# hi_hardware.net
KiCad netlist of a schematic drawn in EAGLE
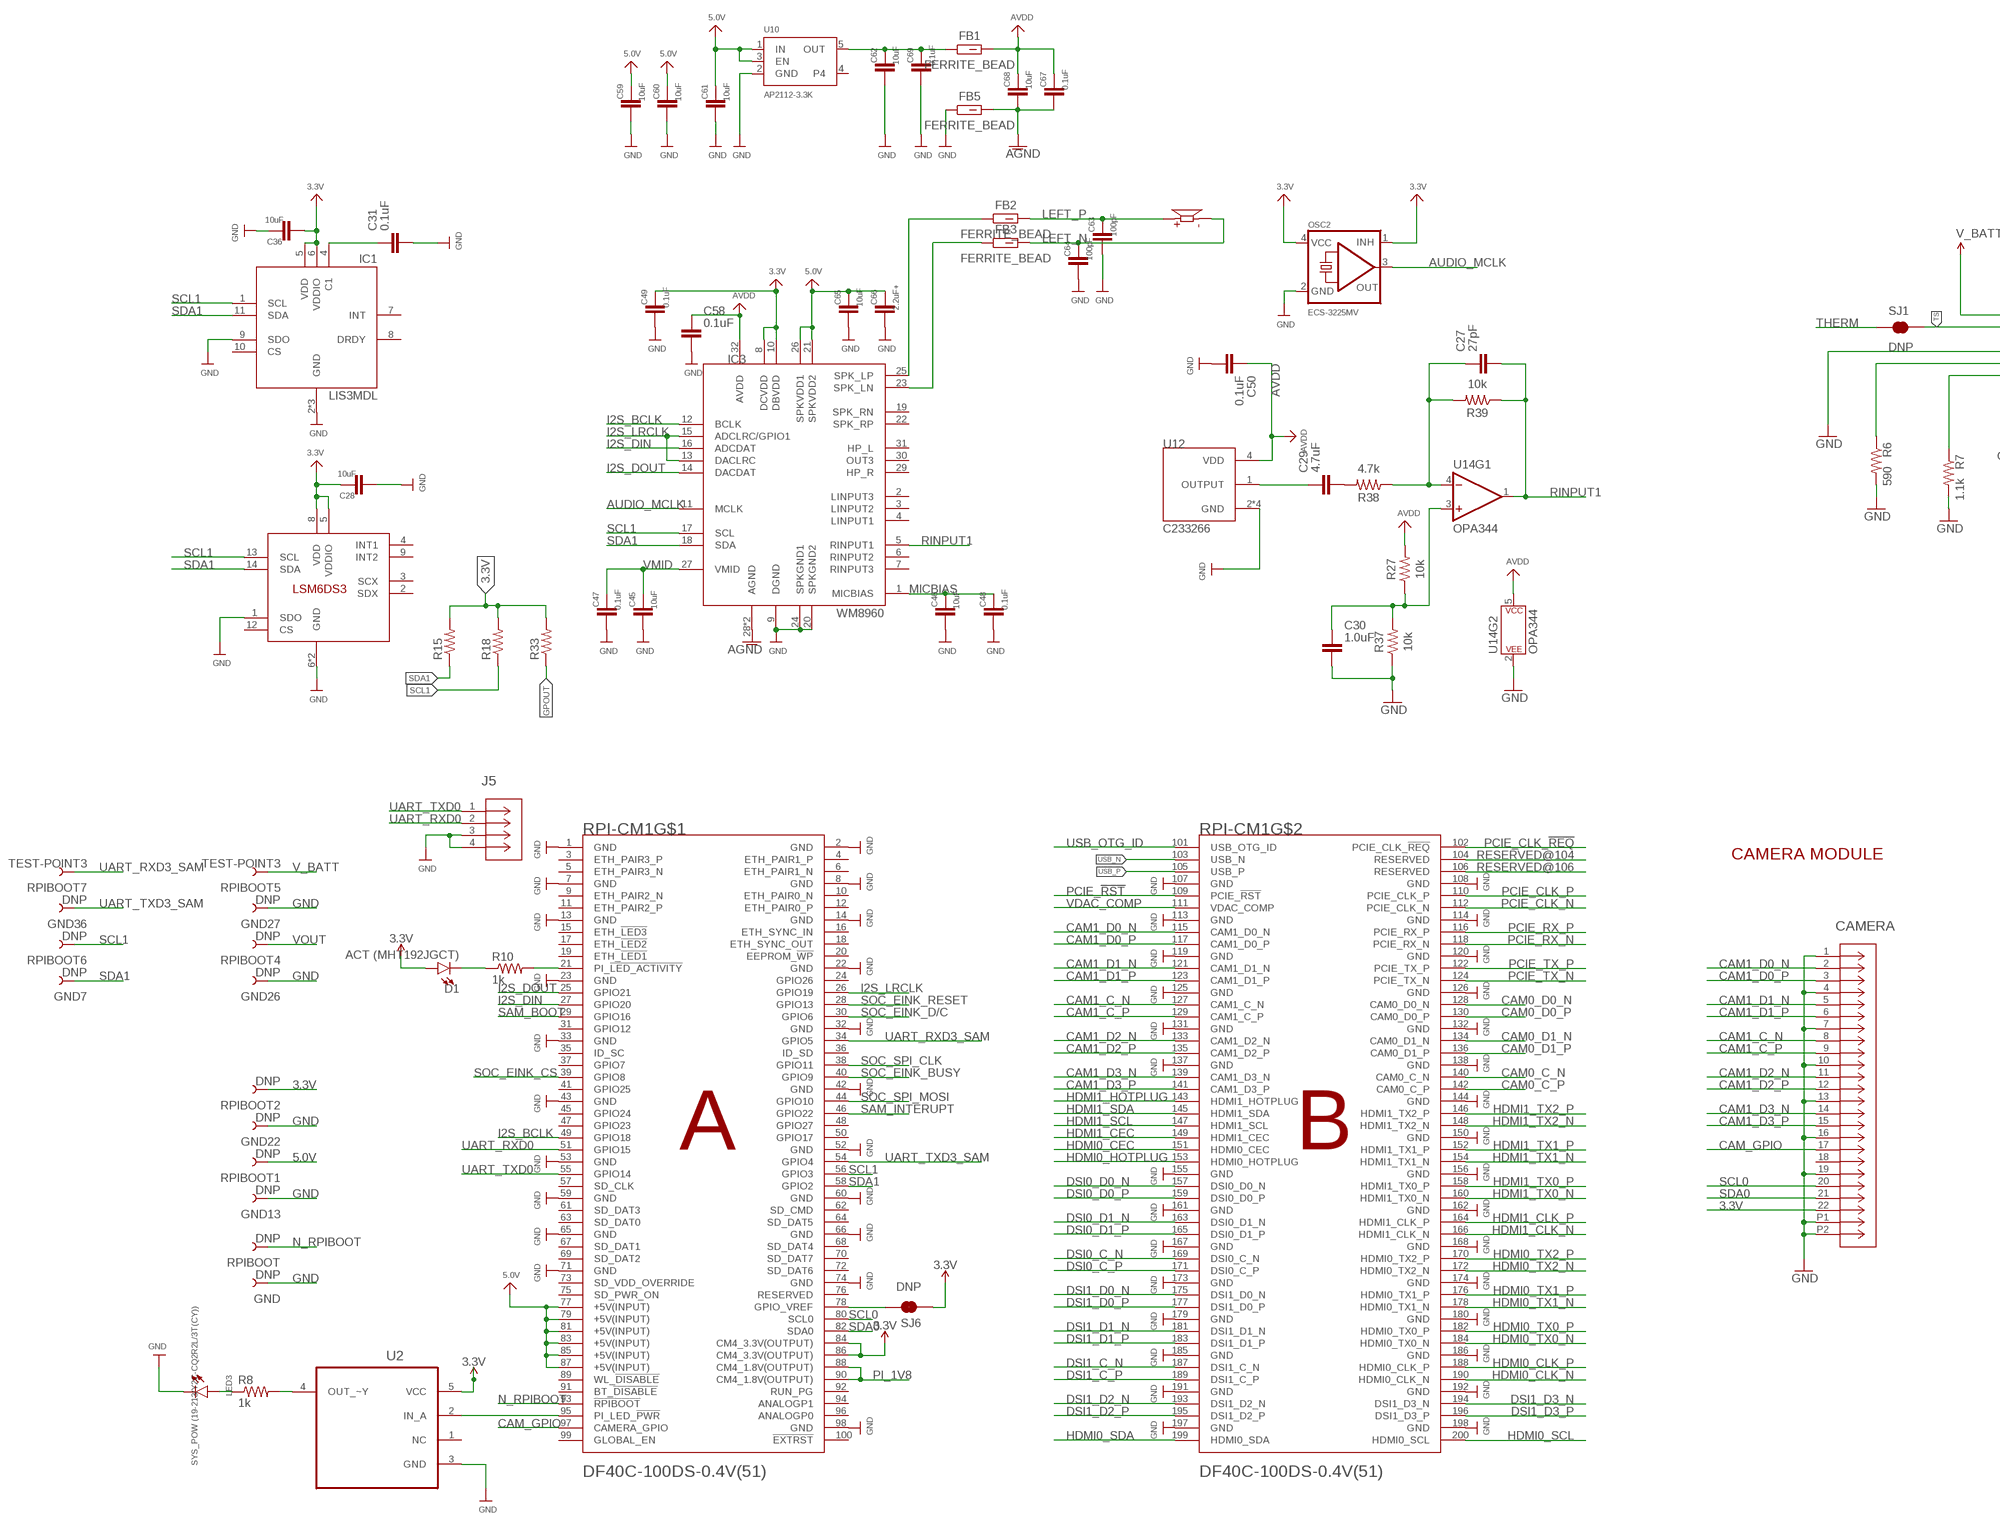
[diagram p0: schematic, sheet 1, part 1 of 3]
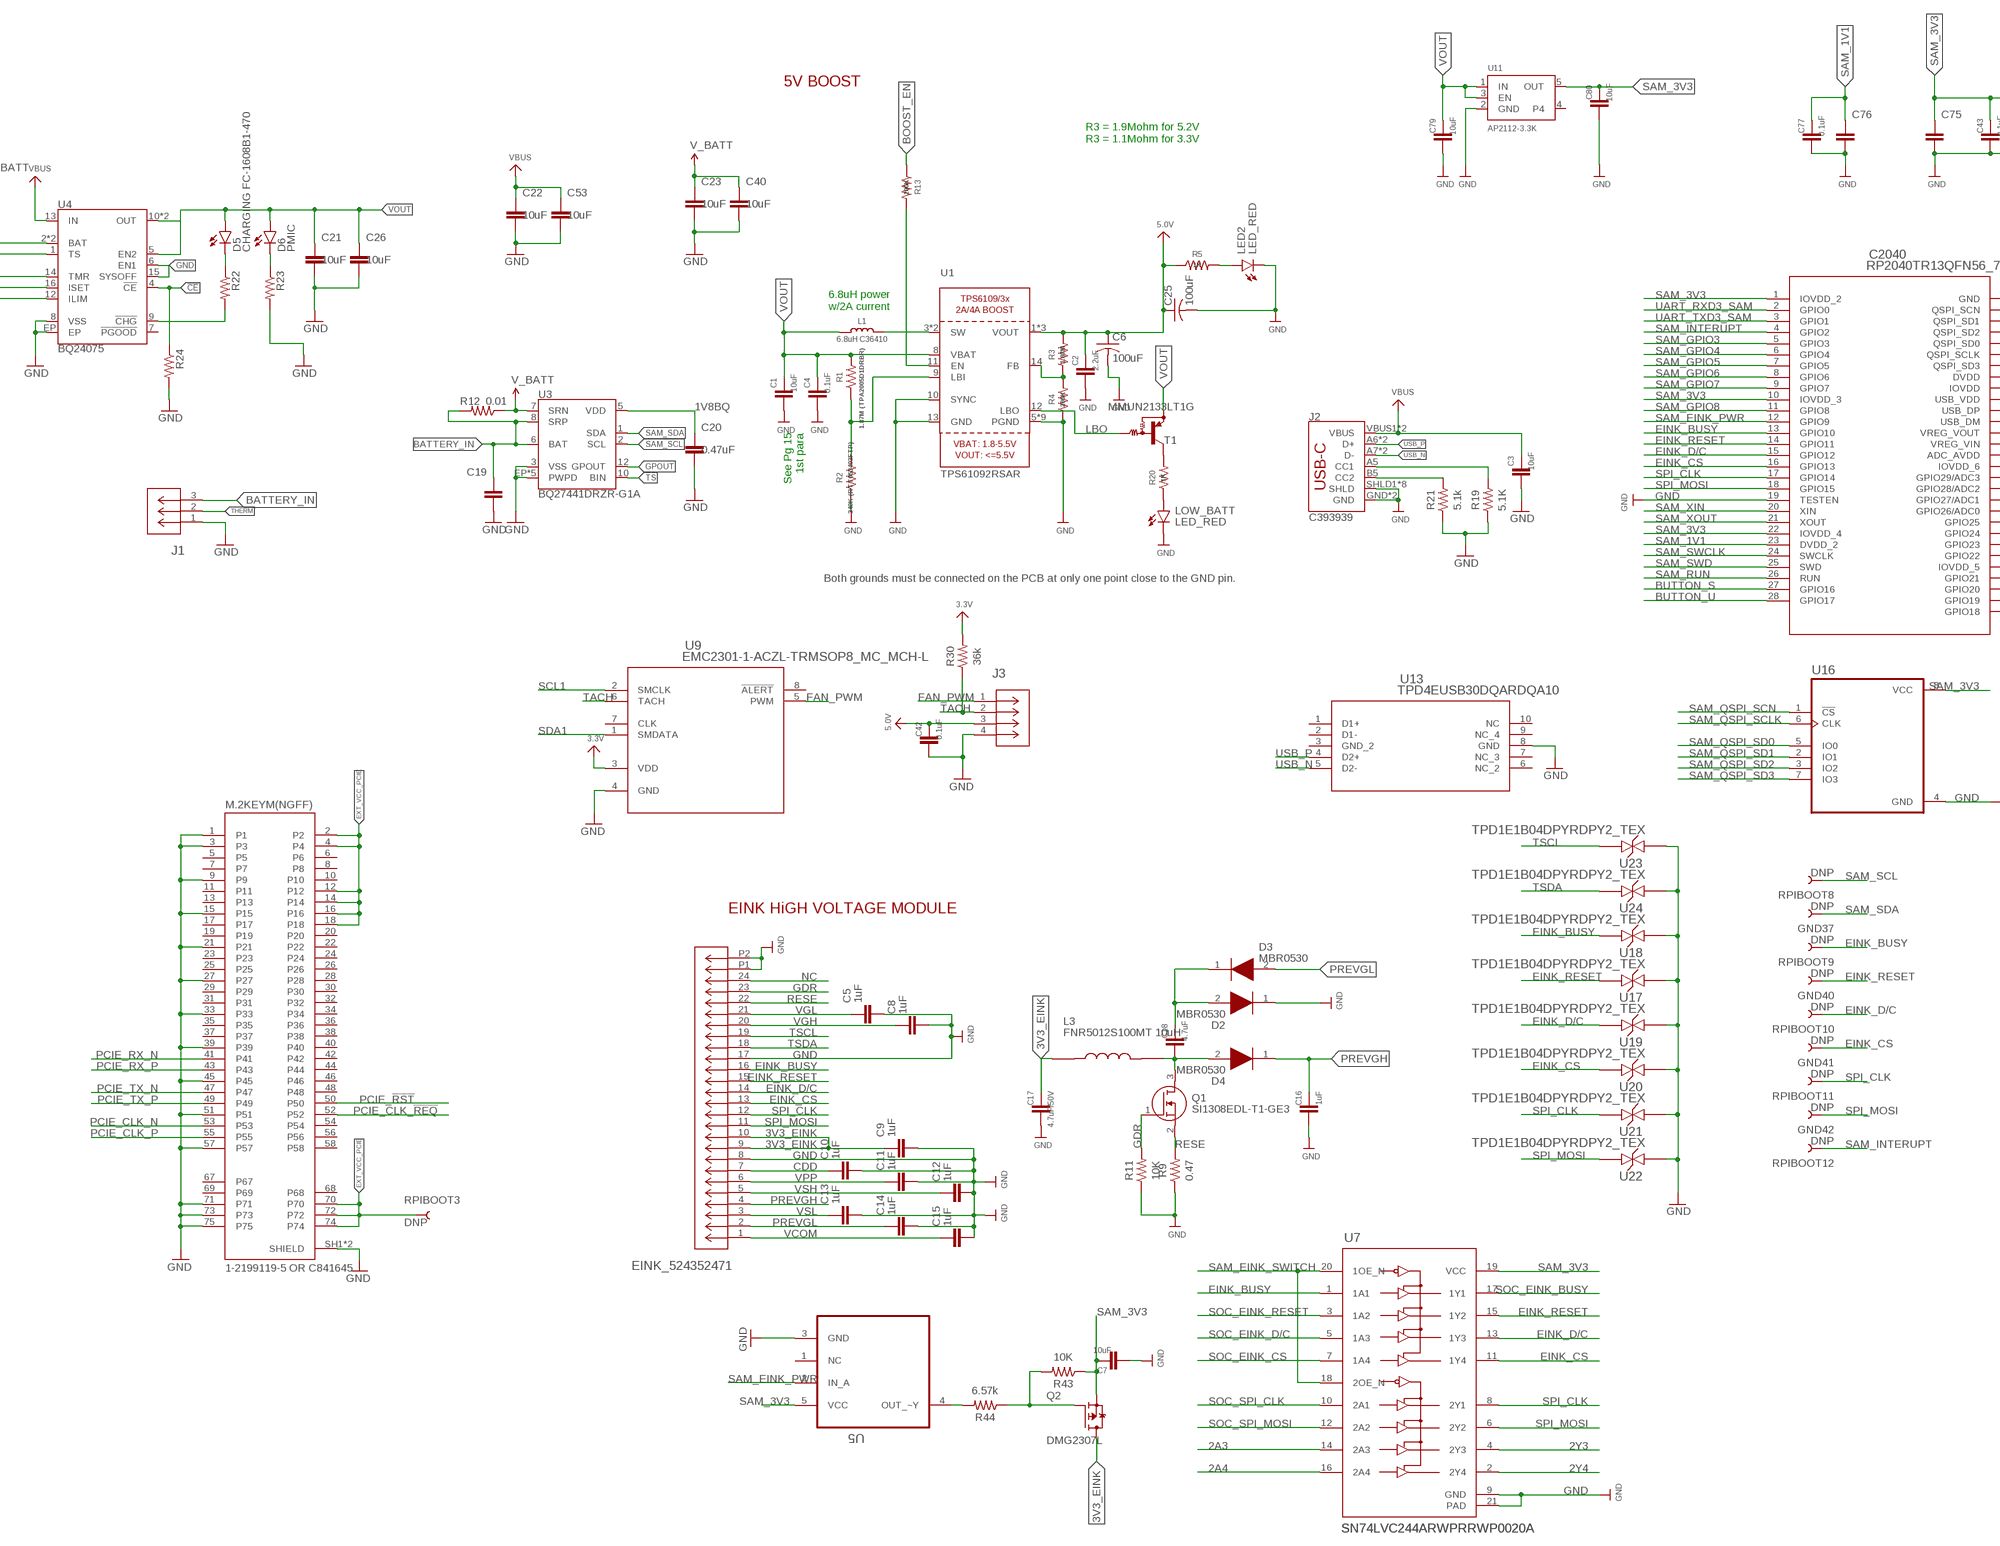
[diagram p1: schematic, sheet 1, part 2 of 3]
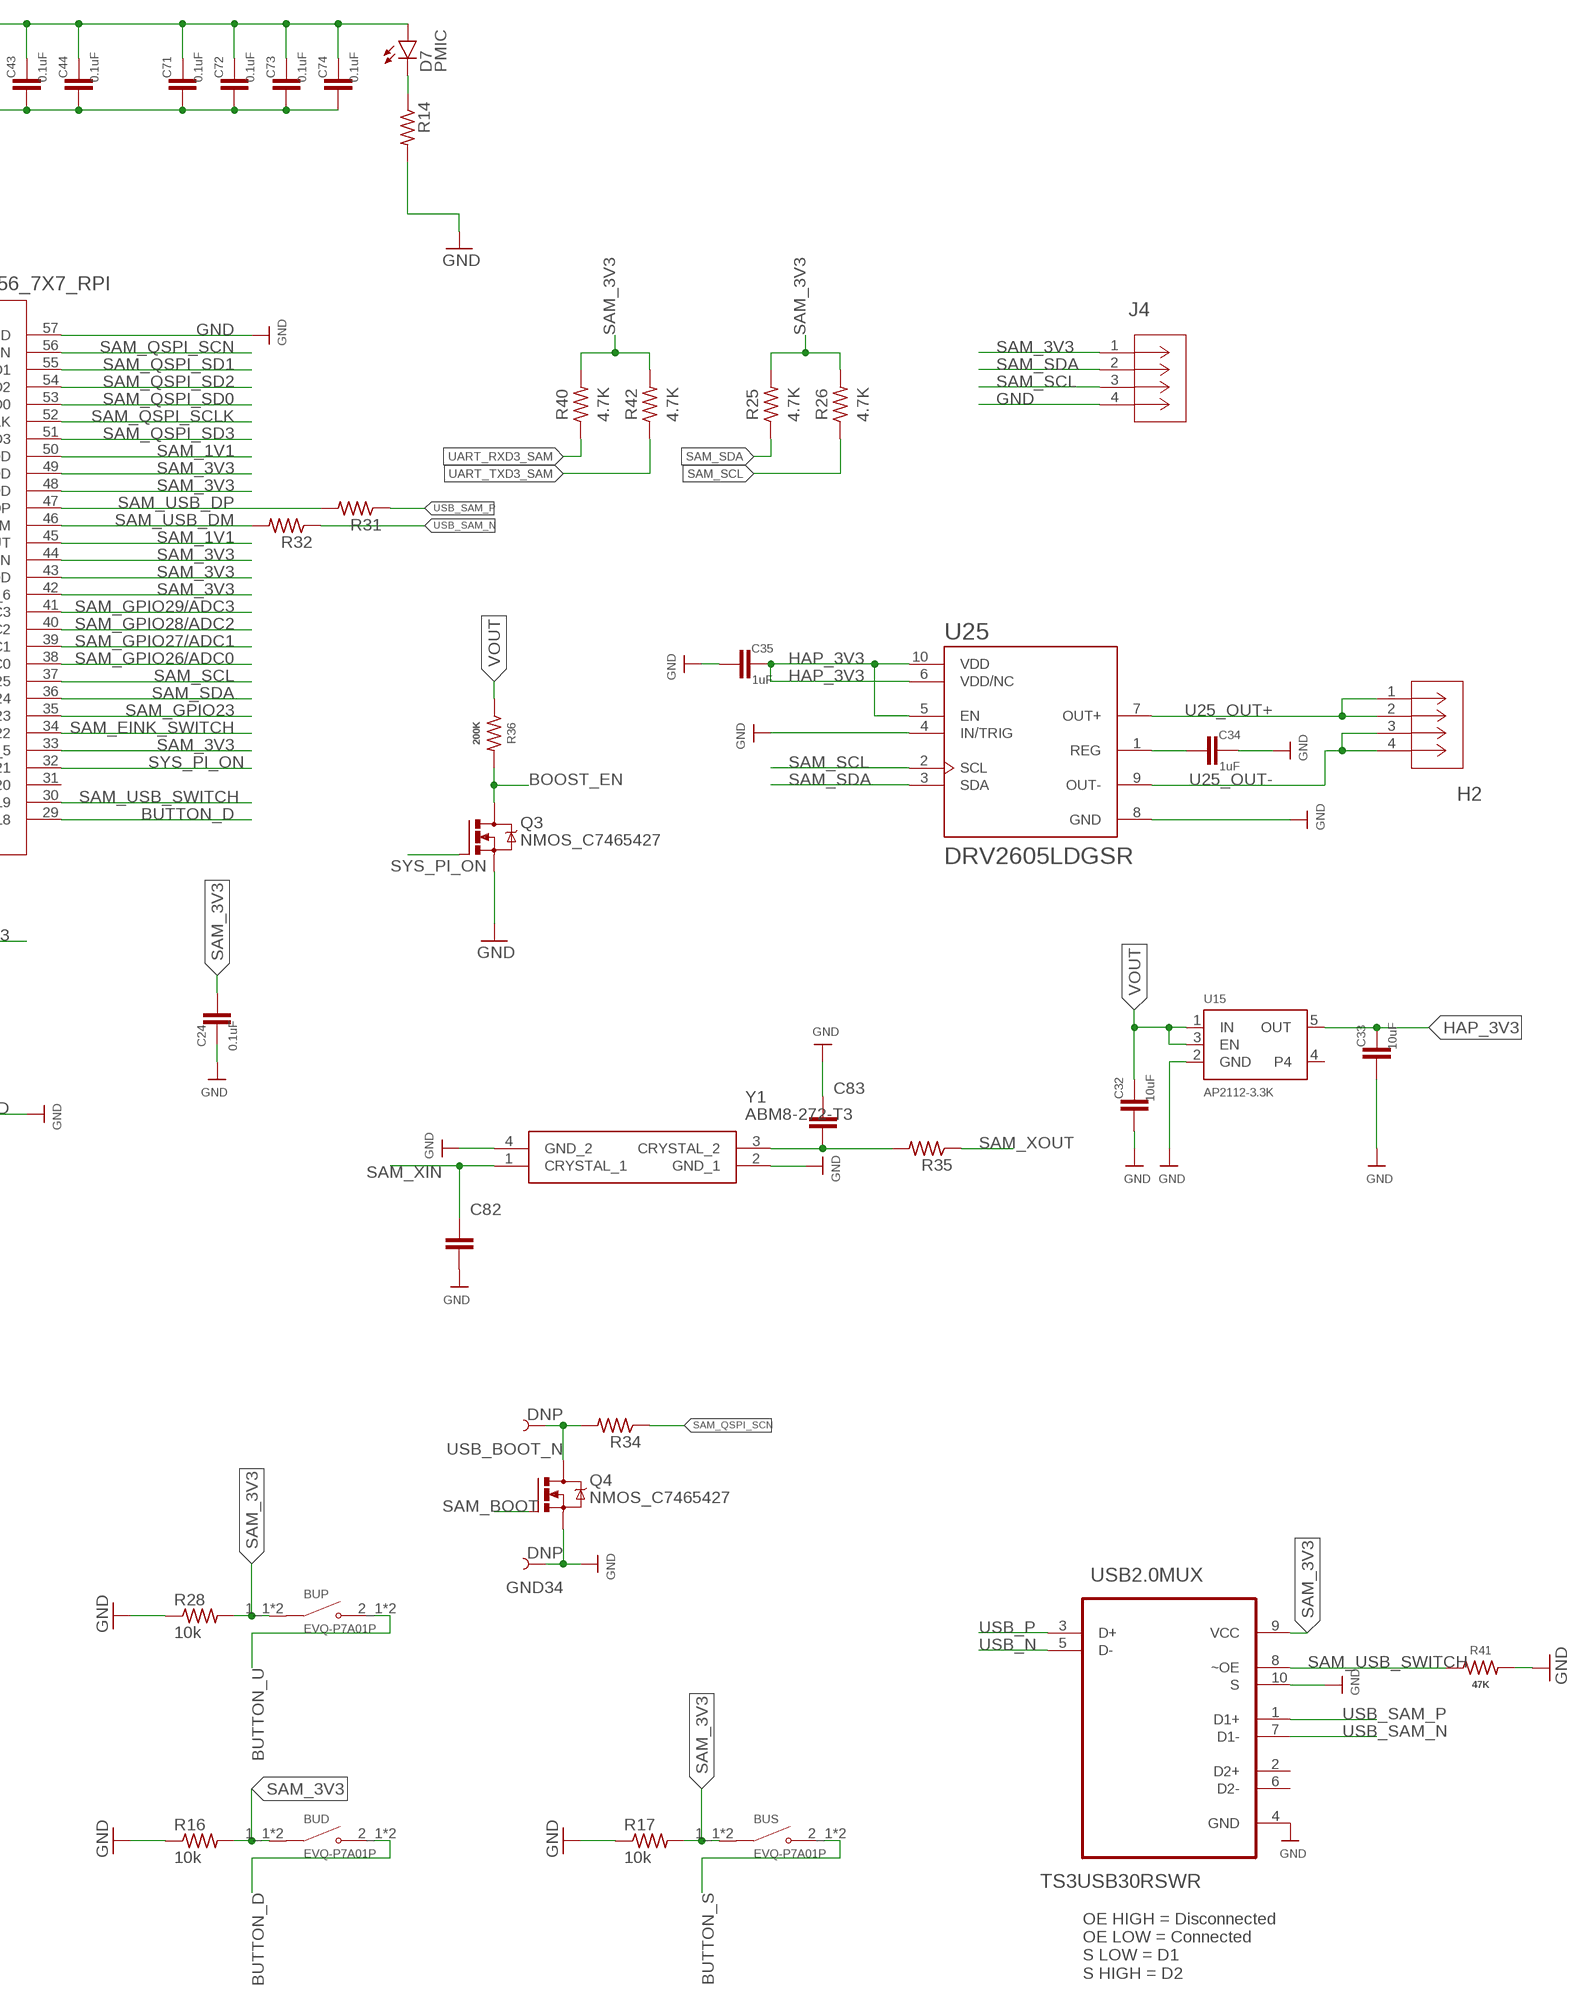
[diagram p2: schematic, sheet 1, part 3 of 3]

(export (version "E")
  (design (tool "Eeschema 10.0.6"))
  (components
    (comp (ref "BUD")
      (value "EVQ-P7A01P")
      (footprint "eagle-import:SW_EVQ-P7A01P")
      (fields (field (name "MANUFACTURER") "Panasonic Electronic Components"))
      (libsource (lib "eagle-import") (part "EVQ-P7A01P"))
    )
    (comp (ref "BUP")
      (value "EVQ-P7A01P")
      (footprint "eagle-import:SW_EVQ-P7A01P")
      (fields (field (name "MANUFACTURER") "Panasonic Electronic Components"))
      (libsource (lib "eagle-import") (part "EVQ-P7A01P"))
    )
    (comp (ref "BUS")
      (value "EVQ-P7A01P")
      (footprint "eagle-import:SW_EVQ-P7A01P")
      (fields (field (name "MANUFACTURER") "Panasonic Electronic Components"))
      (libsource (lib "eagle-import") (part "EVQ-P7A01P"))
    )
    (comp (ref "C1")
      (value "10uF")
      (footprint "eagle-import:CAPC1005X60")
      (libsource (lib "eagle-import") (part "CCHIP-0402(1005-METRIC)_"))
    )
    (comp (ref "C2")
      (value "2.2uF")
      (footprint "eagle-import:CAPC1005X60")
      (libsource (lib "eagle-import") (part "CCHIP-0402(1005-METRIC)_"))
    )
    (comp (ref "C3")
      (value "10uF")
      (footprint "eagle-import:CAPC1005X60")
      (libsource (lib "eagle-import") (part "CCHIP-0402(1005-METRIC)_"))
    )
    (comp (ref "C4")
      (value "0.1uF")
      (footprint "eagle-import:CAPC1005X60")
      (libsource (lib "eagle-import") (part "CCHIP-0402(1005-METRIC)_"))
    )
    (comp (ref "C5")
      (value "1uF")
      (footprint "eagle-import:CAPC1005X60")
      (libsource (lib "eagle-import") (part "CCHIP-0402(1005-METRIC)_"))
    )
    (comp (ref "C6")
      (value "100uF")
      (footprint "eagle-import:C1210")
      (libsource (lib "eagle-import") (part "C-USC1210"))
    )
    (comp (ref "C7")
      (value "10uF")
      (footprint "eagle-import:CAPC1005X60")
      (libsource (lib "eagle-import") (part "CCHIP-0402(1005-METRIC)_"))
    )
    (comp (ref "C8")
      (value "1uF")
      (footprint "eagle-import:CAPC1005X60")
      (libsource (lib "eagle-import") (part "CCHIP-0402(1005-METRIC)_"))
    )
    (comp (ref "C9")
      (value "1uF")
      (footprint "eagle-import:CAPC1005X60")
      (libsource (lib "eagle-import") (part "CCHIP-0402(1005-METRIC)_"))
    )
    (comp (ref "C10")
      (value "1uF")
      (footprint "eagle-import:CAPC1005X60")
      (libsource (lib "eagle-import") (part "CCHIP-0402(1005-METRIC)_"))
    )
    (comp (ref "C11")
      (value "1uF")
      (footprint "eagle-import:CAPC1005X60")
      (libsource (lib "eagle-import") (part "CCHIP-0402(1005-METRIC)_"))
    )
    (comp (ref "C12")
      (value "1uF")
      (footprint "eagle-import:CAPC1005X60")
      (libsource (lib "eagle-import") (part "CCHIP-0402(1005-METRIC)_"))
    )
    (comp (ref "C13")
      (value "1uF")
      (footprint "eagle-import:CAPC1005X60")
      (libsource (lib "eagle-import") (part "CCHIP-0402(1005-METRIC)_"))
    )
    (comp (ref "C14")
      (value "1uF")
      (footprint "eagle-import:CAPC1005X60")
      (libsource (lib "eagle-import") (part "CCHIP-0402(1005-METRIC)_"))
    )
    (comp (ref "C15")
      (value "1uF")
      (footprint "eagle-import:CAPC1005X60")
      (libsource (lib "eagle-import") (part "CCHIP-0402(1005-METRIC)_"))
    )
    (comp (ref "C16")
      (value "1uF")
      (footprint "eagle-import:CAPC1005X60")
      (libsource (lib "eagle-import") (part "CCHIP-0402(1005-METRIC)_"))
    )
    (comp (ref "C17")
      (value "4.7uF/50V")
      (footprint "eagle-import:CAPC1005X60")
      (libsource (lib "eagle-import") (part "CCHIP-0402(1005-METRIC)_"))
    )
    (comp (ref "C18")
      (value "4.7uF")
      (footprint "eagle-import:CAPC1608X85")
      (libsource (lib "eagle-import") (part "CCHIP-0603(1608-METRIC)_"))
    )
    (comp (ref "C19")
      (value "1.0uF")
      (footprint "eagle-import:CAPC1005X60")
      (libsource (lib "eagle-import") (part "CCHIP-0402(1005-METRIC)_"))
    )
    (comp (ref "C20")
      (value "0.47uF")
      (footprint "eagle-import:CAPC1005X60")
      (libsource (lib "eagle-import") (part "CCHIP-0402(1005-METRIC)_"))
    )
    (comp (ref "C21")
      (value "10uF")
      (footprint "eagle-import:CAPC1005X60")
      (libsource (lib "eagle-import") (part "CCHIP-0402(1005-METRIC)_"))
    )
    (comp (ref "C22")
      (value "10uF")
      (footprint "eagle-import:CAPC1005X60")
      (libsource (lib "eagle-import") (part "CCHIP-0402(1005-METRIC)_"))
    )
    (comp (ref "C23")
      (value "10uF")
      (footprint "eagle-import:CAPC1005X60")
      (libsource (lib "eagle-import") (part "CCHIP-0402(1005-METRIC)_"))
    )
    (comp (ref "C24")
      (value "0.1uF")
      (footprint "eagle-import:CAPC1005X60")
      (libsource (lib "eagle-import") (part "CCHIP-0402(1005-METRIC)_"))
    )
    (comp (ref "C25")
      (value "100uF")
      (footprint "eagle-import:C1210")
      (libsource (lib "eagle-import") (part "C-USC1210"))
    )
    (comp (ref "C26")
      (value "10uF")
      (footprint "eagle-import:CAPC1005X60")
      (libsource (lib "eagle-import") (part "CCHIP-0402(1005-METRIC)_"))
    )
    (comp (ref "C27")
      (value "27pF")
      (footprint "eagle-import:CAPC1005X60")
      (libsource (lib "eagle-import") (part "CCHIP-0402(1005-METRIC)_"))
    )
    (comp (ref "C28")
      (value "10uF")
      (footprint "eagle-import:CAPC1005X60")
      (libsource (lib "eagle-import") (part "CCHIP-0402(1005-METRIC)_"))
    )
    (comp (ref "C29")
      (value "4.7uF")
      (footprint "eagle-import:CAPC1005X60")
      (libsource (lib "eagle-import") (part "CCHIP-0402(1005-METRIC)_"))
    )
    (comp (ref "C30")
      (value "1.0uF")
      (footprint "eagle-import:CAPC1005X60")
      (libsource (lib "eagle-import") (part "CCHIP-0402(1005-METRIC)_"))
    )
    (comp (ref "C31")
      (value "0.1uF")
      (footprint "eagle-import:CAPC1005X60")
      (libsource (lib "eagle-import") (part "CCHIP-0402(1005-METRIC)_"))
    )
    (comp (ref "C32")
      (value "10uF")
      (footprint "eagle-import:CAPC1005X60")
      (libsource (lib "eagle-import") (part "CCHIP-0402(1005-METRIC)_"))
    )
    (comp (ref "C33")
      (value "10uF")
      (footprint "eagle-import:CAPC1005X60")
      (libsource (lib "eagle-import") (part "CCHIP-0402(1005-METRIC)_"))
    )
    (comp (ref "C34")
      (value "1uF")
      (footprint "eagle-import:CAPC1005X60")
      (libsource (lib "eagle-import") (part "CCHIP-0402(1005-METRIC)_"))
    )
    (comp (ref "C35")
      (value "1uF")
      (footprint "eagle-import:CAPC1005X60")
      (libsource (lib "eagle-import") (part "CCHIP-0402(1005-METRIC)_"))
    )
    (comp (ref "C36")
      (value "10uF")
      (footprint "eagle-import:CAPC1005X60")
      (libsource (lib "eagle-import") (part "CCHIP-0402(1005-METRIC)_"))
    )
    (comp (ref "C40")
      (value "10uF")
      (footprint "eagle-import:CAPC1005X60")
      (libsource (lib "eagle-import") (part "CCHIP-0402(1005-METRIC)_"))
    )
    (comp (ref "C42")
      (value "0.1uF")
      (footprint "eagle-import:CAPC1608X85")
      (libsource (lib "eagle-import") (part "CCHIP-0603(1608-METRIC)_"))
    )
    (comp (ref "C43")
      (value "0.1uF")
      (footprint "eagle-import:CAPC1005X60")
      (libsource (lib "eagle-import") (part "CCHIP-0402(1005-METRIC)_"))
    )
    (comp (ref "C44")
      (value "0.1uF")
      (footprint "eagle-import:CAPC1005X60")
      (libsource (lib "eagle-import") (part "CCHIP-0402(1005-METRIC)_"))
    )
    (comp (ref "C45")
      (value "10uF")
      (footprint "eagle-import:CAPC1005X60")
      (libsource (lib "eagle-import") (part "CCHIP-0402(1005-METRIC)_"))
    )
    (comp (ref "C46")
      (value "10uF")
      (footprint "eagle-import:CAPC1005X60")
      (libsource (lib "eagle-import") (part "CCHIP-0402(1005-METRIC)_"))
    )
    (comp (ref "C47")
      (value "0.1uF")
      (footprint "eagle-import:CAPC1005X60")
      (libsource (lib "eagle-import") (part "CCHIP-0402(1005-METRIC)_"))
    )
    (comp (ref "C48")
      (value "0.1uF")
      (footprint "eagle-import:CAPC1005X60")
      (libsource (lib "eagle-import") (part "CCHIP-0402(1005-METRIC)_"))
    )
    (comp (ref "C49")
      (value "0.1uF")
      (footprint "eagle-import:CAPC1005X60")
      (libsource (lib "eagle-import") (part "CCHIP-0402(1005-METRIC)_"))
    )
    (comp (ref "C50")
      (value "0.1uF")
      (footprint "eagle-import:CAPC1005X60")
      (libsource (lib "eagle-import") (part "CCHIP-0402(1005-METRIC)_"))
    )
    (comp (ref "C53")
      (value "10uF")
      (footprint "eagle-import:CAPC1005X60")
      (libsource (lib "eagle-import") (part "CCHIP-0402(1005-METRIC)_"))
    )
    (comp (ref "C58")
      (value "0.1uF")
      (footprint "eagle-import:CAPC1005X60")
      (libsource (lib "eagle-import") (part "CCHIP-0402(1005-METRIC)_"))
    )
    (comp (ref "C59")
      (value "10uF")
      (footprint "eagle-import:CAPC1005X60")
      (libsource (lib "eagle-import") (part "CCHIP-0402(1005-METRIC)_"))
    )
    (comp (ref "C60")
      (value "10uF")
      (footprint "eagle-import:CAPC1005X60")
      (libsource (lib "eagle-import") (part "CCHIP-0402(1005-METRIC)_"))
    )
    (comp (ref "C61")
      (value "10uF")
      (footprint "eagle-import:CAPC1005X60")
      (libsource (lib "eagle-import") (part "CCHIP-0402(1005-METRIC)_"))
    )
    (comp (ref "C62")
      (value "10uF")
      (footprint "eagle-import:CAPC1005X60")
      (libsource (lib "eagle-import") (part "CCHIP-0402(1005-METRIC)_"))
    )
    (comp (ref "C63")
      (value "100pF")
      (footprint "eagle-import:CAPC1005X60")
      (libsource (lib "eagle-import") (part "CCHIP-0402(1005-METRIC)_"))
    )
    (comp (ref "C64")
      (value "100pF")
      (footprint "eagle-import:CAPC1005X60")
      (libsource (lib "eagle-import") (part "CCHIP-0402(1005-METRIC)_"))
    )
    (comp (ref "C65")
      (value "10uF")
      (footprint "eagle-import:CAPC1005X60")
      (libsource (lib "eagle-import") (part "CCHIP-0402(1005-METRIC)_"))
    )
    (comp (ref "C66")
      (value "2.2uF+")
      (footprint "eagle-import:CAPC1005X60")
      (libsource (lib "eagle-import") (part "CCHIP-0402(1005-METRIC)_"))
    )
    (comp (ref "C67")
      (value "0.1uF")
      (footprint "eagle-import:CAPC1005X60")
      (libsource (lib "eagle-import") (part "CCHIP-0402(1005-METRIC)_"))
    )
    (comp (ref "C68")
      (value "10uF")
      (footprint "eagle-import:CAPC1005X60")
      (libsource (lib "eagle-import") (part "CCHIP-0402(1005-METRIC)_"))
    )
    (comp (ref "C69")
      (value "0.1uF")
      (footprint "eagle-import:CAPC1005X60")
      (libsource (lib "eagle-import") (part "CCHIP-0402(1005-METRIC)_"))
    )
    (comp (ref "C71")
      (value "0.1uF")
      (footprint "eagle-import:CAPC1005X60")
      (libsource (lib "eagle-import") (part "CCHIP-0402(1005-METRIC)_"))
    )
    (comp (ref "C72")
      (value "0.1uF")
      (footprint "eagle-import:CAPC1005X60")
      (libsource (lib "eagle-import") (part "CCHIP-0402(1005-METRIC)_"))
    )
    (comp (ref "C73")
      (value "0.1uF")
      (footprint "eagle-import:CAPC1005X60")
      (libsource (lib "eagle-import") (part "CCHIP-0402(1005-METRIC)_"))
    )
    (comp (ref "C74")
      (value "0.1uF")
      (footprint "eagle-import:CAPC1005X60")
      (libsource (lib "eagle-import") (part "CCHIP-0402(1005-METRIC)_"))
    )
    (comp (ref "C75")
      (value "1.0uF")
      (footprint "eagle-import:CAPC1005X60")
      (libsource (lib "eagle-import") (part "CCHIP-0402(1005-METRIC)_"))
    )
    (comp (ref "C76")
      (value "1.0uF")
      (footprint "eagle-import:CAPC1005X60")
      (libsource (lib "eagle-import") (part "CCHIP-0402(1005-METRIC)_"))
    )
    (comp (ref "C77")
      (value "0.1uF")
      (footprint "eagle-import:CAPC1005X60")
      (libsource (lib "eagle-import") (part "CCHIP-0402(1005-METRIC)_"))
    )
    (comp (ref "C79")
      (value "10uF")
      (footprint "eagle-import:CAPC1005X60")
      (libsource (lib "eagle-import") (part "CCHIP-0402(1005-METRIC)_"))
    )
    (comp (ref "C80")
      (value "10uF")
      (footprint "eagle-import:CAPC1005X60")
      (libsource (lib "eagle-import") (part "CCHIP-0402(1005-METRIC)_"))
    )
    (comp (ref "C82")
      (value "15p")
      (footprint "eagle-import:CAPC1005X60")
      (libsource (lib "eagle-import") (part "CCHIP-0402(1005-METRIC)_"))
    )
    (comp (ref "C83")
      (value "15p")
      (footprint "eagle-import:CAPC1005X60")
      (libsource (lib "eagle-import") (part "CCHIP-0402(1005-METRIC)_"))
    )
    (comp (ref "C2040")
      (value "RP2040TR13QFN56_7X7_RPI")
      (footprint "eagle-import:QFN56_7X7_RPI")
      (fields
        (field (name "MANUFACTURER_PART_NUMBER") "RP2040TR13")
        (field (name "COPYRIGHT") "Copyright (C) 2024 Ultra Librarian. All rights reserved.")
      )
      (libsource (lib "eagle-import") (part "RP2040TR13QFN56_7X7_RPI"))
    )
    (comp (ref "CAMERA")
      (value "C262642")
      (footprint "eagle-import:CON_524372271_MOL")
      (fields
        (field (name "MANUFACTURER_PART_NUMBER") "524372271")
        (field (name "COPYRIGHT") "Copyright (C) 2024 Ultra Librarian. All rights reserved.")
      )
      (libsource (lib "eagle-import") (part "524372271CON_524372271_MOL"))
    )
    (comp (ref "D1")
      (value "ACT (MHT192JGCT)")
      (footprint "eagle-import:LED-0603@1")
      (libsource (lib "eagle-import") (part "LED-GREEN0603"))
    )
    (comp (ref "D2")
      (value "MBR0530")
      (footprint "eagle-import:SOD3716X135N")
      (fields (field (name "MF") "ON Semiconductor"))
      (libsource (lib "eagle-import") (part "MBR0530"))
    )
    (comp (ref "D3")
      (value "MBR0530")
      (footprint "eagle-import:SOD3716X135N")
      (fields (field (name "MF") "ON Semiconductor"))
      (libsource (lib "eagle-import") (part "MBR0530"))
    )
    (comp (ref "D4")
      (value "MBR0530")
      (footprint "eagle-import:SOD3716X135N")
      (fields (field (name "MF") "ON Semiconductor"))
      (libsource (lib "eagle-import") (part "MBR0530"))
    )
    (comp (ref "D5")
      (value "CHARGING FC-1608B1-470")
      (footprint "eagle-import:LED-0603")
      (libsource (lib "eagle-import") (part "LED-BLUE0603"))
    )
    (comp (ref "D6")
      (value "PMIC")
      (footprint "eagle-import:LED-0603")
      (libsource (lib "eagle-import") (part "LED-RED0603"))
    )
    (comp (ref "D7")
      (value "PMIC")
      (footprint "eagle-import:LED-0603")
      (libsource (lib "eagle-import") (part "LED-RED0603"))
    )
    (comp (ref "EINK_524352471")
      (value "524372471")
      (footprint "eagle-import:CON_524372471_MOL")
      (fields (field (name "COPYRIGHT") "Copyright (C) 2024 Ultra Librarian. All rights reserved."))
      (libsource (lib "eagle-import") (part "524372471CON_524372471_MOL"))
    )
    (comp (ref "FB1")
      (value "FERRITE_BEAD")
      (footprint "eagle-import:BEADC1608X95N")
      (libsource (lib "eagle-import") (part "FBCHIP-0603(1608-METRIC)"))
    )
    (comp (ref "FB2")
      (value "FERRITE_BEAD")
      (footprint "eagle-import:BEADC1608X95N")
      (libsource (lib "eagle-import") (part "FBCHIP-0603(1608-METRIC)"))
    )
    (comp (ref "FB3")
      (value "FERRITE_BEAD")
      (footprint "eagle-import:BEADC1608X95N")
      (libsource (lib "eagle-import") (part "FBCHIP-0603(1608-METRIC)"))
    )
    (comp (ref "FB5")
      (value "FERRITE_BEAD")
      (footprint "eagle-import:BEADC1608X95N")
      (libsource (lib "eagle-import") (part "FBCHIP-0603(1608-METRIC)"))
    )
    (comp (ref "GND")
      (value "DNP")
      (footprint "eagle-import:PAD.03X.03")
      (libsource (lib "eagle-import") (part "TEST-POINT3"))
    )
    (comp (ref "GND7")
      (value "DNP")
      (footprint "eagle-import:PAD.03X.03")
      (libsource (lib "eagle-import") (part "TEST-POINT3"))
    )
    (comp (ref "GND13")
      (value "DNP")
      (footprint "eagle-import:PAD.03X.03")
      (libsource (lib "eagle-import") (part "TEST-POINT3"))
    )
    (comp (ref "GND22")
      (value "DNP")
      (footprint "eagle-import:PAD.03X.03")
      (libsource (lib "eagle-import") (part "TEST-POINT3"))
    )
    (comp (ref "GND26")
      (value "DNP")
      (footprint "eagle-import:PAD.03X.03")
      (libsource (lib "eagle-import") (part "TEST-POINT3"))
    )
    (comp (ref "GND27")
      (value "DNP")
      (footprint "eagle-import:PAD.03X.03")
      (libsource (lib "eagle-import") (part "TEST-POINT3"))
    )
    (comp (ref "GND34")
      (value "DNP")
      (footprint "eagle-import:PAD.03X.03")
      (libsource (lib "eagle-import") (part "TEST-POINT3"))
    )
    (comp (ref "GND36")
      (value "DNP")
      (footprint "eagle-import:PAD.03X.03")
      (libsource (lib "eagle-import") (part "TEST-POINT3"))
    )
    (comp (ref "GND37")
      (value "DNP")
      (footprint "eagle-import:PAD.03X.03")
      (libsource (lib "eagle-import") (part "TEST-POINT3"))
    )
    (comp (ref "GND40")
      (value "DNP")
      (footprint "eagle-import:PAD.03X.03")
      (libsource (lib "eagle-import") (part "TEST-POINT3"))
    )
    (comp (ref "GND41")
      (value "DNP")
      (footprint "eagle-import:PAD.03X.03")
      (libsource (lib "eagle-import") (part "TEST-POINT3"))
    )
    (comp (ref "GND42")
      (value "DNP")
      (footprint "eagle-import:PAD.03X.03")
      (libsource (lib "eagle-import") (part "TEST-POINT3"))
    )
    (comp (ref "H2")
      (value "BM04B-SRSS-TBCONN4_BM04B-SRSS_JST")
      (footprint "eagle-import:CONN4_BM04B-SRSS_JST")
      (fields
        (field (name "MANUFACTURER_PART_NUMBER") "BM04B-SRSS-TB")
        (field (name "COPYRIGHT") "Copyright (C) 2024 Ultra Librarian. All rights reserved.")
      )
      (libsource (lib "eagle-import") (part "BM04B-SRSS-TBCONN4_BM04B-SRSS_JST"))
    )
    (comp (ref "IC1")
      (value "LIS3MDL")
      (footprint "eagle-import:LGA12_2X2MM")
      (libsource (lib "eagle-import") (part "LIS3MDL"))
    )
    (comp (ref "IC3")
      (value "WM8960")
      (footprint "eagle-import:QFN32_5MM")
      (libsource (lib "eagle-import") (part "WM8960"))
    )
    (comp (ref "J1")
      (value "SM03B-SRSS-TBCONN_SM03B-SRSS-TB_JST")
      (footprint "eagle-import:CONN_SM03B-SRSS-TB_JST")
      (fields
        (field (name "MANUFACTURER_PART_NUMBER") "SM03B-SRSS-TB")
        (field (name "COPYRIGHT") "Copyright (C) 2024 Ultra Librarian. All rights reserved.")
      )
      (libsource (lib "eagle-import") (part "SM03B-SRSS-TBCONN_SM03B-SRSS-TB_JST"))
    )
    (comp (ref "J2")
      (value "C393939")
      (footprint "eagle-import:USB-C-16P")
      (libsource (lib "eagle-import") (part "USB_C16PIN"))
    )
    (comp (ref "J3")
      (value "BM04B-SRSS-TBCONN4_BM04B-SRSS_JST")
      (footprint "eagle-import:CONN4_BM04B-SRSS_JST")
      (fields
        (field (name "MANUFACTURER_PART_NUMBER") "BM04B-SRSS-TB")
        (field (name "COPYRIGHT") "Copyright (C) 2024 Ultra Librarian. All rights reserved.")
      )
      (libsource (lib "eagle-import") (part "BM04B-SRSS-TBCONN4_BM04B-SRSS_JST"))
    )
    (comp (ref "J4")
      (value "BM04B-SRSS-TBCONN4_BM04B-SRSS_JST")
      (footprint "eagle-import:CONN4_BM04B-SRSS_JST")
      (fields
        (field (name "MANUFACTURER_PART_NUMBER") "BM04B-SRSS-TB")
        (field (name "COPYRIGHT") "Copyright (C) 2024 Ultra Librarian. All rights reserved.")
      )
      (libsource (lib "eagle-import") (part "BM04B-SRSS-TBCONN4_BM04B-SRSS_JST"))
    )
    (comp (ref "J5")
      (value "BM04B-SRSS-TBCONN4_BM04B-SRSS_JST")
      (footprint "eagle-import:CONN4_BM04B-SRSS_JST")
      (fields
        (field (name "MANUFACTURER_PART_NUMBER") "BM04B-SRSS-TB")
        (field (name "COPYRIGHT") "Copyright (C) 2024 Ultra Librarian. All rights reserved.")
      )
      (libsource (lib "eagle-import") (part "BM04B-SRSS-TBCONN4_BM04B-SRSS_JST"))
    )
    (comp (ref "L1")
      (value "6.8uH C36410")
      (footprint "eagle-import:INDUCTOR_5X5MM_TDK_VLC5045")
      (libsource (lib "eagle-import") (part "INDUCTORTDK_VLC5045"))
    )
    (comp (ref "L3")
      (value "FNR5012S100MT 10uH")
      (footprint "eagle-import:IND_LQH5BPN2R2NT0L")
      (fields (field (name "MANUFACTURER") "Murata"))
      (libsource (lib "eagle-import") (part "LQH5BPN2R2NT0L"))
    )
    (comp (ref "LED2")
      (value "LED_RED")
      (footprint "eagle-import:LEDC1608X65N_RND-R")
      (libsource (lib "eagle-import") (part "CHIP-ROUND-R_0603"))
    )
    (comp (ref "LED3")
      (value "SYS_POW (19-213/Y2C-CQ2R2L/3T(CY))")
      (footprint "eagle-import:LED-0603")
      (libsource (lib "eagle-import") (part "LED0603"))
    )
    (comp (ref "LOW_BATT")
      (value "LED_RED")
      (footprint "eagle-import:LEDC1608X65N_RND-R")
      (libsource (lib "eagle-import") (part "CHIP-ROUND-R_0603"))
    )
    (comp (ref "LS1")
      (value "CMS-18138A-SP")
      (footprint "eagle-import:CUI_CMS-18138A-SP")
      (fields (field (name "MF") "CUI Devices"))
      (libsource (lib "eagle-import") (part "CMS-18138A-SP"))
    )
    (comp (ref "M.2KEYM(NGFF)")
      (value "1-2199119-5 OR C841645")
      (footprint "eagle-import:TE_1-2199119-5")
      (fields
        (field (name "COMMENT") "1-2199119-5")
        (field (name "DIGIKEY_PART_NUMBER") "A115902TR-ND")
        (field (name "MF") "TE Connectivity")
      )
      (libsource (lib "eagle-import") (part "1-2199119-5"))
    )
    (comp (ref "OSC2")
      (value "ECS-3225MV")
      (footprint "eagle-import:OSC_3.2X2.5MM")
      (libsource (lib "eagle-import") (part "OSCILLATOR3.2X2.5"))
    )
    (comp (ref "Q1")
      (value "SI1308EDL-T1-GE3")
      (footprint "eagle-import:SOT65P210X110-3N")
      (fields (field (name "MF") "Vishay Siliconix"))
      (libsource (lib "eagle-import") (part "SI1308EDL-T1-GE3"))
    )
    (comp (ref "Q2")
      (value "DMG2307L")
      (footprint "eagle-import:SOT96P240X110-3N")
      (fields (field (name "MF") "Diodes Inc."))
      (libsource (lib "eagle-import") (part "DMG2307L"))
    )
    (comp (ref "Q3")
      (value "NMOS_C7465427")
      (footprint "eagle-import:SOT23")
      (libsource (lib "eagle-import") (part "NMOSFETSOT23-GSD"))
    )
    (comp (ref "Q4")
      (value "NMOS_C7465427")
      (footprint "eagle-import:SOT23")
      (libsource (lib "eagle-import") (part "NMOSFETSOT23-GSD"))
    )
    (comp (ref "R1")
      (value "1.87M (TPA2005D1DRBR)")
      (footprint "eagle-import:RESC1005X40")
      (libsource (lib "eagle-import") (part "R-USCHIP-0402(1005-METRIC)_"))
    )
    (comp (ref "R2")
      (value "340K (RTT053403FTP)")
      (footprint "eagle-import:RESC1005X40")
      (libsource (lib "eagle-import") (part "R-USCHIP-0402(1005-METRIC)_"))
    )
    (comp (ref "R3")
      (value "1.87M")
      (footprint "eagle-import:RESC1005X40")
      (libsource (lib "eagle-import") (part "R-USCHIP-0402(1005-METRIC)_"))
    )
    (comp (ref "R4")
      (value "200K")
      (footprint "eagle-import:RESC1005X40")
      (libsource (lib "eagle-import") (part "R-USCHIP-0402(1005-METRIC)_"))
    )
    (comp (ref "R5")
      (value "1K")
      (footprint "eagle-import:RESC1005X40")
      (libsource (lib "eagle-import") (part "R-USCHIP-0402(1005-METRIC)_"))
    )
    (comp (ref "R6")
      (value "590")
      (footprint "eagle-import:RESC1005X40")
      (libsource (lib "eagle-import") (part "R-USCHIP-0402(1005-METRIC)_"))
    )
    (comp (ref "R7")
      (value "1.1k")
      (footprint "eagle-import:RESC1005X40")
      (libsource (lib "eagle-import") (part "R-USCHIP-0402(1005-METRIC)_"))
    )
    (comp (ref "R8")
      (value "1k")
      (footprint "eagle-import:RESC1005X40")
      (libsource (lib "eagle-import") (part "R-USCHIP-0402(1005-METRIC)_"))
    )
    (comp (ref "R9")
      (value "0.47")
      (footprint "eagle-import:RESC1005X40")
      (libsource (lib "eagle-import") (part "R-USCHIP-0402(1005-METRIC)_"))
    )
    (comp (ref "R10")
      (value "1k")
      (footprint "eagle-import:RESC1005X40")
      (libsource (lib "eagle-import") (part "R-USCHIP-0402(1005-METRIC)_"))
    )
    (comp (ref "R11")
      (value "10K")
      (footprint "eagle-import:RESC1005X40")
      (libsource (lib "eagle-import") (part "R-USCHIP-0402(1005-METRIC)_"))
    )
    (comp (ref "R12")
      (value "0.01")
      (footprint "eagle-import:1206")
      (libsource (lib "eagle-import") (part "RESISTOR1206"))
    )
    (comp (ref "R13")
      (value "200K")
      (footprint "eagle-import:RESC1005X40")
      (libsource (lib "eagle-import") (part "R-USCHIP-0402(1005-METRIC)_"))
    )
    (comp (ref "R14")
      (value "1K")
      (footprint "eagle-import:RESC1005X40")
      (libsource (lib "eagle-import") (part "R-USCHIP-0402(1005-METRIC)_"))
    )
    (comp (ref "R15")
      (value "4.7K")
      (footprint "eagle-import:RESC1005X40")
      (libsource (lib "eagle-import") (part "R-USCHIP-0402(1005-METRIC)_"))
    )
    (comp (ref "R16")
      (value "10k")
      (footprint "eagle-import:RESC1005X40")
      (libsource (lib "eagle-import") (part "R-USCHIP-0402(1005-METRIC)_"))
    )
    (comp (ref "R17")
      (value "10k")
      (footprint "eagle-import:RESC1005X40")
      (libsource (lib "eagle-import") (part "R-USCHIP-0402(1005-METRIC)_"))
    )
    (comp (ref "R18")
      (value "4.7K")
      (footprint "eagle-import:RESC1005X40")
      (libsource (lib "eagle-import") (part "R-USCHIP-0402(1005-METRIC)_"))
    )
    (comp (ref "R19")
      (value "5.1K")
      (footprint "eagle-import:RESC1005X40")
      (libsource (lib "eagle-import") (part "R-USCHIP-0402(1005-METRIC)_"))
    )
    (comp (ref "R20")
      (value "1K")
      (footprint "eagle-import:RESC1005X40")
      (libsource (lib "eagle-import") (part "R-USCHIP-0402(1005-METRIC)_"))
    )
    (comp (ref "R21")
      (value "5.1k")
      (footprint "eagle-import:RESC1005X40")
      (libsource (lib "eagle-import") (part "R-USCHIP-0402(1005-METRIC)_"))
    )
    (comp (ref "R22")
      (value "180")
      (footprint "eagle-import:RESC1005X40")
      (libsource (lib "eagle-import") (part "R-USCHIP-0402(1005-METRIC)_"))
    )
    (comp (ref "R23")
      (value "1K")
      (footprint "eagle-import:RESC1005X40")
      (libsource (lib "eagle-import") (part "R-USCHIP-0402(1005-METRIC)_"))
    )
    (comp (ref "R24")
      (value "100k")
      (footprint "eagle-import:RESC1005X40")
      (libsource (lib "eagle-import") (part "R-USCHIP-0402(1005-METRIC)_"))
    )
    (comp (ref "R25")
      (value "4.7K")
      (footprint "eagle-import:RESC1005X40")
      (libsource (lib "eagle-import") (part "R-USCHIP-0402(1005-METRIC)_"))
    )
    (comp (ref "R26")
      (value "4.7K")
      (footprint "eagle-import:RESC1005X40")
      (libsource (lib "eagle-import") (part "R-USCHIP-0402(1005-METRIC)_"))
    )
    (comp (ref "R27")
      (value "10k")
      (footprint "eagle-import:RESC1005X40")
      (libsource (lib "eagle-import") (part "R-USCHIP-0402(1005-METRIC)_"))
    )
    (comp (ref "R28")
      (value "10k")
      (footprint "eagle-import:RESC1005X40")
      (libsource (lib "eagle-import") (part "R-USCHIP-0402(1005-METRIC)_"))
    )
    (comp (ref "R30")
      (value "36k")
      (footprint "eagle-import:RESC1005X40")
      (libsource (lib "eagle-import") (part "R-USCHIP-0402(1005-METRIC)_"))
    )
    (comp (ref "R31")
      (value "27")
      (footprint "eagle-import:RESC1005X40")
      (libsource (lib "eagle-import") (part "R-USCHIP-0402(1005-METRIC)_"))
    )
    (comp (ref "R32")
      (value "27")
      (footprint "eagle-import:RESC1005X40")
      (libsource (lib "eagle-import") (part "R-USCHIP-0402(1005-METRIC)_"))
    )
    (comp (ref "R33")
      (value "10K")
      (footprint "eagle-import:RESC1005X40")
      (libsource (lib "eagle-import") (part "R-USCHIP-0402(1005-METRIC)_"))
    )
    (comp (ref "R34")
      (value "1k")
      (footprint "eagle-import:RESC1005X40")
      (libsource (lib "eagle-import") (part "R-USCHIP-0402(1005-METRIC)_"))
    )
    (comp (ref "R35")
      (value "1k")
      (footprint "eagle-import:RESC1005X40")
      (libsource (lib "eagle-import") (part "R-USCHIP-0402(1005-METRIC)_"))
    )
    (comp (ref "R36")
      (value "200K")
      (footprint "eagle-import:RESC1005X40")
      (libsource (lib "eagle-import") (part "R-USCHIP-0402(1005-METRIC)_"))
    )
    (comp (ref "R37")
      (value "10k")
      (footprint "eagle-import:RESC1005X40")
      (libsource (lib "eagle-import") (part "R-USCHIP-0402(1005-METRIC)_"))
    )
    (comp (ref "R38")
      (value "4.7k")
      (footprint "eagle-import:RESC1005X40")
      (libsource (lib "eagle-import") (part "R-USCHIP-0402(1005-METRIC)_"))
    )
    (comp (ref "R39")
      (value "10k")
      (footprint "eagle-import:RESC1005X40")
      (libsource (lib "eagle-import") (part "R-USCHIP-0402(1005-METRIC)_"))
    )
    (comp (ref "R40")
      (value "4.7K")
      (footprint "eagle-import:RESC1005X40")
      (libsource (lib "eagle-import") (part "R-USCHIP-0402(1005-METRIC)_"))
    )
    (comp (ref "R41")
      (value "47K")
      (footprint "eagle-import:RESC1005X40")
      (libsource (lib "eagle-import") (part "R-USCHIP-0402(1005-METRIC)_"))
    )
    (comp (ref "R42")
      (value "4.7K")
      (footprint "eagle-import:RESC1005X40")
      (libsource (lib "eagle-import") (part "R-USCHIP-0402(1005-METRIC)_"))
    )
    (comp (ref "R43")
      (value "10K")
      (footprint "eagle-import:RESC1005X40")
      (libsource (lib "eagle-import") (part "R-USCHIP-0402(1005-METRIC)_"))
    )
    (comp (ref "R44")
      (value "6.57k")
      (footprint "eagle-import:RESC1005X40")
      (libsource (lib "eagle-import") (part "R-USCHIP-0402(1005-METRIC)_"))
    )
    (comp (ref "RPI-CM1")
      (value "DF40C-100DS-0.4V(51)")
      (footprint "eagle-import:RPI-CM4")
      (libsource (lib "eagle-import") (part "RPI-CM4"))
    )
    (comp (ref "RPIBOOT")
      (value "DNP")
      (footprint "eagle-import:PAD.03X.03")
      (libsource (lib "eagle-import") (part "TEST-POINT3"))
    )
    (comp (ref "RPIBOOT1")
      (value "DNP")
      (footprint "eagle-import:PAD.03X.03")
      (libsource (lib "eagle-import") (part "TEST-POINT3"))
    )
    (comp (ref "RPIBOOT2")
      (value "DNP")
      (footprint "eagle-import:PAD.03X.03")
      (libsource (lib "eagle-import") (part "TEST-POINT3"))
    )
    (comp (ref "RPIBOOT3")
      (value "DNP")
      (footprint "eagle-import:PAD.03X.03")
      (libsource (lib "eagle-import") (part "TEST-POINT3"))
    )
    (comp (ref "RPIBOOT4")
      (value "DNP")
      (footprint "eagle-import:PAD.03X.03")
      (libsource (lib "eagle-import") (part "TEST-POINT3"))
    )
    (comp (ref "RPIBOOT5")
      (value "TEST-POINT3")
      (footprint "eagle-import:PAD.03X.03")
      (libsource (lib "eagle-import") (part "TEST-POINT3"))
    )
    (comp (ref "RPIBOOT6")
      (value "DNP")
      (footprint "eagle-import:PAD.03X.03")
      (libsource (lib "eagle-import") (part "TEST-POINT3"))
    )
    (comp (ref "RPIBOOT7")
      (value "TEST-POINT3")
      (footprint "eagle-import:PAD.03X.03")
      (libsource (lib "eagle-import") (part "TEST-POINT3"))
    )
    (comp (ref "RPIBOOT8")
      (value "DNP")
      (footprint "eagle-import:PAD.03X.03")
      (libsource (lib "eagle-import") (part "TEST-POINT3"))
    )
    (comp (ref "RPIBOOT9")
      (value "DNP")
      (footprint "eagle-import:PAD.03X.03")
      (libsource (lib "eagle-import") (part "TEST-POINT3"))
    )
    (comp (ref "RPIBOOT10")
      (value "DNP")
      (footprint "eagle-import:PAD.03X.03")
      (libsource (lib "eagle-import") (part "TEST-POINT3"))
    )
    (comp (ref "RPIBOOT11")
      (value "DNP")
      (footprint "eagle-import:PAD.03X.03")
      (libsource (lib "eagle-import") (part "TEST-POINT3"))
    )
    (comp (ref "RPIBOOT12")
      (value "DNP")
      (footprint "eagle-import:PAD.03X.03")
      (libsource (lib "eagle-import") (part "TEST-POINT3"))
    )
    (comp (ref "SJ1")
      (value "DNP")
      (footprint "eagle-import:PAD-JUMPER-2-NC_BY_TRACE_YES_SILK")
      (libsource (lib "eagle-import") (part "JUMPER-PAD-2-NC_BY_TRACE"))
    )
    (comp (ref "SJ6")
      (value "DNP")
      (footprint "eagle-import:PAD-JUMPER-2-NC_BY_TRACE_YES_SILK")
      (libsource (lib "eagle-import") (part "JUMPER-PAD-2-NC_BY_TRACE"))
    )
    (comp (ref "T1")
      (value "MMUN2133LT1G")
      (footprint "eagle-import:SC59-BEC")
      (libsource (lib "eagle-import") (part "-PNP_DRIVER-SC59-BECMUN2114T1"))
    )
    (comp (ref "U1")
      (value "TPS61092RSAR")
      (footprint "eagle-import:PVQFN-16")
      (libsource (lib "eagle-import") (part "VREG_TPS6103X"))
    )
    (comp (ref "U2")
      (value "MC74VHC1G14DFT1G")
      (footprint "eagle-import:SOT65P210X110-5N")
      (fields (field (name "MF") "ON Semiconductor"))
      (libsource (lib "eagle-import") (part "MC74VHC1G14DFT1G"))
    )
    (comp (ref "U3")
      (value "BQ27441DRZR-G1A")
      (footprint "eagle-import:PDSO-N12")
      (libsource (lib "eagle-import") (part "BQ27441-G1"))
    )
    (comp (ref "U4")
      (value "BQ24075")
      (footprint "eagle-import:PVQFN-N16")
      (libsource (lib "eagle-import") (part "BQ24075"))
    )
    (comp (ref "U5")
      (value "MC74VHC1G14DFT1G OR C66196")
      (footprint "eagle-import:SOT65P210X110-5N")
      (fields (field (name "MF") "ON Semiconductor") (field (name "MP") "MC74VHC1G14DFT1G"))
      (libsource (lib "eagle-import") (part "MC74VHC1G14DFT1G"))
    )
    (comp (ref "U6")
      (value "LSM6DS3")
      (footprint "eagle-import:LGA-14L")
      (libsource (lib "eagle-import") (part "LSM6DS3"))
    )
    (comp (ref "U7")
      (value "SN74LVC244ARWPRRWP0020A")
      (footprint "eagle-import:RWP0020A")
      (fields
        (field (name "MANUFACTURER_PART_NUMBER") "SN74LVC244ARWPR")
        (field (name "COPYRIGHT") "Copyright (C) 2024 Ultra Librarian. All rights reserved.")
      )
      (libsource (lib "eagle-import") (part "SN74LVC244ARWPRRWP0020A"))
    )
    (comp (ref "U9")
      (value "EMC2301-1-ACZL-TRMSOP8_MC_MCH-L")
      (footprint "eagle-import:MSOP8_MC_MCH-L")
      (fields
        (field (name "MANUFACTURER_PART_NUMBER") "EMC2301-1-ACZL-TR")
        (field (name "COPYRIGHT") "Copyright (C) 2024 Ultra Librarian. All rights reserved.")
      )
      (libsource (lib "eagle-import") (part "EMC2301-1-ACZL-TRMSOP8_MC_MCH-L"))
    )
    (comp (ref "U10")
      (value "AP2112-3.3K")
      (footprint "eagle-import:SOT23-5")
      (libsource (lib "eagle-import") (part "VREG_SOT23-5"))
    )
    (comp (ref "U11")
      (value "AP2112-3.3K")
      (footprint "eagle-import:SOT23-5")
      (libsource (lib "eagle-import") (part "VREG_SOT23-5"))
    )
    (comp (ref "U12")
      (value "C233266")
      (footprint "eagle-import:XDCR_SPU0410LR5H-QB")
      (fields (field (name "MANUFACTURER") "KNOWLES"))
      (libsource (lib "eagle-import") (part "SPU0410LR5H-QB"))
    )
    (comp (ref "U13")
      (value "TPD4EUSB30DQARDQA10")
      (footprint "eagle-import:DQA10")
      (fields
        (field (name "MANUFACTURER_PART_NUMBER") "TPD4EUSB30DQAR")
        (field (name "COPYRIGHT") "Copyright (C) 2024 Ultra Librarian. All rights reserved.")
      )
      (libsource (lib "eagle-import") (part "TPD4EUSB30DQARDQA10"))
    )
    (comp (ref "U14")
      (value "OPA344")
      (footprint "eagle-import:SOT23-5")
      (libsource (lib "eagle-import") (part "OPA344"))
    )
    (comp (ref "U15")
      (value "AP2112-3.3K")
      (footprint "eagle-import:SOT23-5")
      (libsource (lib "eagle-import") (part "VREG_SOT23-5"))
    )
    (comp (ref "U16")
      (value "W25Q16JVUXIQ_TR")
      (footprint "eagle-import:PSON50P300X200X60-9N")
      (fields (field (name "MANUFACTURER") "Winbond"))
      (libsource (lib "eagle-import") (part "W25Q16JVUXIQ_TR"))
    )
    (comp (ref "U17")
      (value "TPD1E1B04DPYRDPY2_TEX")
      (footprint "eagle-import:DPY2_TEX")
      (fields
        (field (name "MANUFACTURER_PART_NUMBER") "TPD1E1B04DPYR")
        (field (name "COPYRIGHT") "Copyright (C) 2024 Ultra Librarian. All rights reserved.")
      )
      (libsource (lib "eagle-import") (part "TPD1E1B04DPYRDPY2_TEX"))
    )
    (comp (ref "U18")
      (value "TPD1E1B04DPYRDPY2_TEX")
      (footprint "eagle-import:DPY2_TEX")
      (fields
        (field (name "MANUFACTURER_PART_NUMBER") "TPD1E1B04DPYR")
        (field (name "COPYRIGHT") "Copyright (C) 2024 Ultra Librarian. All rights reserved.")
      )
      (libsource (lib "eagle-import") (part "TPD1E1B04DPYRDPY2_TEX"))
    )
    (comp (ref "U19")
      (value "TPD1E1B04DPYRDPY2_TEX")
      (footprint "eagle-import:DPY2_TEX")
      (fields
        (field (name "MANUFACTURER_PART_NUMBER") "TPD1E1B04DPYR")
        (field (name "COPYRIGHT") "Copyright (C) 2024 Ultra Librarian. All rights reserved.")
      )
      (libsource (lib "eagle-import") (part "TPD1E1B04DPYRDPY2_TEX"))
    )
    (comp (ref "U20")
      (value "TPD1E1B04DPYRDPY2_TEX")
      (footprint "eagle-import:DPY2_TEX")
      (fields
        (field (name "MANUFACTURER_PART_NUMBER") "TPD1E1B04DPYR")
        (field (name "COPYRIGHT") "Copyright (C) 2024 Ultra Librarian. All rights reserved.")
      )
      (libsource (lib "eagle-import") (part "TPD1E1B04DPYRDPY2_TEX"))
    )
    (comp (ref "U21")
      (value "TPD1E1B04DPYRDPY2_TEX")
      (footprint "eagle-import:DPY2_TEX")
      (fields
        (field (name "MANUFACTURER_PART_NUMBER") "TPD1E1B04DPYR")
        (field (name "COPYRIGHT") "Copyright (C) 2024 Ultra Librarian. All rights reserved.")
      )
      (libsource (lib "eagle-import") (part "TPD1E1B04DPYRDPY2_TEX"))
    )
    (comp (ref "U22")
      (value "TPD1E1B04DPYRDPY2_TEX")
      (footprint "eagle-import:DPY2_TEX")
      (fields
        (field (name "MANUFACTURER_PART_NUMBER") "TPD1E1B04DPYR")
        (field (name "COPYRIGHT") "Copyright (C) 2024 Ultra Librarian. All rights reserved.")
      )
      (libsource (lib "eagle-import") (part "TPD1E1B04DPYRDPY2_TEX"))
    )
    (comp (ref "U23")
      (value "TPD1E1B04DPYRDPY2_TEX")
      (footprint "eagle-import:DPY2_TEX")
      (fields
        (field (name "MANUFACTURER_PART_NUMBER") "TPD1E1B04DPYR")
        (field (name "COPYRIGHT") "Copyright (C) 2024 Ultra Librarian. All rights reserved.")
      )
      (libsource (lib "eagle-import") (part "TPD1E1B04DPYRDPY2_TEX"))
    )
    (comp (ref "U24")
      (value "TPD1E1B04DPYRDPY2_TEX")
      (footprint "eagle-import:DPY2_TEX")
      (fields
        (field (name "MANUFACTURER_PART_NUMBER") "TPD1E1B04DPYR")
        (field (name "COPYRIGHT") "Copyright (C) 2024 Ultra Librarian. All rights reserved.")
      )
      (libsource (lib "eagle-import") (part "TPD1E1B04DPYRDPY2_TEX"))
    )
    (comp (ref "U25")
      (value "DRV2605LDGSR")
      (footprint "eagle-import:SOP50P490X110-10N")
      (fields (field (name "MANUFACTURER") "Texas Instruments"))
      (libsource (lib "eagle-import") (part "DRV2605LDGSR"))
    )
    (comp (ref "USB2.0MUX")
      (value "TS3USB30RSWR")
      (footprint "eagle-import:10-UFQFN")
      (fields (field (name "DIGI-KEY_PART_NUMBER") "296-22547-2-ND") (field (name "MF") "Texas Instruments"))
      (libsource (lib "eagle-import") (part "TS3USB30RSWR"))
    )
    (comp (ref "USB_BOOT_N")
      (value "DNP")
      (footprint "eagle-import:PAD.03X.03")
      (libsource (lib "eagle-import") (part "TEST-POINT3"))
    )
    (comp (ref "Y1")
      (value "ABM8-272-T3")
      (footprint "eagle-import:ABM8272T3")
      (fields (field (name "MOUSER_PART_NUMBER") "815-ABM8-272-T3"))
      (libsource (lib "eagle-import") (part "ABM8-272-T3"))
    )
  )
  (nets
    (net (code "1") (name "/1V8BQ") (class "Default")
      (node (ref "C20") (pin "1") (pinfunction "1_1") (pintype "passive"))
      (node (ref "U3") (pin "5") (pinfunction "VDD_5") (pintype "bidirectional"))
    )
    (net (code "2") (name "/2A3") (class "Default")
      (node (ref "U7") (pin "14") (pinfunction "2A3_14") (pintype "input"))
    )
    (net (code "3") (name "/2A4") (class "Default")
      (node (ref "U7") (pin "16") (pinfunction "2A4_16") (pintype "input"))
    )
    (net (code "4") (name "/2Y3") (class "Default")
      (node (ref "U7") (pin "4") (pinfunction "2Y3_4") (pintype "output"))
    )
    (net (code "5") (name "/2Y4") (class "Default")
      (node (ref "U7") (pin "2") (pinfunction "2Y4_2") (pintype "output"))
    )
    (net (code "6") (name "/AUDIO_MCLK") (class "Default")
      (node (ref "IC3") (pin "11") (pinfunction "MCLK_11") (pintype "input"))
      (node (ref "OSC2") (pin "3") (pinfunction "OUT_3") (pintype "output"))
    )
    (net (code "7") (name "/BUTTON_D") (class "Default")
      (node (ref "BUD") (pin "2_1") (pinfunction "2_2_1") (pintype "passive"))
      (node (ref "BUD") (pin "2_2") (pinfunction "2_2_2") (pintype "passive"))
      (node (ref "C2040") (pin "29") (pinfunction "GPIO18_29") (pintype "bidirectional"))
    )
    (net (code "8") (name "/BUTTON_S") (class "Default")
      (node (ref "BUS") (pin "2_1") (pinfunction "2_2_1") (pintype "passive"))
      (node (ref "BUS") (pin "2_2") (pinfunction "2_2_2") (pintype "passive"))
      (node (ref "C2040") (pin "27") (pinfunction "GPIO16_27") (pintype "bidirectional"))
    )
    (net (code "9") (name "/BUTTON_U") (class "Default")
      (node (ref "BUP") (pin "2_1") (pinfunction "2_2_1") (pintype "passive"))
      (node (ref "BUP") (pin "2_2") (pinfunction "2_2_2") (pintype "passive"))
      (node (ref "C2040") (pin "28") (pinfunction "GPIO17_28") (pintype "bidirectional"))
    )
    (net (code "10") (name "/CAM0_C_N") (class "Default")
      (node (ref "RPI-CM1") (pin "140") (pinfunction "CAM0_C_N_140") (pintype "passive"))
    )
    (net (code "11") (name "/CAM0_C_P") (class "Default")
      (node (ref "RPI-CM1") (pin "142") (pinfunction "CAM0_C_P_142") (pintype "passive"))
    )
    (net (code "12") (name "/CAM0_D0_N") (class "Default")
      (node (ref "RPI-CM1") (pin "128") (pinfunction "CAM0_D0_N_128") (pintype "passive"))
    )
    (net (code "13") (name "/CAM0_D0_P") (class "Default")
      (node (ref "RPI-CM1") (pin "130") (pinfunction "CAM0_D0_P_130") (pintype "passive"))
    )
    (net (code "14") (name "/CAM0_D1_N") (class "Default")
      (node (ref "RPI-CM1") (pin "134") (pinfunction "CAM0_D1_N_134") (pintype "passive"))
    )
    (net (code "15") (name "/CAM0_D1_P") (class "Default")
      (node (ref "RPI-CM1") (pin "136") (pinfunction "CAM0_D1_P_136") (pintype "passive"))
    )
    (net (code "16") (name "/CAM1_C_N") (class "Default")
      (node (ref "CAMERA") (pin "8") (pinfunction "8_8") (pintype "passive"))
      (node (ref "RPI-CM1") (pin "127") (pinfunction "CAM1_C_N_127") (pintype "passive"))
    )
    (net (code "17") (name "/CAM1_C_P") (class "Default")
      (node (ref "CAMERA") (pin "9") (pinfunction "9_9") (pintype "passive"))
      (node (ref "RPI-CM1") (pin "129") (pinfunction "CAM1_C_P_129") (pintype "passive"))
    )
    (net (code "18") (name "/CAM1_D0_N") (class "Default")
      (node (ref "CAMERA") (pin "2") (pinfunction "2_2") (pintype "passive"))
      (node (ref "RPI-CM1") (pin "115") (pinfunction "CAM1_D0_N_115") (pintype "passive"))
    )
    (net (code "19") (name "/CAM1_D0_P") (class "Default")
      (node (ref "CAMERA") (pin "3") (pinfunction "3_3") (pintype "passive"))
      (node (ref "RPI-CM1") (pin "117") (pinfunction "CAM1_D0_P_117") (pintype "passive"))
    )
    (net (code "20") (name "/CAM1_D1_N") (class "Default")
      (node (ref "CAMERA") (pin "5") (pinfunction "5_5") (pintype "passive"))
      (node (ref "RPI-CM1") (pin "121") (pinfunction "CAM1_D1_N_121") (pintype "passive"))
    )
    (net (code "21") (name "/CAM1_D1_P") (class "Default")
      (node (ref "CAMERA") (pin "6") (pinfunction "6_6") (pintype "passive"))
      (node (ref "RPI-CM1") (pin "123") (pinfunction "CAM1_D1_P_123") (pintype "passive"))
    )
    (net (code "22") (name "/CAM1_D2_N") (class "Default")
      (node (ref "CAMERA") (pin "11") (pinfunction "11_11") (pintype "passive"))
      (node (ref "RPI-CM1") (pin "133") (pinfunction "CAM1_D2_N_133") (pintype "passive"))
    )
    (net (code "23") (name "/CAM1_D2_P") (class "Default")
      (node (ref "CAMERA") (pin "12") (pinfunction "12_12") (pintype "passive"))
      (node (ref "RPI-CM1") (pin "135") (pinfunction "CAM1_D2_P_135") (pintype "passive"))
    )
    (net (code "24") (name "/CAM1_D3_N") (class "Default")
      (node (ref "CAMERA") (pin "14") (pinfunction "14_14") (pintype "passive"))
      (node (ref "RPI-CM1") (pin "139") (pinfunction "CAM1_D3_N_139") (pintype "passive"))
    )
    (net (code "25") (name "/CAM1_D3_P") (class "Default")
      (node (ref "CAMERA") (pin "15") (pinfunction "15_15") (pintype "passive"))
      (node (ref "RPI-CM1") (pin "141") (pinfunction "CAM1_D3_P_141") (pintype "passive"))
    )
    (net (code "26") (name "/CAM_GPIO") (class "Default")
      (node (ref "CAMERA") (pin "17") (pinfunction "17_17") (pintype "passive"))
      (node (ref "RPI-CM1") (pin "97") (pinfunction "CAMERA_GPIO_97") (pintype "passive"))
    )
    (net (code "27") (name "/CDD") (class "Default")
      (node (ref "C10") (pin "1") (pinfunction "1_1") (pintype "passive"))
      (node (ref "EINK_524352471") (pin "7") (pinfunction "7_7") (pintype "passive"))
    )
    (net (code "28") (name "/DSI0_C_N") (class "Default")
      (node (ref "RPI-CM1") (pin "169") (pinfunction "DSI0_C_N_169") (pintype "passive"))
    )
    (net (code "29") (name "/DSI0_C_P") (class "Default")
      (node (ref "RPI-CM1") (pin "171") (pinfunction "DSI0_C_P_171") (pintype "passive"))
    )
    (net (code "30") (name "/DSI0_D0_N") (class "Default")
      (node (ref "RPI-CM1") (pin "157") (pinfunction "DSI0_D0_N_157") (pintype "passive"))
    )
    (net (code "31") (name "/DSI0_D0_P") (class "Default")
      (node (ref "RPI-CM1") (pin "159") (pinfunction "DSI0_D0_P_159") (pintype "passive"))
    )
    (net (code "32") (name "/DSI0_D1_N") (class "Default")
      (node (ref "RPI-CM1") (pin "163") (pinfunction "DSI0_D1_N_163") (pintype "passive"))
    )
    (net (code "33") (name "/DSI0_D1_P") (class "Default")
      (node (ref "RPI-CM1") (pin "165") (pinfunction "DSI0_D1_P_165") (pintype "passive"))
    )
    (net (code "34") (name "/DSI1_C_N") (class "Default")
      (node (ref "RPI-CM1") (pin "187") (pinfunction "DSI1_C_N_187") (pintype "passive"))
    )
    (net (code "35") (name "/DSI1_C_P") (class "Default")
      (node (ref "RPI-CM1") (pin "189") (pinfunction "DSI1_C_P_189") (pintype "passive"))
    )
    (net (code "36") (name "/DSI1_D0_N") (class "Default")
      (node (ref "RPI-CM1") (pin "175") (pinfunction "DSI1_D0_N_175") (pintype "passive"))
    )
    (net (code "37") (name "/DSI1_D0_P") (class "Default")
      (node (ref "RPI-CM1") (pin "177") (pinfunction "DSI1_D0_P_177") (pintype "passive"))
    )
    (net (code "38") (name "/DSI1_D1_N") (class "Default")
      (node (ref "RPI-CM1") (pin "181") (pinfunction "DSI1_D1_N_181") (pintype "passive"))
    )
    (net (code "39") (name "/DSI1_D1_P") (class "Default")
      (node (ref "RPI-CM1") (pin "183") (pinfunction "DSI1_D1_P_183") (pintype "passive"))
    )
    (net (code "40") (name "/DSI1_D2_N") (class "Default")
      (node (ref "RPI-CM1") (pin "193") (pinfunction "DSI1_D2_N_193") (pintype "passive"))
    )
    (net (code "41") (name "/DSI1_D2_P") (class "Default")
      (node (ref "RPI-CM1") (pin "195") (pinfunction "DSI1_D2_P_195") (pintype "passive"))
    )
    (net (code "42") (name "/DSI1_D3_N") (class "Default")
      (node (ref "RPI-CM1") (pin "194") (pinfunction "DSI1_D3_N_194") (pintype "passive"))
    )
    (net (code "43") (name "/DSI1_D3_P") (class "Default")
      (node (ref "RPI-CM1") (pin "196") (pinfunction "DSI1_D3_P_196") (pintype "passive"))
    )
    (net (code "44") (name "/EINK_BUSY") (class "Default")
      (node (ref "C2040") (pin "13") (pinfunction "GPIO10_13") (pintype "bidirectional"))
      (node (ref "EINK_524352471") (pin "16") (pinfunction "16_16") (pintype "passive"))
      (node (ref "RPIBOOT9") (pin "P$1") (pinfunction "1_P$1") (pintype "bidirectional"))
      (node (ref "U18") (pin "2") (pinfunction "I/O_2") (pintype "passive"))
      (node (ref "U7") (pin "1") (pinfunction "1A1_1") (pintype "input"))
    )
    (net (code "45") (name "/EINK_CS") (class "Default")
      (node (ref "C2040") (pin "16") (pinfunction "GPIO13_16") (pintype "bidirectional"))
      (node (ref "EINK_524352471") (pin "13") (pinfunction "13_13") (pintype "passive"))
      (node (ref "GND41") (pin "P$1") (pinfunction "1_P$1") (pintype "bidirectional"))
      (node (ref "U20") (pin "2") (pinfunction "I/O_2") (pintype "passive"))
      (node (ref "U7") (pin "11") (pinfunction "1Y4_11") (pintype "output"))
    )
    (net (code "46") (name "/EINK_D{slash}C") (class "Default")
      (node (ref "C2040") (pin "15") (pinfunction "GPIO12_15") (pintype "bidirectional"))
      (node (ref "EINK_524352471") (pin "14") (pinfunction "14_14") (pintype "passive"))
      (node (ref "RPIBOOT10") (pin "P$1") (pinfunction "1_P$1") (pintype "bidirectional"))
      (node (ref "U19") (pin "2") (pinfunction "I/O_2") (pintype "passive"))
      (node (ref "U7") (pin "13") (pinfunction "1Y3_13") (pintype "output"))
    )
    (net (code "47") (name "/EINK_RESET") (class "Default")
      (node (ref "C2040") (pin "14") (pinfunction "GPIO11_14") (pintype "bidirectional"))
      (node (ref "EINK_524352471") (pin "15") (pinfunction "15_15") (pintype "passive"))
      (node (ref "GND40") (pin "P$1") (pinfunction "1_P$1") (pintype "bidirectional"))
      (node (ref "U17") (pin "2") (pinfunction "I/O_2") (pintype "passive"))
      (node (ref "U7") (pin "15") (pinfunction "1Y2_15") (pintype "output"))
    )
    (net (code "48") (name "/FAN_PWM") (class "Default")
      (node (ref "J3") (pin "1") (pinfunction "1_1") (pintype "passive"))
      (node (ref "U9") (pin "5") (pinfunction "PWM_5") (pintype "output"))
    )
    (net (code "49") (name "/GDR") (class "Default")
      (node (ref "EINK_524352471") (pin "23") (pinfunction "23_23") (pintype "passive"))
      (node (ref "Q1") (pin "1") (pinfunction "G_1") (pintype "bidirectional"))
      (node (ref "R11") (pin "2") (pinfunction "2_2") (pintype "passive"))
    )
    (net (code "50") (name "/GND_2") (class "Default")
      (node (ref "U13") (pin "3") (pinfunction "GND_2_3") (pintype "power_in"))
    )
    (net (code "51") (name "/HDMI0_CEC") (class "Default")
      (node (ref "RPI-CM1") (pin "151") (pinfunction "HDMI0_CEC_151") (pintype "passive"))
    )
    (net (code "52") (name "/HDMI0_CLK_N") (class "Default")
      (node (ref "RPI-CM1") (pin "190") (pinfunction "HDMI0_CLK_N_190") (pintype "passive"))
    )
    (net (code "53") (name "/HDMI0_CLK_P") (class "Default")
      (node (ref "RPI-CM1") (pin "188") (pinfunction "HDMI0_CLK_P_188") (pintype "passive"))
    )
    (net (code "54") (name "/HDMI0_HOTPLUG") (class "Default")
      (node (ref "RPI-CM1") (pin "153") (pinfunction "HDMI0_HOTPLUG_153") (pintype "passive"))
    )
    (net (code "55") (name "/HDMI0_SCL") (class "Default")
      (node (ref "RPI-CM1") (pin "200") (pinfunction "HDMI0_SCL_200") (pintype "passive"))
    )
    (net (code "56") (name "/HDMI0_SDA") (class "Default")
      (node (ref "RPI-CM1") (pin "199") (pinfunction "HDMI0_SDA_199") (pintype "passive"))
    )
    (net (code "57") (name "/HDMI0_TX0_N") (class "Default")
      (node (ref "RPI-CM1") (pin "184") (pinfunction "HDMI0_TX0_N_184") (pintype "passive"))
    )
    (net (code "58") (name "/HDMI0_TX0_P") (class "Default")
      (node (ref "RPI-CM1") (pin "182") (pinfunction "HDMI0_TX0_P_182") (pintype "passive"))
    )
    (net (code "59") (name "/HDMI0_TX1_N") (class "Default")
      (node (ref "RPI-CM1") (pin "178") (pinfunction "HDMI0_TX1_N_178") (pintype "passive"))
    )
    (net (code "60") (name "/HDMI0_TX1_P") (class "Default")
      (node (ref "RPI-CM1") (pin "176") (pinfunction "HDMI0_TX1_P_176") (pintype "passive"))
    )
    (net (code "61") (name "/HDMI0_TX2_N") (class "Default")
      (node (ref "RPI-CM1") (pin "172") (pinfunction "HDMI0_TX2_N_172") (pintype "passive"))
    )
    (net (code "62") (name "/HDMI0_TX2_P") (class "Default")
      (node (ref "RPI-CM1") (pin "170") (pinfunction "HDMI0_TX2_P_170") (pintype "passive"))
    )
    (net (code "63") (name "/HDMI1_CEC") (class "Default")
      (node (ref "RPI-CM1") (pin "149") (pinfunction "HDMI1_CEC_149") (pintype "passive"))
    )
    (net (code "64") (name "/HDMI1_CLK_N") (class "Default")
      (node (ref "RPI-CM1") (pin "166") (pinfunction "HDMI1_CLK_N_166") (pintype "passive"))
    )
    (net (code "65") (name "/HDMI1_CLK_P") (class "Default")
      (node (ref "RPI-CM1") (pin "164") (pinfunction "HDMI1_CLK_P_164") (pintype "passive"))
    )
    (net (code "66") (name "/HDMI1_HOTPLUG") (class "Default")
      (node (ref "RPI-CM1") (pin "143") (pinfunction "HDMI1_HOTPLUG_143") (pintype "passive"))
    )
    (net (code "67") (name "/HDMI1_SCL") (class "Default")
      (node (ref "RPI-CM1") (pin "147") (pinfunction "HDMI1_SCL_147") (pintype "passive"))
    )
    (net (code "68") (name "/HDMI1_SDA") (class "Default")
      (node (ref "RPI-CM1") (pin "145") (pinfunction "HDMI1_SDA_145") (pintype "passive"))
    )
    (net (code "69") (name "/HDMI1_TX0_N") (class "Default")
      (node (ref "RPI-CM1") (pin "160") (pinfunction "HDMI1_TX0_N_160") (pintype "passive"))
    )
    (net (code "70") (name "/HDMI1_TX0_P") (class "Default")
      (node (ref "RPI-CM1") (pin "158") (pinfunction "HDMI1_TX0_P_158") (pintype "passive"))
    )
    (net (code "71") (name "/HDMI1_TX1_N") (class "Default")
      (node (ref "RPI-CM1") (pin "154") (pinfunction "HDMI1_TX1_N_154") (pintype "passive"))
    )
    (net (code "72") (name "/HDMI1_TX1_P") (class "Default")
      (node (ref "RPI-CM1") (pin "152") (pinfunction "HDMI1_TX1_P_152") (pintype "passive"))
    )
    (net (code "73") (name "/HDMI1_TX2_N") (class "Default")
      (node (ref "RPI-CM1") (pin "148") (pinfunction "HDMI1_TX2_N_148") (pintype "passive"))
    )
    (net (code "74") (name "/HDMI1_TX2_P") (class "Default")
      (node (ref "RPI-CM1") (pin "146") (pinfunction "HDMI1_TX2_P_146") (pintype "passive"))
    )
    (net (code "75") (name "/I2S_BCLK") (class "Default")
      (node (ref "IC3") (pin "12") (pinfunction "BCLK_12") (pintype "bidirectional"))
      (node (ref "RPI-CM1") (pin "49") (pinfunction "GPIO18_49") (pintype "passive"))
    )
    (net (code "76") (name "/I2S_DIN") (class "Default")
      (node (ref "IC3") (pin "16") (pinfunction "ADCDAT_16") (pintype "input"))
      (node (ref "RPI-CM1") (pin "27") (pinfunction "GPIO20_27") (pintype "passive"))
    )
    (net (code "77") (name "/I2S_DOUT") (class "Default")
      (node (ref "IC3") (pin "14") (pinfunction "DACDAT_14") (pintype "bidirectional"))
      (node (ref "RPI-CM1") (pin "25") (pinfunction "GPIO21_25") (pintype "passive"))
    )
    (net (code "78") (name "/I2S_LRCLK") (class "Default")
      (node (ref "IC3") (pin "13") (pinfunction "DACLRC_13") (pintype "bidirectional"))
      (node (ref "IC3") (pin "15") (pinfunction "ADCLRC/GPIO1_15") (pintype "bidirectional"))
      (node (ref "RPI-CM1") (pin "26") (pinfunction "GPIO19_26") (pintype "passive"))
    )
    (net (code "79") (name "/LBO") (class "Default")
      (node (ref "T1") (pin "B") (pinfunction "B_B") (pintype "passive"))
      (node (ref "U1") (pin "12") (pinfunction "LBO_12") (pintype "output"))
    )
    (net (code "80") (name "/LEFT_N") (class "Default")
      (node (ref "C64") (pin "1") (pinfunction "1_1") (pintype "passive"))
      (node (ref "FB3") (pin "2") (pinfunction "2_2") (pintype "passive"))
      (node (ref "LS1") (pin "N") (pinfunction "N_N") (pintype "passive"))
    )
    (net (code "81") (name "/LEFT_P") (class "Default")
      (node (ref "C63") (pin "1") (pinfunction "1_1") (pintype "passive"))
      (node (ref "FB2") (pin "2") (pinfunction "2_2") (pintype "passive"))
      (node (ref "LS1") (pin "P") (pinfunction "P_P") (pintype "passive"))
    )
    (net (code "82") (name "/MICBIAS") (class "Default")
      (node (ref "C46") (pin "1") (pinfunction "1_1") (pintype "passive"))
      (node (ref "C48") (pin "1") (pinfunction "1_1") (pintype "passive"))
      (node (ref "IC3") (pin "1") (pinfunction "MICBIAS_1") (pintype "output"))
    )
    (net (code "83") (name "/NC") (class "Default")
      (node (ref "EINK_524352471") (pin "24") (pinfunction "24_24") (pintype "passive"))
    )
    (net (code "84") (name "/N_RPIBOOT") (class "Default")
      (node (ref "RPI-CM1") (pin "93") (pinfunction "~{RPIBOOT}_93") (pintype "passive"))
      (node (ref "RPIBOOT") (pin "P$1") (pinfunction "1_P$1") (pintype "bidirectional"))
    )
    (net (code "85") (name "/PCIE_CLK_N") (class "Default")
      (node (ref "M.2KEYM(NGFF)") (pin "53") (pinfunction "P53_53") (pintype "passive"))
      (node (ref "RPI-CM1") (pin "112") (pinfunction "PCIE_CLK_N_112") (pintype "passive"))
    )
    (net (code "86") (name "/PCIE_CLK_P") (class "Default")
      (node (ref "M.2KEYM(NGFF)") (pin "55") (pinfunction "P55_55") (pintype "passive"))
      (node (ref "RPI-CM1") (pin "110") (pinfunction "PCIE_CLK_P_110") (pintype "passive"))
    )
    (net (code "87") (name "/PCIE_CLK_~{REQ}") (class "Default")
      (node (ref "M.2KEYM(NGFF)") (pin "52") (pinfunction "P52_52") (pintype "passive"))
      (node (ref "RPI-CM1") (pin "102") (pinfunction "PCIE_CLK_~{REQ}_102") (pintype "passive"))
    )
    (net (code "88") (name "/PCIE_RX_N") (class "Default")
      (node (ref "M.2KEYM(NGFF)") (pin "41") (pinfunction "P41_41") (pintype "passive"))
      (node (ref "RPI-CM1") (pin "118") (pinfunction "PCIE_RX_N_118") (pintype "passive"))
    )
    (net (code "89") (name "/PCIE_RX_P") (class "Default")
      (node (ref "M.2KEYM(NGFF)") (pin "43") (pinfunction "P43_43") (pintype "passive"))
      (node (ref "RPI-CM1") (pin "116") (pinfunction "PCIE_RX_P_116") (pintype "passive"))
    )
    (net (code "90") (name "/PCIE_TX_N") (class "Default")
      (node (ref "M.2KEYM(NGFF)") (pin "47") (pinfunction "P47_47") (pintype "passive"))
      (node (ref "RPI-CM1") (pin "124") (pinfunction "PCIE_TX_N_124") (pintype "passive"))
    )
    (net (code "91") (name "/PCIE_TX_P") (class "Default")
      (node (ref "M.2KEYM(NGFF)") (pin "49") (pinfunction "P49_49") (pintype "passive"))
      (node (ref "RPI-CM1") (pin "122") (pinfunction "PCIE_TX_P_122") (pintype "passive"))
    )
    (net (code "92") (name "/PCIE_~{RST}") (class "Default")
      (node (ref "M.2KEYM(NGFF)") (pin "50") (pinfunction "P50_50") (pintype "passive"))
      (node (ref "RPI-CM1") (pin "109") (pinfunction "PCIE_~{RST}_109") (pintype "passive"))
    )
    (net (code "93") (name "/PI_1V8") (class "Default")
      (node (ref "RPI-CM1") (pin "88") (pinfunction "CM4_1.8V(OUTPUT)_88") (pintype "passive"))
      (node (ref "RPI-CM1") (pin "90") (pinfunction "CM4_1.8V(OUTPUT)_90") (pintype "passive"))
    )
    (net (code "94") (name "/RESE") (class "Default")
      (node (ref "EINK_524352471") (pin "22") (pinfunction "22_22") (pintype "passive"))
      (node (ref "Q1") (pin "2") (pinfunction "S_2") (pintype "bidirectional"))
      (node (ref "R9") (pin "2") (pinfunction "2_2") (pintype "passive"))
    )
    (net (code "95") (name "/RESERVED@104") (class "Default")
      (node (ref "RPI-CM1") (pin "104") (pinfunction "RESERVED_104") (pintype "passive"))
    )
    (net (code "96") (name "/RESERVED@106") (class "Default")
      (node (ref "RPI-CM1") (pin "106") (pinfunction "RESERVED_106") (pintype "passive"))
    )
    (net (code "97") (name "/RINPUT1") (class "Default")
      (node (ref "C27") (pin "2") (pinfunction "2_2") (pintype "passive"))
      (node (ref "IC3") (pin "5") (pinfunction "RINPUT1_5") (pintype "input"))
      (node (ref "R39") (pin "1") (pinfunction "1_1") (pintype "passive"))
      (node (ref "U14") (pin "1") (pinfunction "OUT_1") (pintype "output"))
    )
    (net (code "98") (name "/SAM_BOOT") (class "Default")
      (node (ref "Q4") (pin "1") (pinfunction "G_1") (pintype "passive"))
      (node (ref "RPI-CM1") (pin "29") (pinfunction "GPIO16_29") (pintype "passive"))
    )
    (net (code "99") (name "/SAM_EINK_PWR") (class "Default")
      (node (ref "C2040") (pin "12") (pinfunction "GPIO9_12") (pintype "bidirectional"))
      (node (ref "U5") (pin "2") (pinfunction "IN_A_2") (pintype "input"))
    )
    (net (code "100") (name "/SAM_EINK_SWITCH") (class "Default")
      (node (ref "C2040") (pin "34") (pinfunction "GPIO22_34") (pintype "bidirectional"))
      (node (ref "U7") (pin "18") (pinfunction "2OE_N_18") (pintype "input"))
      (node (ref "U7") (pin "20") (pinfunction "1OE_N_20") (pintype "input"))
    )
    (net (code "101") (name "/SAM_GPIO3") (class "Default")
      (node (ref "C2040") (pin "5") (pinfunction "GPIO3_5") (pintype "bidirectional"))
    )
    (net (code "102") (name "/SAM_GPIO4") (class "Default")
      (node (ref "C2040") (pin "6") (pinfunction "GPIO4_6") (pintype "bidirectional"))
    )
    (net (code "103") (name "/SAM_GPIO5") (class "Default")
      (node (ref "C2040") (pin "7") (pinfunction "GPIO5_7") (pintype "bidirectional"))
    )
    (net (code "104") (name "/SAM_GPIO6") (class "Default")
      (node (ref "C2040") (pin "8") (pinfunction "GPIO6_8") (pintype "bidirectional"))
    )
    (net (code "105") (name "/SAM_GPIO7") (class "Default")
      (node (ref "C2040") (pin "9") (pinfunction "GPIO7_9") (pintype "bidirectional"))
    )
    (net (code "106") (name "/SAM_GPIO8") (class "Default")
      (node (ref "C2040") (pin "11") (pinfunction "GPIO8_11") (pintype "bidirectional"))
    )
    (net (code "107") (name "/SAM_GPIO23") (class "Default")
      (node (ref "C2040") (pin "35") (pinfunction "GPIO23_35") (pintype "bidirectional"))
    )
    (net (code "108") (name "/SAM_GPIO26{slash}ADC0") (class "Default")
      (node (ref "C2040") (pin "38") (pinfunction "GPIO26/ADC0_38") (pintype "bidirectional"))
    )
    (net (code "109") (name "/SAM_GPIO27{slash}ADC1") (class "Default")
      (node (ref "C2040") (pin "39") (pinfunction "GPIO27/ADC1_39") (pintype "bidirectional"))
    )
    (net (code "110") (name "/SAM_GPIO28{slash}ADC2") (class "Default")
      (node (ref "C2040") (pin "40") (pinfunction "GPIO28/ADC2_40") (pintype "bidirectional"))
    )
    (net (code "111") (name "/SAM_GPIO29{slash}ADC3") (class "Default")
      (node (ref "C2040") (pin "41") (pinfunction "GPIO29/ADC3_41") (pintype "bidirectional"))
    )
    (net (code "112") (name "/SAM_INTERUPT") (class "Default")
      (node (ref "C2040") (pin "4") (pinfunction "GPIO2_4") (pintype "bidirectional"))
      (node (ref "RPI-CM1") (pin "46") (pinfunction "GPIO22_46") (pintype "passive"))
      (node (ref "RPIBOOT12") (pin "P$1") (pinfunction "1_P$1") (pintype "bidirectional"))
    )
    (net (code "113") (name "/SAM_QSPI_SCLK") (class "Default")
      (node (ref "C2040") (pin "52") (pinfunction "QSPI_SCLK_52") (pintype "bidirectional"))
      (node (ref "U16") (pin "6") (pinfunction "CLK_6") (pintype "input"))
    )
    (net (code "114") (name "/SAM_QSPI_SD0") (class "Default")
      (node (ref "C2040") (pin "53") (pinfunction "QSPI_SD0_53") (pintype "bidirectional"))
      (node (ref "U16") (pin "5") (pinfunction "IO0_5") (pintype "bidirectional"))
    )
    (net (code "115") (name "/SAM_QSPI_SD1") (class "Default")
      (node (ref "C2040") (pin "55") (pinfunction "QSPI_SD1_55") (pintype "bidirectional"))
      (node (ref "U16") (pin "2") (pinfunction "IO1_2") (pintype "bidirectional"))
    )
    (net (code "116") (name "/SAM_QSPI_SD2") (class "Default")
      (node (ref "C2040") (pin "54") (pinfunction "QSPI_SD2_54") (pintype "bidirectional"))
      (node (ref "U16") (pin "3") (pinfunction "IO2_3") (pintype "bidirectional"))
    )
    (net (code "117") (name "/SAM_QSPI_SD3") (class "Default")
      (node (ref "C2040") (pin "51") (pinfunction "QSPI_SD3_51") (pintype "bidirectional"))
      (node (ref "U16") (pin "7") (pinfunction "IO3_7") (pintype "bidirectional"))
    )
    (net (code "118") (name "/SAM_RUN") (class "Default")
      (node (ref "C2040") (pin "26") (pinfunction "RUN_26") (pintype "input"))
    )
    (net (code "119") (name "/SAM_SWCLK") (class "Default")
      (node (ref "C2040") (pin "24") (pinfunction "SWCLK_24") (pintype "input"))
    )
    (net (code "120") (name "/SAM_SWD") (class "Default")
      (node (ref "C2040") (pin "25") (pinfunction "SWD_25") (pintype "bidirectional"))
    )
    (net (code "121") (name "/SAM_USB_DM") (class "Default")
      (node (ref "C2040") (pin "46") (pinfunction "USB_DM_46") (pintype "bidirectional"))
      (node (ref "R32") (pin "2") (pinfunction "2_2") (pintype "passive"))
    )
    (net (code "122") (name "/SAM_USB_DP") (class "Default")
      (node (ref "C2040") (pin "47") (pinfunction "USB_DP_47") (pintype "bidirectional"))
      (node (ref "R31") (pin "2") (pinfunction "2_2") (pintype "passive"))
    )
    (net (code "123") (name "/SAM_USB_SWITCH") (class "Default")
      (node (ref "C2040") (pin "30") (pinfunction "GPIO19_30") (pintype "bidirectional"))
      (node (ref "R41") (pin "1") (pinfunction "1_1") (pintype "passive"))
      (node (ref "USB2.0MUX") (pin "8") (pinfunction "~{OE}_8") (pintype "input"))
    )
    (net (code "124") (name "/SAM_XIN") (class "Default")
      (node (ref "C2040") (pin "20") (pinfunction "XIN_20") (pintype "passive"))
      (node (ref "C82") (pin "1") (pinfunction "1_1") (pintype "passive"))
      (node (ref "Y1") (pin "1") (pinfunction "CRYSTAL_1_1") (pintype "bidirectional"))
    )
    (net (code "125") (name "/SAM_XOUT") (class "Default")
      (node (ref "C2040") (pin "21") (pinfunction "XOUT_21") (pintype "passive"))
      (node (ref "R35") (pin "1") (pinfunction "1_1") (pintype "passive"))
    )
    (net (code "126") (name "/SCL0") (class "Default")
      (node (ref "CAMERA") (pin "20") (pinfunction "20_20") (pintype "passive"))
      (node (ref "RPI-CM1") (pin "80") (pinfunction "SCL0_80") (pintype "passive"))
    )
    (net (code "127") (name "/SDA0") (class "Default")
      (node (ref "CAMERA") (pin "21") (pinfunction "21_21") (pintype "passive"))
      (node (ref "RPI-CM1") (pin "82") (pinfunction "SDA0_82") (pintype "passive"))
    )
    (net (code "128") (name "/SOC_EINK_BUSY") (class "Default")
      (node (ref "RPI-CM1") (pin "40") (pinfunction "GPIO9_40") (pintype "passive"))
      (node (ref "U7") (pin "17") (pinfunction "1Y1_17") (pintype "output"))
    )
    (net (code "129") (name "/SOC_EINK_CS") (class "Default")
      (node (ref "RPI-CM1") (pin "39") (pinfunction "GPIO8_39") (pintype "passive"))
      (node (ref "U7") (pin "7") (pinfunction "1A4_7") (pintype "input"))
    )
    (net (code "130") (name "/SOC_EINK_D{slash}C") (class "Default")
      (node (ref "RPI-CM1") (pin "30") (pinfunction "GPIO6_30") (pintype "passive"))
      (node (ref "U7") (pin "5") (pinfunction "1A3_5") (pintype "input"))
    )
    (net (code "131") (name "/SOC_EINK_RESET") (class "Default")
      (node (ref "RPI-CM1") (pin "28") (pinfunction "GPIO13_28") (pintype "passive"))
      (node (ref "U7") (pin "3") (pinfunction "1A2_3") (pintype "input"))
    )
    (net (code "132") (name "/SOC_SPI_CLK") (class "Default")
      (node (ref "RPI-CM1") (pin "38") (pinfunction "GPIO11_38") (pintype "passive"))
      (node (ref "U7") (pin "10") (pinfunction "2A1_10") (pintype "input"))
    )
    (net (code "133") (name "/SOC_SPI_MOSI") (class "Default")
      (node (ref "RPI-CM1") (pin "44") (pinfunction "GPIO10_44") (pintype "passive"))
      (node (ref "U7") (pin "12") (pinfunction "2A2_12") (pintype "input"))
    )
    (net (code "134") (name "/SPI_CLK") (class "Default")
      (node (ref "C2040") (pin "17") (pinfunction "GPIO14_17") (pintype "bidirectional"))
      (node (ref "EINK_524352471") (pin "12") (pinfunction "12_12") (pintype "passive"))
      (node (ref "RPIBOOT11") (pin "P$1") (pinfunction "1_P$1") (pintype "bidirectional"))
      (node (ref "U21") (pin "2") (pinfunction "I/O_2") (pintype "passive"))
      (node (ref "U7") (pin "8") (pinfunction "2Y1_8") (pintype "output"))
    )
    (net (code "135") (name "/SPI_MOSI") (class "Default")
      (node (ref "C2040") (pin "18") (pinfunction "GPIO15_18") (pintype "bidirectional"))
      (node (ref "EINK_524352471") (pin "11") (pinfunction "11_11") (pintype "passive"))
      (node (ref "GND42") (pin "P$1") (pinfunction "1_P$1") (pintype "bidirectional"))
      (node (ref "U22") (pin "2") (pinfunction "I/O_2") (pintype "passive"))
      (node (ref "U7") (pin "6") (pinfunction "2Y2_6") (pintype "output"))
    )
    (net (code "136") (name "/SYS_PI_ON") (class "Default")
      (node (ref "C2040") (pin "32") (pinfunction "GPIO21_32") (pintype "bidirectional"))
      (node (ref "Q3") (pin "1") (pinfunction "G_1") (pintype "passive"))
    )
    (net (code "137") (name "/TACH") (class "Default")
      (node (ref "J3") (pin "2") (pinfunction "2_2") (pintype "passive"))
      (node (ref "R30") (pin "1") (pinfunction "1_1") (pintype "passive"))
      (node (ref "U9") (pin "6") (pinfunction "TACH_6") (pintype "input"))
    )
    (net (code "138") (name "/TSCL") (class "Default")
      (node (ref "EINK_524352471") (pin "19") (pinfunction "19_19") (pintype "passive"))
      (node (ref "U23") (pin "2") (pinfunction "I/O_2") (pintype "passive"))
    )
    (net (code "139") (name "/TSDA") (class "Default")
      (node (ref "EINK_524352471") (pin "18") (pinfunction "18_18") (pintype "passive"))
      (node (ref "U24") (pin "2") (pinfunction "I/O_2") (pintype "passive"))
    )
    (net (code "140") (name "/U25_OUT+") (class "Default")
      (node (ref "H2") (pin "1") (pinfunction "1_1") (pintype "passive"))
      (node (ref "H2") (pin "2") (pinfunction "2_2") (pintype "passive"))
      (node (ref "U25") (pin "7") (pinfunction "OUT+_7") (pintype "output"))
    )
    (net (code "141") (name "/U25_OUT-") (class "Default")
      (node (ref "H2") (pin "3") (pinfunction "3_3") (pintype "passive"))
      (node (ref "H2") (pin "4") (pinfunction "4_4") (pintype "passive"))
      (node (ref "U25") (pin "9") (pinfunction "OUT-_9") (pintype "output"))
    )
    (net (code "142") (name "/UART_RXD0") (class "Default")
      (node (ref "J5") (pin "2") (pinfunction "2_2") (pintype "passive"))
      (node (ref "RPI-CM1") (pin "51") (pinfunction "GPIO15_51") (pintype "passive"))
    )
    (net (code "143") (name "/UART_TXD0") (class "Default")
      (node (ref "J5") (pin "1") (pinfunction "1_1") (pintype "passive"))
      (node (ref "RPI-CM1") (pin "55") (pinfunction "GPIO14_55") (pintype "passive"))
    )
    (net (code "144") (name "/USB_OTG_ID") (class "Default")
      (node (ref "RPI-CM1") (pin "101") (pinfunction "USB_OTG_ID_101") (pintype "passive"))
    )
    (net (code "145") (name "/VCOM") (class "Default")
      (node (ref "C15") (pin "1") (pinfunction "1_1") (pintype "passive"))
      (node (ref "EINK_524352471") (pin "1") (pinfunction "1_1") (pintype "passive"))
    )
    (net (code "146") (name "/VDAC_COMP") (class "Default")
      (node (ref "RPI-CM1") (pin "111") (pinfunction "VDAC_COMP_111") (pintype "passive"))
    )
    (net (code "147") (name "/VGH") (class "Default")
      (node (ref "C8") (pin "1") (pinfunction "1_1") (pintype "passive"))
      (node (ref "EINK_524352471") (pin "20") (pinfunction "20_20") (pintype "passive"))
    )
    (net (code "148") (name "/VGL") (class "Default")
      (node (ref "C5") (pin "1") (pinfunction "1_1") (pintype "passive"))
      (node (ref "EINK_524352471") (pin "21") (pinfunction "21_21") (pintype "passive"))
    )
    (net (code "149") (name "/VMID") (class "Default")
      (node (ref "C45") (pin "1") (pinfunction "1_1") (pintype "passive"))
      (node (ref "C47") (pin "1") (pinfunction "1_1") (pintype "passive"))
      (node (ref "IC3") (pin "27") (pinfunction "VMID_27") (pintype "input"))
    )
    (net (code "150") (name "/VPP") (class "Default")
      (node (ref "C11") (pin "1") (pinfunction "1_1") (pintype "passive"))
      (node (ref "EINK_524352471") (pin "6") (pinfunction "6_6") (pintype "passive"))
    )
    (net (code "151") (name "/VSH") (class "Default")
      (node (ref "C12") (pin "1") (pinfunction "1_1") (pintype "passive"))
      (node (ref "EINK_524352471") (pin "5") (pinfunction "5_5") (pintype "passive"))
    )
    (net (code "152") (name "/VSL") (class "Default")
      (node (ref "C13") (pin "1") (pinfunction "1_1") (pintype "passive"))
      (node (ref "EINK_524352471") (pin "3") (pinfunction "3_3") (pintype "passive"))
    )
    (net (code "153") (name "/~{CE}") (class "Default")
      (node (ref "R24") (pin "1") (pinfunction "1_1") (pintype "passive"))
      (node (ref "U4") (pin "4") (pinfunction "~{CE}_4") (pintype "bidirectional"))
    )
    (net (code "154") (name "3.3V") (class "Default")
      (node (ref "C28") (pin "1") (pinfunction "1_1") (pintype "passive"))
      (node (ref "C36") (pin "2") (pinfunction "2_2") (pintype "passive"))
      (node (ref "C49") (pin "1") (pinfunction "1_1") (pintype "passive"))
      (node (ref "CAMERA") (pin "22") (pinfunction "22_22") (pintype "passive"))
      (node (ref "D1") (pin "A") (pinfunction "A_A") (pintype "passive"))
      (node (ref "IC1") (pin "5") (pinfunction "VDD_5") (pintype "power_in"))
      (node (ref "IC1") (pin "6") (pinfunction "VDDIO_6") (pintype "power_in"))
      (node (ref "IC3") (pin "10") (pinfunction "DBVDD_10") (pintype "power_in"))
      (node (ref "IC3") (pin "8") (pinfunction "DCVDD_8") (pintype "power_in"))
      (node (ref "OSC2") (pin "1") (pinfunction "INH_1") (pintype "bidirectional"))
      (node (ref "OSC2") (pin "4") (pinfunction "VCC_4") (pintype "power_in"))
      (node (ref "R15") (pin "2") (pinfunction "2_2") (pintype "passive"))
      (node (ref "R18") (pin "2") (pinfunction "2_2") (pintype "passive"))
      (node (ref "R30") (pin "2") (pinfunction "2_2") (pintype "passive"))
      (node (ref "R33") (pin "2") (pinfunction "2_2") (pintype "passive"))
      (node (ref "RPI-CM1") (pin "84") (pinfunction "CM4_3.3V(OUTPUT)_84") (pintype "passive"))
      (node (ref "RPI-CM1") (pin "86") (pinfunction "CM4_3.3V(OUTPUT)_86") (pintype "passive"))
      (node (ref "RPIBOOT2") (pin "P$1") (pinfunction "1_P$1") (pintype "bidirectional"))
      (node (ref "SJ6") (pin "1") (pinfunction "1_1") (pintype "passive"))
      (node (ref "U2") (pin "5") (pinfunction "VCC_5") (pintype "power_in"))
      (node (ref "U6") (pin "5") (pinfunction "VDDIO_5") (pintype "power_in"))
      (node (ref "U6") (pin "8") (pinfunction "VDD_8") (pintype "power_in"))
      (node (ref "U9") (pin "3") (pinfunction "VDD_3") (pintype "power_in"))
    )
    (net (code "155") (name "3V3_EINK") (class "Default")
      (node (ref "C17") (pin "1") (pinfunction "1_1") (pintype "passive"))
      (node (ref "C9") (pin "1") (pinfunction "1_1") (pintype "passive"))
      (node (ref "EINK_524352471") (pin "10") (pinfunction "10_10") (pintype "passive"))
      (node (ref "EINK_524352471") (pin "9") (pinfunction "9_9") (pintype "passive"))
      (node (ref "L3") (pin "1") (pinfunction "1_1") (pintype "passive"))
      (node (ref "Q2") (pin "3") (pinfunction "D_3") (pintype "passive"))
    )
    (net (code "156") (name "5.0V") (class "Default")
      (node (ref "C2") (pin "1") (pinfunction "1_1") (pintype "passive"))
      (node (ref "C25") (pin "1") (pinfunction "1_1") (pintype "passive"))
      (node (ref "C42") (pin "1") (pinfunction "1_1") (pintype "passive"))
      (node (ref "C59") (pin "1") (pinfunction "1_1") (pintype "passive"))
      (node (ref "C6") (pin "1") (pinfunction "1_1") (pintype "passive"))
      (node (ref "C60") (pin "1") (pinfunction "1_1") (pintype "passive"))
      (node (ref "C61") (pin "1") (pinfunction "1_1") (pintype "passive"))
      (node (ref "C65") (pin "1") (pinfunction "1_1") (pintype "passive"))
      (node (ref "C66") (pin "1") (pinfunction "1_1") (pintype "passive"))
      (node (ref "IC3") (pin "21") (pinfunction "SPKVDD2_21") (pintype "power_in"))
      (node (ref "IC3") (pin "26") (pinfunction "SPKVDD1_26") (pintype "power_in"))
      (node (ref "J3") (pin "3") (pinfunction "3_3") (pintype "passive"))
      (node (ref "R3") (pin "2") (pinfunction "2_2") (pintype "passive"))
      (node (ref "R5") (pin "1") (pinfunction "1_1") (pintype "passive"))
      (node (ref "RPI-CM1") (pin "77") (pinfunction "+5V(INPUT)_77") (pintype "passive"))
      (node (ref "RPI-CM1") (pin "79") (pinfunction "+5V(INPUT)_79") (pintype "passive"))
      (node (ref "RPI-CM1") (pin "81") (pinfunction "+5V(INPUT)_81") (pintype "passive"))
      (node (ref "RPI-CM1") (pin "83") (pinfunction "+5V(INPUT)_83") (pintype "passive"))
      (node (ref "RPI-CM1") (pin "85") (pinfunction "+5V(INPUT)_85") (pintype "passive"))
      (node (ref "RPI-CM1") (pin "87") (pinfunction "+5V(INPUT)_87") (pintype "passive"))
      (node (ref "RPIBOOT1") (pin "P$1") (pinfunction "1_P$1") (pintype "bidirectional"))
      (node (ref "U1") (pin "1") (pinfunction "VOUT_1") (pintype "power_in"))
      (node (ref "U1") (pin "15") (pinfunction "VOUT_15") (pintype "power_in"))
      (node (ref "U1") (pin "16") (pinfunction "VOUT_16") (pintype "power_in"))
      (node (ref "U10") (pin "1") (pinfunction "IN_1") (pintype "power_in"))
      (node (ref "U10") (pin "3") (pinfunction "EN_3") (pintype "input"))
    )
    (net (code "157") (name "AGND") (class "Default")
      (node (ref "C67") (pin "2") (pinfunction "2_2") (pintype "passive"))
      (node (ref "C68") (pin "2") (pinfunction "2_2") (pintype "passive"))
      (node (ref "FB5") (pin "2") (pinfunction "2_2") (pintype "passive"))
      (node (ref "IC3") (pin "28") (pinfunction "AGND_28") (pintype "power_in"))
      (node (ref "IC3") (pin "33") (pinfunction "AGND_33") (pintype "power_in"))
    )
    (net (code "158") (name "AVDD") (class "Default")
      (node (ref "C50") (pin "1") (pinfunction "1_1") (pintype "passive"))
      (node (ref "C58") (pin "1") (pinfunction "1_1") (pintype "passive"))
      (node (ref "C67") (pin "1") (pinfunction "1_1") (pintype "passive"))
      (node (ref "C68") (pin "1") (pinfunction "1_1") (pintype "passive"))
      (node (ref "FB1") (pin "2") (pinfunction "2_2") (pintype "passive"))
      (node (ref "IC3") (pin "32") (pinfunction "AVDD_32") (pintype "power_in"))
      (node (ref "R27") (pin "2") (pinfunction "2_2") (pintype "passive"))
      (node (ref "U12") (pin "4") (pinfunction "VDD_4") (pintype "power_in"))
      (node (ref "U14") (pin "5") (pinfunction "P$V+_5") (pintype "bidirectional"))
    )
    (net (code "159") (name "BATTERY_IN") (class "Default")
      (node (ref "C19") (pin "1") (pinfunction "1_1") (pintype "passive"))
      (node (ref "J1") (pin "3") (pinfunction "3_3") (pintype "passive"))
      (node (ref "R12") (pin "2") (pinfunction "2_2") (pintype "passive"))
      (node (ref "U3") (pin "6") (pinfunction "BAT_6") (pintype "bidirectional"))
      (node (ref "U3") (pin "8") (pinfunction "SRP_8") (pintype "bidirectional"))
    )
    (net (code "160") (name "BOOST_EN") (class "Default")
      (node (ref "Q3") (pin "3") (pinfunction "D_3") (pintype "passive"))
      (node (ref "R13") (pin "1") (pinfunction "1_1") (pintype "passive"))
      (node (ref "R36") (pin "2") (pinfunction "2_2") (pintype "passive"))
    )
    (net (code "161") (name "EXT_VCC_PCIE") (class "Default")
      (node (ref "M.2KEYM(NGFF)") (pin "12") (pinfunction "P12_12") (pintype "passive"))
      (node (ref "M.2KEYM(NGFF)") (pin "14") (pinfunction "P14_14") (pintype "passive"))
      (node (ref "M.2KEYM(NGFF)") (pin "16") (pinfunction "P16_16") (pintype "passive"))
      (node (ref "M.2KEYM(NGFF)") (pin "18") (pinfunction "P18_18") (pintype "passive"))
      (node (ref "M.2KEYM(NGFF)") (pin "2") (pinfunction "P2_2") (pintype "passive"))
      (node (ref "M.2KEYM(NGFF)") (pin "4") (pinfunction "P4_4") (pintype "passive"))
      (node (ref "M.2KEYM(NGFF)") (pin "70") (pinfunction "P70_70") (pintype "passive"))
      (node (ref "M.2KEYM(NGFF)") (pin "72") (pinfunction "P72_72") (pintype "passive"))
      (node (ref "M.2KEYM(NGFF)") (pin "74") (pinfunction "P74_74") (pintype "passive"))
      (node (ref "RPIBOOT3") (pin "P$1") (pinfunction "1_P$1") (pintype "bidirectional"))
    )
    (net (code "162") (name "GND") (class "Default")
      (node (ref "C1") (pin "2") (pinfunction "2_2") (pintype "passive"))
      (node (ref "C10") (pin "2") (pinfunction "2_2") (pintype "passive"))
      (node (ref "C11") (pin "2") (pinfunction "2_2") (pintype "passive"))
      (node (ref "C12") (pin "2") (pinfunction "2_2") (pintype "passive"))
      (node (ref "C13") (pin "2") (pinfunction "2_2") (pintype "passive"))
      (node (ref "C14") (pin "2") (pinfunction "2_2") (pintype "passive"))
      (node (ref "C15") (pin "2") (pinfunction "2_2") (pintype "passive"))
      (node (ref "C16") (pin "2") (pinfunction "2_2") (pintype "passive"))
      (node (ref "C17") (pin "2") (pinfunction "2_2") (pintype "passive"))
      (node (ref "C19") (pin "2") (pinfunction "2_2") (pintype "passive"))
      (node (ref "C2") (pin "2") (pinfunction "2_2") (pintype "passive"))
      (node (ref "C20") (pin "2") (pinfunction "2_2") (pintype "passive"))
      (node (ref "C2040") (pin "19") (pinfunction "TESTEN_19") (pintype "input"))
      (node (ref "C2040") (pin "57") (pinfunction "GND_57") (pintype "passive"))
      (node (ref "C21") (pin "2") (pinfunction "2_2") (pintype "passive"))
      (node (ref "C22") (pin "2") (pinfunction "2_2") (pintype "passive"))
      (node (ref "C23") (pin "2") (pinfunction "2_2") (pintype "passive"))
      (node (ref "C24") (pin "1") (pinfunction "1_1") (pintype "passive"))
      (node (ref "C25") (pin "2") (pinfunction "2_2") (pintype "passive"))
      (node (ref "C26") (pin "2") (pinfunction "2_2") (pintype "passive"))
      (node (ref "C28") (pin "2") (pinfunction "2_2") (pintype "passive"))
      (node (ref "C3") (pin "2") (pinfunction "2_2") (pintype "passive"))
      (node (ref "C30") (pin "2") (pinfunction "2_2") (pintype "passive"))
      (node (ref "C31") (pin "2") (pinfunction "2_2") (pintype "passive"))
      (node (ref "C32") (pin "2") (pinfunction "2_2") (pintype "passive"))
      (node (ref "C33") (pin "2") (pinfunction "2_2") (pintype "passive"))
      (node (ref "C34") (pin "1") (pinfunction "1_1") (pintype "passive"))
      (node (ref "C35") (pin "2") (pinfunction "2_2") (pintype "passive"))
      (node (ref "C36") (pin "1") (pinfunction "1_1") (pintype "passive"))
      (node (ref "C4") (pin "2") (pinfunction "2_2") (pintype "passive"))
      (node (ref "C40") (pin "2") (pinfunction "2_2") (pintype "passive"))
      (node (ref "C42") (pin "2") (pinfunction "2_2") (pintype "passive"))
      (node (ref "C43") (pin "2") (pinfunction "2_2") (pintype "passive"))
      (node (ref "C44") (pin "2") (pinfunction "2_2") (pintype "passive"))
      (node (ref "C45") (pin "2") (pinfunction "2_2") (pintype "passive"))
      (node (ref "C46") (pin "2") (pinfunction "2_2") (pintype "passive"))
      (node (ref "C47") (pin "2") (pinfunction "2_2") (pintype "passive"))
      (node (ref "C48") (pin "2") (pinfunction "2_2") (pintype "passive"))
      (node (ref "C49") (pin "2") (pinfunction "2_2") (pintype "passive"))
      (node (ref "C5") (pin "2") (pinfunction "2_2") (pintype "passive"))
      (node (ref "C50") (pin "2") (pinfunction "2_2") (pintype "passive"))
      (node (ref "C53") (pin "2") (pinfunction "2_2") (pintype "passive"))
      (node (ref "C58") (pin "2") (pinfunction "2_2") (pintype "passive"))
      (node (ref "C59") (pin "2") (pinfunction "2_2") (pintype "passive"))
      (node (ref "C6") (pin "2") (pinfunction "2_2") (pintype "passive"))
      (node (ref "C60") (pin "2") (pinfunction "2_2") (pintype "passive"))
      (node (ref "C61") (pin "2") (pinfunction "2_2") (pintype "passive"))
      (node (ref "C62") (pin "2") (pinfunction "2_2") (pintype "passive"))
      (node (ref "C63") (pin "2") (pinfunction "2_2") (pintype "passive"))
      (node (ref "C64") (pin "2") (pinfunction "2_2") (pintype "passive"))
      (node (ref "C65") (pin "2") (pinfunction "2_2") (pintype "passive"))
      (node (ref "C66") (pin "2") (pinfunction "2_2") (pintype "passive"))
      (node (ref "C69") (pin "2") (pinfunction "2_2") (pintype "passive"))
      (node (ref "C7") (pin "2") (pinfunction "2_2") (pintype "passive"))
      (node (ref "C71") (pin "2") (pinfunction "2_2") (pintype "passive"))
      (node (ref "C72") (pin "2") (pinfunction "2_2") (pintype "passive"))
      (node (ref "C73") (pin "2") (pinfunction "2_2") (pintype "passive"))
      (node (ref "C74") (pin "2") (pinfunction "2_2") (pintype "passive"))
      (node (ref "C75") (pin "2") (pinfunction "2_2") (pintype "passive"))
      (node (ref "C76") (pin "2") (pinfunction "2_2") (pintype "passive"))
      (node (ref "C77") (pin "2") (pinfunction "2_2") (pintype "passive"))
      (node (ref "C79") (pin "2") (pinfunction "2_2") (pintype "passive"))
      (node (ref "C8") (pin "2") (pinfunction "2_2") (pintype "passive"))
      (node (ref "C80") (pin "2") (pinfunction "2_2") (pintype "passive"))
      (node (ref "C82") (pin "2") (pinfunction "2_2") (pintype "passive"))
      (node (ref "C83") (pin "1") (pinfunction "1_1") (pintype "passive"))
      (node (ref "C9") (pin "2") (pinfunction "2_2") (pintype "passive"))
      (node (ref "CAMERA") (pin "1") (pinfunction "1_1") (pintype "passive"))
      (node (ref "CAMERA") (pin "10") (pinfunction "10_10") (pintype "passive"))
      (node (ref "CAMERA") (pin "13") (pinfunction "13_13") (pintype "passive"))
      (node (ref "CAMERA") (pin "16") (pinfunction "16_16") (pintype "passive"))
      (node (ref "CAMERA") (pin "19") (pinfunction "19_19") (pintype "passive"))
      (node (ref "CAMERA") (pin "4") (pinfunction "4_4") (pintype "passive"))
      (node (ref "CAMERA") (pin "7") (pinfunction "7_7") (pintype "passive"))
      (node (ref "CAMERA") (pin "P1") (pinfunction "P1_P1") (pintype "passive"))
      (node (ref "CAMERA") (pin "P2") (pinfunction "P2_P2") (pintype "passive"))
      (node (ref "D2") (pin "1") (pinfunction "K_1") (pintype "bidirectional"))
      (node (ref "EINK_524352471") (pin "17") (pinfunction "17_17") (pintype "passive"))
      (node (ref "EINK_524352471") (pin "8") (pinfunction "8_8") (pintype "passive"))
      (node (ref "EINK_524352471") (pin "P1") (pinfunction "P1_P1") (pintype "passive"))
      (node (ref "EINK_524352471") (pin "P2") (pinfunction "P2_P2") (pintype "passive"))
      (node (ref "FB5") (pin "1") (pinfunction "1_1") (pintype "passive"))
      (node (ref "GND") (pin "P$1") (pinfunction "1_P$1") (pintype "bidirectional"))
      (node (ref "GND13") (pin "P$1") (pinfunction "1_P$1") (pintype "bidirectional"))
      (node (ref "GND22") (pin "P$1") (pinfunction "1_P$1") (pintype "bidirectional"))
      (node (ref "GND26") (pin "P$1") (pinfunction "1_P$1") (pintype "bidirectional"))
      (node (ref "GND27") (pin "P$1") (pinfunction "1_P$1") (pintype "bidirectional"))
      (node (ref "GND34") (pin "P$1") (pinfunction "1_P$1") (pintype "bidirectional"))
      (node (ref "IC1") (pin "12") (pinfunction "GND_12") (pintype "power_in"))
      (node (ref "IC1") (pin "2") (pinfunction "GND_2") (pintype "power_in"))
      (node (ref "IC1") (pin "3") (pinfunction "GND_3") (pintype "power_in"))
      (node (ref "IC1") (pin "9") (pinfunction "SDO_9") (pintype "bidirectional"))
      (node (ref "IC3") (pin "20") (pinfunction "SPKGND2_20") (pintype "power_in"))
      (node (ref "IC3") (pin "24") (pinfunction "SPKGND1_24") (pintype "power_in"))
      (node (ref "IC3") (pin "9") (pinfunction "DGND_9") (pintype "power_in"))
      (node (ref "J1") (pin "1") (pinfunction "1_1") (pintype "passive"))
      (node (ref "J2") (pin "GND") (pinfunction "GND_GND") (pintype "bidirectional"))
      (node (ref "J2") (pin "GND2") (pinfunction "GND_GND2") (pintype "bidirectional"))
      (node (ref "J2") (pin "SHLD1") (pinfunction "SHLD_SHLD1") (pintype "bidirectional"))
      (node (ref "J2") (pin "SHLD2") (pinfunction "SHLD_SHLD2") (pintype "bidirectional"))
      (node (ref "J2") (pin "SHLD3") (pinfunction "SHLD_SHLD3") (pintype "bidirectional"))
      (node (ref "J2") (pin "SHLD4") (pinfunction "SHLD_SHLD4") (pintype "bidirectional"))
      (node (ref "J2") (pin "SHLD5") (pinfunction "SHLD_SHLD5") (pintype "bidirectional"))
      (node (ref "J2") (pin "SHLD6") (pinfunction "SHLD_SHLD6") (pintype "bidirectional"))
      (node (ref "J2") (pin "SHLD7") (pinfunction "SHLD_SHLD7") (pintype "bidirectional"))
      (node (ref "J2") (pin "SHLD8") (pinfunction "SHLD_SHLD8") (pintype "bidirectional"))
      (node (ref "J3") (pin "4") (pinfunction "4_4") (pintype "passive"))
      (node (ref "J4") (pin "4") (pinfunction "4_4") (pintype "passive"))
      (node (ref "J5") (pin "3") (pinfunction "3_3") (pintype "passive"))
      (node (ref "J5") (pin "4") (pinfunction "4_4") (pintype "passive"))
      (node (ref "LED2") (pin "C") (pinfunction "C_C") (pintype "passive"))
      (node (ref "LED3") (pin "C") (pinfunction "C_C") (pintype "passive"))
      (node (ref "LOW_BATT") (pin "C") (pinfunction "C_C") (pintype "passive"))
      (node (ref "M.2KEYM(NGFF)") (pin "1") (pinfunction "P1_1") (pintype "passive"))
      (node (ref "M.2KEYM(NGFF)") (pin "15") (pinfunction "P15_15") (pintype "passive"))
      (node (ref "M.2KEYM(NGFF)") (pin "21") (pinfunction "P21_21") (pintype "passive"))
      (node (ref "M.2KEYM(NGFF)") (pin "27") (pinfunction "P27_27") (pintype "passive"))
      (node (ref "M.2KEYM(NGFF)") (pin "3") (pinfunction "P3_3") (pintype "passive"))
      (node (ref "M.2KEYM(NGFF)") (pin "33") (pinfunction "P33_33") (pintype "passive"))
      (node (ref "M.2KEYM(NGFF)") (pin "39") (pinfunction "P39_39") (pintype "passive"))
      (node (ref "M.2KEYM(NGFF)") (pin "45") (pinfunction "P45_45") (pintype "passive"))
      (node (ref "M.2KEYM(NGFF)") (pin "51") (pinfunction "P51_51") (pintype "passive"))
      (node (ref "M.2KEYM(NGFF)") (pin "57") (pinfunction "P57_57") (pintype "passive"))
      (node (ref "M.2KEYM(NGFF)") (pin "71") (pinfunction "P71_71") (pintype "passive"))
      (node (ref "M.2KEYM(NGFF)") (pin "73") (pinfunction "P73_73") (pintype "passive"))
      (node (ref "M.2KEYM(NGFF)") (pin "75") (pinfunction "P75_75") (pintype "passive"))
      (node (ref "M.2KEYM(NGFF)") (pin "9") (pinfunction "P9_9") (pintype "passive"))
      (node (ref "M.2KEYM(NGFF)") (pin "SH1") (pinfunction "SHIELD_SH1") (pintype "passive"))
      (node (ref "M.2KEYM(NGFF)") (pin "SH2") (pinfunction "SHIELD_SH2") (pintype "passive"))
      (node (ref "OSC2") (pin "2") (pinfunction "GND_2") (pintype "power_in"))
      (node (ref "Q3") (pin "2") (pinfunction "S_2") (pintype "passive"))
      (node (ref "Q4") (pin "2") (pinfunction "S_2") (pintype "passive"))
      (node (ref "R11") (pin "1") (pinfunction "1_1") (pintype "passive"))
      (node (ref "R14") (pin "2") (pinfunction "2_2") (pintype "passive"))
      (node (ref "R16") (pin "1") (pinfunction "1_1") (pintype "passive"))
      (node (ref "R17") (pin "1") (pinfunction "1_1") (pintype "passive"))
      (node (ref "R19") (pin "1") (pinfunction "1_1") (pintype "passive"))
      (node (ref "R2") (pin "1") (pinfunction "1_1") (pintype "passive"))
      (node (ref "R21") (pin "1") (pinfunction "1_1") (pintype "passive"))
      (node (ref "R23") (pin "2") (pinfunction "2_2") (pintype "passive"))
      (node (ref "R24") (pin "2") (pinfunction "2_2") (pintype "passive"))
      (node (ref "R28") (pin "1") (pinfunction "1_1") (pintype "passive"))
      (node (ref "R37") (pin "1") (pinfunction "1_1") (pintype "passive"))
      (node (ref "R4") (pin "1") (pinfunction "1_1") (pintype "passive"))
      (node (ref "R41") (pin "2") (pinfunction "2_2") (pintype "passive"))
      (node (ref "R6") (pin "2") (pinfunction "2_2") (pintype "passive"))
      (node (ref "R7") (pin "2") (pinfunction "2_2") (pintype "passive"))
      (node (ref "R9") (pin "1") (pinfunction "1_1") (pintype "passive"))
      (node (ref "RPI-CM1") (pin "1") (pinfunction "GND_1") (pintype "passive"))
      (node (ref "RPI-CM1") (pin "107") (pinfunction "GND_107") (pintype "passive"))
      (node (ref "RPI-CM1") (pin "108") (pinfunction "GND_108") (pintype "passive"))
      (node (ref "RPI-CM1") (pin "113") (pinfunction "GND_113") (pintype "passive"))
      (node (ref "RPI-CM1") (pin "114") (pinfunction "GND_114") (pintype "passive"))
      (node (ref "RPI-CM1") (pin "119") (pinfunction "GND_119") (pintype "passive"))
      (node (ref "RPI-CM1") (pin "120") (pinfunction "GND_120") (pintype "passive"))
      (node (ref "RPI-CM1") (pin "125") (pinfunction "GND_125") (pintype "passive"))
      (node (ref "RPI-CM1") (pin "126") (pinfunction "GND_126") (pintype "passive"))
      (node (ref "RPI-CM1") (pin "13") (pinfunction "GND_13") (pintype "passive"))
      (node (ref "RPI-CM1") (pin "131") (pinfunction "GND_131") (pintype "passive"))
      (node (ref "RPI-CM1") (pin "132") (pinfunction "GND_132") (pintype "passive"))
      (node (ref "RPI-CM1") (pin "137") (pinfunction "GND_137") (pintype "passive"))
      (node (ref "RPI-CM1") (pin "138") (pinfunction "GND_138") (pintype "passive"))
      (node (ref "RPI-CM1") (pin "14") (pinfunction "GND_14") (pintype "passive"))
      (node (ref "RPI-CM1") (pin "144") (pinfunction "GND_144") (pintype "passive"))
      (node (ref "RPI-CM1") (pin "150") (pinfunction "GND_150") (pintype "passive"))
      (node (ref "RPI-CM1") (pin "155") (pinfunction "GND_155") (pintype "passive"))
      (node (ref "RPI-CM1") (pin "156") (pinfunction "GND_156") (pintype "passive"))
      (node (ref "RPI-CM1") (pin "161") (pinfunction "GND_161") (pintype "passive"))
      (node (ref "RPI-CM1") (pin "162") (pinfunction "GND_162") (pintype "passive"))
      (node (ref "RPI-CM1") (pin "167") (pinfunction "GND_167") (pintype "passive"))
      (node (ref "RPI-CM1") (pin "168") (pinfunction "GND_168") (pintype "passive"))
      (node (ref "RPI-CM1") (pin "173") (pinfunction "GND_173") (pintype "passive"))
      (node (ref "RPI-CM1") (pin "174") (pinfunction "GND_174") (pintype "passive"))
      (node (ref "RPI-CM1") (pin "179") (pinfunction "GND_179") (pintype "passive"))
      (node (ref "RPI-CM1") (pin "180") (pinfunction "GND_180") (pintype "passive"))
      (node (ref "RPI-CM1") (pin "185") (pinfunction "GND_185") (pintype "passive"))
      (node (ref "RPI-CM1") (pin "186") (pinfunction "GND_186") (pintype "passive"))
      (node (ref "RPI-CM1") (pin "191") (pinfunction "GND_191") (pintype "passive"))
      (node (ref "RPI-CM1") (pin "192") (pinfunction "GND_192") (pintype "passive"))
      (node (ref "RPI-CM1") (pin "197") (pinfunction "GND_197") (pintype "passive"))
      (node (ref "RPI-CM1") (pin "198") (pinfunction "GND_198") (pintype "passive"))
      (node (ref "RPI-CM1") (pin "2") (pinfunction "GND_2") (pintype "passive"))
      (node (ref "RPI-CM1") (pin "22") (pinfunction "GND_22") (pintype "passive"))
      (node (ref "RPI-CM1") (pin "23") (pinfunction "GND_23") (pintype "passive"))
      (node (ref "RPI-CM1") (pin "32") (pinfunction "GND_32") (pintype "passive"))
      (node (ref "RPI-CM1") (pin "33") (pinfunction "GND_33") (pintype "passive"))
      (node (ref "RPI-CM1") (pin "42") (pinfunction "GND_42") (pintype "passive"))
      (node (ref "RPI-CM1") (pin "43") (pinfunction "GND_43") (pintype "passive"))
      (node (ref "RPI-CM1") (pin "52") (pinfunction "GND_52") (pintype "passive"))
      (node (ref "RPI-CM1") (pin "53") (pinfunction "GND_53") (pintype "passive"))
      (node (ref "RPI-CM1") (pin "59") (pinfunction "GND_59") (pintype "passive"))
      (node (ref "RPI-CM1") (pin "60") (pinfunction "GND_60") (pintype "passive"))
      (node (ref "RPI-CM1") (pin "65") (pinfunction "GND_65") (pintype "passive"))
      (node (ref "RPI-CM1") (pin "66") (pinfunction "GND_66") (pintype "passive"))
      (node (ref "RPI-CM1") (pin "7") (pinfunction "GND_7") (pintype "passive"))
      (node (ref "RPI-CM1") (pin "71") (pinfunction "GND_71") (pintype "passive"))
      (node (ref "RPI-CM1") (pin "74") (pinfunction "GND_74") (pintype "passive"))
      (node (ref "RPI-CM1") (pin "8") (pinfunction "GND_8") (pintype "passive"))
      (node (ref "RPI-CM1") (pin "98") (pinfunction "GND_98") (pintype "passive"))
      (node (ref "U1") (pin "10") (pinfunction "SYNC_10") (pintype "input"))
      (node (ref "U1") (pin "13") (pinfunction "GND_13") (pintype "power_in"))
      (node (ref "U1") (pin "5") (pinfunction "PGND_5") (pintype "power_in"))
      (node (ref "U1") (pin "6") (pinfunction "PGND_6") (pintype "power_in"))
      (node (ref "U1") (pin "7") (pinfunction "PGND_7") (pintype "power_in"))
      (node (ref "U1") (pin "P$18") (pinfunction "PGND_P$18") (pintype "power_in"))
      (node (ref "U1") (pin "P$19") (pinfunction "PGND_P$19") (pintype "power_in"))
      (node (ref "U1") (pin "P$20") (pinfunction "PGND_P$20") (pintype "power_in"))
      (node (ref "U1") (pin "P$21") (pinfunction "PGND_P$21") (pintype "power_in"))
      (node (ref "U1") (pin "P$22") (pinfunction "PGND_P$22") (pintype "power_in"))
      (node (ref "U1") (pin "THERMAL") (pinfunction "PGND_THERMAL") (pintype "power_in"))
      (node (ref "U10") (pin "2") (pinfunction "GND_2") (pintype "power_in"))
      (node (ref "U11") (pin "2") (pinfunction "GND_2") (pintype "power_in"))
      (node (ref "U12") (pin "2") (pinfunction "GND_2") (pintype "power_in"))
      (node (ref "U12") (pin "3") (pinfunction "GND_3") (pintype "power_in"))
      (node (ref "U12") (pin "5") (pinfunction "GND_5") (pintype "power_in"))
      (node (ref "U12") (pin "6") (pinfunction "GND_6") (pintype "power_in"))
      (node (ref "U13") (pin "8") (pinfunction "GND_8") (pintype "power_in"))
      (node (ref "U14") (pin "2") (pinfunction "P$V-_2") (pintype "bidirectional"))
      (node (ref "U15") (pin "2") (pinfunction "GND_2") (pintype "power_in"))
      (node (ref "U16") (pin "4") (pinfunction "GND_4") (pintype "power_in"))
      (node (ref "U17") (pin "1") (pinfunction "I/O_2_1") (pintype "passive"))
      (node (ref "U18") (pin "1") (pinfunction "I/O_2_1") (pintype "passive"))
      (node (ref "U19") (pin "1") (pinfunction "I/O_2_1") (pintype "passive"))
      (node (ref "U2") (pin "3") (pinfunction "GND_3") (pintype "passive"))
      (node (ref "U20") (pin "1") (pinfunction "I/O_2_1") (pintype "passive"))
      (node (ref "U21") (pin "1") (pinfunction "I/O_2_1") (pintype "passive"))
      (node (ref "U22") (pin "1") (pinfunction "I/O_2_1") (pintype "passive"))
      (node (ref "U23") (pin "1") (pinfunction "I/O_2_1") (pintype "passive"))
      (node (ref "U24") (pin "1") (pinfunction "I/O_2_1") (pintype "passive"))
      (node (ref "U25") (pin "4") (pinfunction "IN/TRIG_4") (pintype "input"))
      (node (ref "U25") (pin "8") (pinfunction "GND_8") (pintype "power_in"))
      (node (ref "U3") (pin "3") (pinfunction "VSS_3") (pintype "bidirectional"))
      (node (ref "U3") (pin "EP") (pinfunction "PWPD_EP") (pintype "bidirectional"))
      (node (ref "U3") (pin "EP1") (pinfunction "PWPD_EP1") (pintype "bidirectional"))
      (node (ref "U3") (pin "EP2") (pinfunction "PWPD_EP2") (pintype "bidirectional"))
      (node (ref "U3") (pin "EP3") (pinfunction "PWPD_EP3") (pintype "bidirectional"))
      (node (ref "U3") (pin "EP4") (pinfunction "PWPD_EP4") (pintype "bidirectional"))
      (node (ref "U4") (pin "14") (pinfunction "TMR_14") (pintype "bidirectional"))
      (node (ref "U4") (pin "15") (pinfunction "SYSOFF_15") (pintype "bidirectional"))
      (node (ref "U4") (pin "6") (pinfunction "EN1_6") (pintype "bidirectional"))
      (node (ref "U4") (pin "8") (pinfunction "VSS_8") (pintype "bidirectional"))
      (node (ref "U4") (pin "EP") (pinfunction "EP_EP") (pintype "bidirectional"))
      (node (ref "U5") (pin "3") (pinfunction "GND_3") (pintype "passive"))
      (node (ref "U6") (pin "1") (pinfunction "SDO_1") (pintype "bidirectional"))
      (node (ref "U6") (pin "6") (pinfunction "GND_6") (pintype "power_in"))
      (node (ref "U6") (pin "7") (pinfunction "GND_7") (pintype "power_in"))
      (node (ref "U7") (pin "21") (pinfunction "PAD_21") (pintype "power_in"))
      (node (ref "U7") (pin "9") (pinfunction "GND_9") (pintype "power_in"))
      (node (ref "U9") (pin "4") (pinfunction "GND_4") (pintype "power_in"))
      (node (ref "USB2.0MUX") (pin "10") (pinfunction "S_10") (pintype "input"))
      (node (ref "USB2.0MUX") (pin "4") (pinfunction "GND_4") (pintype "passive"))
      (node (ref "Y1") (pin "2") (pinfunction "GND_1_2") (pintype "bidirectional"))
      (node (ref "Y1") (pin "4") (pinfunction "GND_2_4") (pintype "bidirectional"))
    )
    (net (code "163") (name "GPOUT") (class "Default")
      (node (ref "R33") (pin "1") (pinfunction "1_1") (pintype "passive"))
      (node (ref "U3") (pin "12") (pinfunction "GPOUT_12") (pintype "bidirectional"))
    )
    (net (code "164") (name "HAP_3V3") (class "Default")
      (node (ref "C33") (pin "1") (pinfunction "1_1") (pintype "passive"))
      (node (ref "C35") (pin "1") (pinfunction "1_1") (pintype "passive"))
      (node (ref "U15") (pin "5") (pinfunction "OUT_5") (pintype "power_in"))
      (node (ref "U25") (pin "10") (pinfunction "VDD_10") (pintype "power_in"))
      (node (ref "U25") (pin "5") (pinfunction "EN_5") (pintype "input"))
      (node (ref "U25") (pin "6") (pinfunction "VDD/NC_6") (pintype "power_in"))
    )
    (net (code "165") (name "Net-(C29-Pad2)") (class "Default")
      (node (ref "C29") (pin "2") (pinfunction "2_2") (pintype "passive"))
      (node (ref "R38") (pin "2") (pinfunction "2_2") (pintype "passive"))
    )
    (net (code "166") (name "Net-(D1-PadC)") (class "Default")
      (node (ref "D1") (pin "C") (pinfunction "C_C") (pintype "passive"))
      (node (ref "R10") (pin "1") (pinfunction "1_1") (pintype "passive"))
    )
    (net (code "167") (name "Net-(D2-A)") (class "Default")
      (node (ref "C18") (pin "1") (pinfunction "1_1") (pintype "passive"))
      (node (ref "D2") (pin "2") (pinfunction "A_2") (pintype "bidirectional"))
      (node (ref "D3") (pin "1") (pinfunction "K_1") (pintype "bidirectional"))
    )
    (net (code "168") (name "Net-(D4-A)") (class "Default")
      (node (ref "C18") (pin "2") (pinfunction "2_2") (pintype "passive"))
      (node (ref "D4") (pin "2") (pinfunction "A_2") (pintype "bidirectional"))
      (node (ref "L3") (pin "2") (pinfunction "2_2") (pintype "passive"))
      (node (ref "Q1") (pin "3") (pinfunction "D_3") (pintype "bidirectional"))
    )
    (net (code "169") (name "Net-(D5-PadC)") (class "Default")
      (node (ref "D5") (pin "C") (pinfunction "C_C") (pintype "passive"))
      (node (ref "R22") (pin "1") (pinfunction "1_1") (pintype "passive"))
    )
    (net (code "170") (name "Net-(D6-PadC)") (class "Default")
      (node (ref "D6") (pin "C") (pinfunction "C_C") (pintype "passive"))
      (node (ref "R23") (pin "1") (pinfunction "1_1") (pintype "passive"))
    )
    (net (code "171") (name "Net-(D7-PadC)") (class "Default")
      (node (ref "D7") (pin "C") (pinfunction "C_C") (pintype "passive"))
      (node (ref "R14") (pin "1") (pinfunction "1_1") (pintype "passive"))
    )
    (net (code "172") (name "Net-(IC1-C1)") (class "Default")
      (node (ref "C31") (pin "1") (pinfunction "1_1") (pintype "passive"))
      (node (ref "IC1") (pin "4") (pinfunction "C1_4") (pintype "input"))
    )
    (net (code "173") (name "Net-(IC3-SPK_LN)") (class "Default")
      (node (ref "FB3") (pin "1") (pinfunction "1_1") (pintype "passive"))
      (node (ref "IC3") (pin "23") (pinfunction "SPK_LN_23") (pintype "output"))
    )
    (net (code "174") (name "Net-(IC3-SPK_LP)") (class "Default")
      (node (ref "FB2") (pin "1") (pinfunction "1_1") (pintype "passive"))
      (node (ref "IC3") (pin "25") (pinfunction "SPK_LP_25") (pintype "output"))
    )
    (net (code "175") (name "Net-(J2-CC1)") (class "Default")
      (node (ref "J2") (pin "A5") (pinfunction "CC1_A5") (pintype "bidirectional"))
      (node (ref "R19") (pin "2") (pinfunction "2_2") (pintype "passive"))
    )
    (net (code "176") (name "Net-(J2-CC2)") (class "Default")
      (node (ref "J2") (pin "B5") (pinfunction "CC2_B5") (pintype "bidirectional"))
      (node (ref "R21") (pin "2") (pinfunction "2_2") (pintype "passive"))
    )
    (net (code "177") (name "Net-(L1-2)") (class "Default")
      (node (ref "L1") (pin "P$2") (pinfunction "2_P$2") (pintype "passive"))
      (node (ref "U1") (pin "3") (pinfunction "SW_3") (pintype "input"))
      (node (ref "U1") (pin "4") (pinfunction "SW_4") (pintype "input"))
    )
    (net (code "178") (name "Net-(LED2-PadA)") (class "Default")
      (node (ref "LED2") (pin "A") (pinfunction "A_A") (pintype "passive"))
      (node (ref "R5") (pin "2") (pinfunction "2_2") (pintype "passive"))
    )
    (net (code "179") (name "Net-(LED3-PadA)") (class "Default")
      (node (ref "LED3") (pin "A") (pinfunction "A_A") (pintype "passive"))
      (node (ref "R8") (pin "1") (pinfunction "1_1") (pintype "passive"))
    )
    (net (code "180") (name "Net-(LOW_BATT-PadA)") (class "Default")
      (node (ref "LOW_BATT") (pin "A") (pinfunction "A_A") (pintype "passive"))
      (node (ref "R20") (pin "1") (pinfunction "1_1") (pintype "passive"))
    )
    (net (code "181") (name "Net-(Q2-G)") (class "Default")
      (node (ref "Q2") (pin "1") (pinfunction "G_1") (pintype "passive"))
      (node (ref "R43") (pin "2") (pinfunction "2_2") (pintype "passive"))
      (node (ref "R44") (pin "1") (pinfunction "1_1") (pintype "passive"))
    )
    (net (code "182") (name "Net-(Q4-D)") (class "Default")
      (node (ref "Q4") (pin "3") (pinfunction "D_3") (pintype "passive"))
      (node (ref "R34") (pin "2") (pinfunction "2_2") (pintype "passive"))
      (node (ref "USB_BOOT_N") (pin "P$1") (pinfunction "1_P$1") (pintype "bidirectional"))
    )
    (net (code "183") (name "Net-(R20-Pad2)") (class "Default")
      (node (ref "R20") (pin "2") (pinfunction "2_2") (pintype "passive"))
      (node (ref "T1") (pin "C") (pinfunction "C_C") (pintype "passive"))
    )
    (net (code "184") (name "Net-(RPI-CM1A-GPIO_VREF)") (class "Default")
      (node (ref "RPI-CM1") (pin "78") (pinfunction "GPIO_VREF_78") (pintype "passive"))
      (node (ref "SJ6") (pin "2") (pinfunction "2_2") (pintype "passive"))
    )
    (net (code "185") (name "Net-(RPI-CM1A-PI_LED_~{PWR})") (class "Default")
      (node (ref "RPI-CM1") (pin "95") (pinfunction "PI_LED_~{PWR}_95") (pintype "passive"))
      (node (ref "U2") (pin "2") (pinfunction "IN_A_2") (pintype "input"))
    )
    (net (code "186") (name "Net-(RPI-CM1A-PI_~{LED_ACTIVITY})") (class "Default")
      (node (ref "R10") (pin "2") (pinfunction "2_2") (pintype "passive"))
      (node (ref "RPI-CM1") (pin "21") (pinfunction "PI_~{LED_ACTIVITY}_21") (pintype "passive"))
    )
    (net (code "187") (name "Net-(U1-EN)") (class "Default")
      (node (ref "R13") (pin "2") (pinfunction "2_2") (pintype "passive"))
      (node (ref "U1") (pin "11") (pinfunction "EN_11") (pintype "input"))
    )
    (net (code "188") (name "Net-(U1-FB)") (class "Default")
      (node (ref "R3") (pin "1") (pinfunction "1_1") (pintype "passive"))
      (node (ref "R4") (pin "2") (pinfunction "2_2") (pintype "passive"))
      (node (ref "U1") (pin "14") (pinfunction "FB_14") (pintype "input"))
    )
    (net (code "189") (name "Net-(U1-LBI)") (class "Default")
      (node (ref "R1") (pin "1") (pinfunction "1_1") (pintype "passive"))
      (node (ref "R2") (pin "2") (pinfunction "2_2") (pintype "passive"))
      (node (ref "U1") (pin "9") (pinfunction "LBI_9") (pintype "input"))
    )
    (net (code "190") (name "Net-(U2-OUT_~{Y})") (class "Default")
      (node (ref "R8") (pin "2") (pinfunction "2_2") (pintype "passive"))
      (node (ref "U2") (pin "4") (pinfunction "OUT_~{Y}_4") (pintype "output"))
    )
    (net (code "191") (name "Net-(U4-ILIM)") (class "Default")
      (node (ref "R7") (pin "1") (pinfunction "1_1") (pintype "passive"))
      (node (ref "U4") (pin "12") (pinfunction "ILIM_12") (pintype "bidirectional"))
    )
    (net (code "192") (name "Net-(U4-ISET)") (class "Default")
      (node (ref "R6") (pin "1") (pinfunction "1_1") (pintype "passive"))
      (node (ref "U4") (pin "16") (pinfunction "ISET_16") (pintype "bidirectional"))
    )
    (net (code "193") (name "Net-(U4-~{CHG})") (class "Default")
      (node (ref "R22") (pin "2") (pinfunction "2_2") (pintype "passive"))
      (node (ref "U4") (pin "9") (pinfunction "~{CHG}_9") (pintype "bidirectional"))
    )
    (net (code "194") (name "Net-(U5-OUT_~{Y})") (class "Default")
      (node (ref "R44") (pin "2") (pinfunction "2_2") (pintype "passive"))
      (node (ref "U5") (pin "4") (pinfunction "OUT_~{Y}_4") (pintype "output"))
    )
    (net (code "195") (name "Net-(U10-OUT)") (class "Default")
      (node (ref "C62") (pin "1") (pinfunction "1_1") (pintype "passive"))
      (node (ref "C69") (pin "1") (pinfunction "1_1") (pintype "passive"))
      (node (ref "FB1") (pin "1") (pinfunction "1_1") (pintype "passive"))
      (node (ref "U10") (pin "5") (pinfunction "OUT_5") (pintype "power_in"))
    )
    (net (code "196") (name "Net-(U12-OUTPUT)") (class "Default")
      (node (ref "C29") (pin "1") (pinfunction "1_1") (pintype "passive"))
      (node (ref "U12") (pin "1") (pinfunction "OUTPUT_1") (pintype "output"))
    )
    (net (code "197") (name "Net-(U14A-+IN)") (class "Default")
      (node (ref "C30") (pin "1") (pinfunction "1_1") (pintype "passive"))
      (node (ref "R27") (pin "1") (pinfunction "1_1") (pintype "passive"))
      (node (ref "R37") (pin "2") (pinfunction "2_2") (pintype "passive"))
      (node (ref "U14") (pin "3") (pinfunction "+IN_3") (pintype "input"))
    )
    (net (code "198") (name "Net-(U14A--IN)") (class "Default")
      (node (ref "C27") (pin "1") (pinfunction "1_1") (pintype "passive"))
      (node (ref "R38") (pin "1") (pinfunction "1_1") (pintype "passive"))
      (node (ref "R39") (pin "2") (pinfunction "2_2") (pintype "passive"))
      (node (ref "U14") (pin "4") (pinfunction "-IN_4") (pintype "input"))
    )
    (net (code "199") (name "Net-(U25-REG)") (class "Default")
      (node (ref "C34") (pin "2") (pinfunction "2_2") (pintype "passive"))
      (node (ref "U25") (pin "1") (pinfunction "REG_1") (pintype "output"))
    )
    (net (code "200") (name "Net-(Y1-CRYSTAL_2)") (class "Default")
      (node (ref "C83") (pin "2") (pinfunction "2_2") (pintype "passive"))
      (node (ref "R35") (pin "2") (pinfunction "2_2") (pintype "passive"))
      (node (ref "Y1") (pin "3") (pinfunction "CRYSTAL_2_3") (pintype "bidirectional"))
    )
    (net (code "201") (name "PREVGH") (class "Default")
      (node (ref "C16") (pin "1") (pinfunction "1_1") (pintype "passive"))
      (node (ref "D4") (pin "1") (pinfunction "K_1") (pintype "bidirectional"))
      (node (ref "EINK_524352471") (pin "4") (pinfunction "4_4") (pintype "passive"))
    )
    (net (code "202") (name "PREVGL") (class "Default")
      (node (ref "C14") (pin "1") (pinfunction "1_1") (pintype "passive"))
      (node (ref "D3") (pin "2") (pinfunction "A_2") (pintype "bidirectional"))
      (node (ref "EINK_524352471") (pin "2") (pinfunction "2_2") (pintype "passive"))
    )
    (net (code "203") (name "SAM_1V1") (class "Default")
      (node (ref "C2040") (pin "23") (pinfunction "DVDD_2_23") (pintype "power_in"))
      (node (ref "C2040") (pin "45") (pinfunction "VREG_VOUT_45") (pintype "output"))
      (node (ref "C2040") (pin "50") (pinfunction "DVDD_50") (pintype "power_in"))
      (node (ref "C76") (pin "1") (pinfunction "1_1") (pintype "passive"))
      (node (ref "C77") (pin "1") (pinfunction "1_1") (pintype "passive"))
    )
    (net (code "204") (name "SAM_3V3") (class "Default")
      (node (ref "BUD") (pin "1_1") (pinfunction "1_1_1") (pintype "passive"))
      (node (ref "BUD") (pin "1_2") (pinfunction "1_1_2") (pintype "passive"))
      (node (ref "BUP") (pin "1_1") (pinfunction "1_1_1") (pintype "passive"))
      (node (ref "BUP") (pin "1_2") (pinfunction "1_1_2") (pintype "passive"))
      (node (ref "BUS") (pin "1_1") (pinfunction "1_1_1") (pintype "passive"))
      (node (ref "BUS") (pin "1_2") (pinfunction "1_1_2") (pintype "passive"))
      (node (ref "C2040") (pin "1") (pinfunction "IOVDD_2_1") (pintype "power_in"))
      (node (ref "C2040") (pin "10") (pinfunction "IOVDD_3_10") (pintype "power_in"))
      (node (ref "C2040") (pin "22") (pinfunction "IOVDD_4_22") (pintype "power_in"))
      (node (ref "C2040") (pin "33") (pinfunction "IOVDD_5_33") (pintype "power_in"))
      (node (ref "C2040") (pin "42") (pinfunction "IOVDD_6_42") (pintype "power_in"))
      (node (ref "C2040") (pin "43") (pinfunction "ADC_AVDD_43") (pintype "power_in"))
      (node (ref "C2040") (pin "44") (pinfunction "VREG_VIN_44") (pintype "power_in"))
      (node (ref "C2040") (pin "48") (pinfunction "USB_VDD_48") (pintype "power_in"))
      (node (ref "C2040") (pin "49") (pinfunction "IOVDD_49") (pintype "power_in"))
      (node (ref "C24") (pin "2") (pinfunction "2_2") (pintype "passive"))
      (node (ref "C43") (pin "1") (pinfunction "1_1") (pintype "passive"))
      (node (ref "C44") (pin "1") (pinfunction "1_1") (pintype "passive"))
      (node (ref "C7") (pin "1") (pinfunction "1_1") (pintype "passive"))
      (node (ref "C71") (pin "1") (pinfunction "1_1") (pintype "passive"))
      (node (ref "C72") (pin "1") (pinfunction "1_1") (pintype "passive"))
      (node (ref "C73") (pin "1") (pinfunction "1_1") (pintype "passive"))
      (node (ref "C74") (pin "1") (pinfunction "1_1") (pintype "passive"))
      (node (ref "C75") (pin "1") (pinfunction "1_1") (pintype "passive"))
      (node (ref "C80") (pin "1") (pinfunction "1_1") (pintype "passive"))
      (node (ref "D7") (pin "A") (pinfunction "A_A") (pintype "passive"))
      (node (ref "J4") (pin "1") (pinfunction "1_1") (pintype "passive"))
      (node (ref "Q2") (pin "2") (pinfunction "S_2") (pintype "passive"))
      (node (ref "R16") (pin "2") (pinfunction "2_2") (pintype "passive"))
      (node (ref "R17") (pin "2") (pinfunction "2_2") (pintype "passive"))
      (node (ref "R25") (pin "2") (pinfunction "2_2") (pintype "passive"))
      (node (ref "R26") (pin "2") (pinfunction "2_2") (pintype "passive"))
      (node (ref "R28") (pin "2") (pinfunction "2_2") (pintype "passive"))
      (node (ref "R40") (pin "2") (pinfunction "2_2") (pintype "passive"))
      (node (ref "R42") (pin "2") (pinfunction "2_2") (pintype "passive"))
      (node (ref "R43") (pin "1") (pinfunction "1_1") (pintype "passive"))
      (node (ref "U11") (pin "5") (pinfunction "OUT_5") (pintype "power_in"))
      (node (ref "U16") (pin "8") (pinfunction "VCC_8") (pintype "power_in"))
      (node (ref "U5") (pin "5") (pinfunction "VCC_5") (pintype "power_in"))
      (node (ref "U7") (pin "19") (pinfunction "VCC_19") (pintype "power_in"))
      (node (ref "USB2.0MUX") (pin "9") (pinfunction "VCC_9") (pintype "power_in"))
    )
    (net (code "205") (name "SAM_QSPI_SCN") (class "Default")
      (node (ref "C2040") (pin "56") (pinfunction "QSPI_SCN_56") (pintype "bidirectional"))
      (node (ref "R34") (pin "1") (pinfunction "1_1") (pintype "passive"))
      (node (ref "U16") (pin "1") (pinfunction "~{CS}_1") (pintype "input"))
    )
    (net (code "206") (name "SAM_SCL") (class "Default")
      (node (ref "C2040") (pin "37") (pinfunction "GPIO25_37") (pintype "bidirectional"))
      (node (ref "J4") (pin "3") (pinfunction "3_3") (pintype "passive"))
      (node (ref "R26") (pin "1") (pinfunction "1_1") (pintype "passive"))
      (node (ref "RPIBOOT8") (pin "P$1") (pinfunction "1_P$1") (pintype "bidirectional"))
      (node (ref "U25") (pin "2") (pinfunction "SCL_2") (pintype "input"))
      (node (ref "U3") (pin "2") (pinfunction "SCL_2") (pintype "bidirectional"))
    )
    (net (code "207") (name "SAM_SDA") (class "Default")
      (node (ref "C2040") (pin "36") (pinfunction "GPIO24_36") (pintype "bidirectional"))
      (node (ref "GND37") (pin "P$1") (pinfunction "1_P$1") (pintype "bidirectional"))
      (node (ref "J4") (pin "2") (pinfunction "2_2") (pintype "passive"))
      (node (ref "R25") (pin "1") (pinfunction "1_1") (pintype "passive"))
      (node (ref "U25") (pin "3") (pinfunction "SDA_3") (pintype "bidirectional"))
      (node (ref "U3") (pin "1") (pinfunction "SDA_1") (pintype "bidirectional"))
    )
    (net (code "208") (name "SCL1") (class "Default")
      (node (ref "IC1") (pin "1") (pinfunction "SCL_1") (pintype "input"))
      (node (ref "IC3") (pin "17") (pinfunction "SCL_17") (pintype "input"))
      (node (ref "R18") (pin "1") (pinfunction "1_1") (pintype "passive"))
      (node (ref "RPI-CM1") (pin "56") (pinfunction "GPIO3_56") (pintype "passive"))
      (node (ref "RPIBOOT6") (pin "P$1") (pinfunction "1_P$1") (pintype "bidirectional"))
      (node (ref "U6") (pin "13") (pinfunction "SCL_13") (pintype "bidirectional"))
      (node (ref "U9") (pin "2") (pinfunction "SMCLK_2") (pintype "input"))
    )
    (net (code "209") (name "SDA1") (class "Default")
      (node (ref "GND7") (pin "P$1") (pinfunction "1_P$1") (pintype "bidirectional"))
      (node (ref "IC1") (pin "11") (pinfunction "SDA_11") (pintype "bidirectional"))
      (node (ref "IC3") (pin "18") (pinfunction "SDA_18") (pintype "bidirectional"))
      (node (ref "R15") (pin "1") (pinfunction "1_1") (pintype "passive"))
      (node (ref "RPI-CM1") (pin "58") (pinfunction "GPIO2_58") (pintype "passive"))
      (node (ref "U6") (pin "14") (pinfunction "SDA_14") (pintype "bidirectional"))
      (node (ref "U9") (pin "1") (pinfunction "SMDATA_1") (pintype "bidirectional"))
    )
    (net (code "210") (name "THERM") (class "Default")
      (node (ref "J1") (pin "2") (pinfunction "2_2") (pintype "passive"))
      (node (ref "SJ1") (pin "1") (pinfunction "1_1") (pintype "passive"))
    )
    (net (code "211") (name "TS") (class "Default")
      (node (ref "SJ1") (pin "2") (pinfunction "2_2") (pintype "passive"))
      (node (ref "U3") (pin "10") (pinfunction "BIN_10") (pintype "bidirectional"))
      (node (ref "U4") (pin "1") (pinfunction "TS_1") (pintype "bidirectional"))
    )
    (net (code "212") (name "UART_RXD3_SAM") (class "Default")
      (node (ref "C2040") (pin "2") (pinfunction "GPIO0_2") (pintype "bidirectional"))
      (node (ref "R40") (pin "1") (pinfunction "1_1") (pintype "passive"))
      (node (ref "RPI-CM1") (pin "34") (pinfunction "GPIO5_34") (pintype "passive"))
      (node (ref "RPIBOOT7") (pin "P$1") (pinfunction "1_P$1") (pintype "bidirectional"))
    )
    (net (code "213") (name "UART_TXD3_SAM") (class "Default")
      (node (ref "C2040") (pin "3") (pinfunction "GPIO1_3") (pintype "bidirectional"))
      (node (ref "GND36") (pin "P$1") (pinfunction "1_P$1") (pintype "bidirectional"))
      (node (ref "R42") (pin "1") (pinfunction "1_1") (pintype "passive"))
      (node (ref "RPI-CM1") (pin "54") (pinfunction "GPIO4_54") (pintype "passive"))
    )
    (net (code "214") (name "USB_N") (class "Default")
      (node (ref "J2") (pin "A7") (pinfunction "D-_A7") (pintype "bidirectional"))
      (node (ref "J2") (pin "B7") (pinfunction "D-_B7") (pintype "bidirectional"))
      (node (ref "RPI-CM1") (pin "103") (pinfunction "USB_N_103") (pintype "passive"))
      (node (ref "U13") (pin "5") (pinfunction "D2-_5") (pintype "passive"))
      (node (ref "USB2.0MUX") (pin "5") (pinfunction "D-_5") (pintype "bidirectional"))
    )
    (net (code "215") (name "USB_P") (class "Default")
      (node (ref "J2") (pin "A6") (pinfunction "D+_A6") (pintype "bidirectional"))
      (node (ref "J2") (pin "B6") (pinfunction "D+_B6") (pintype "bidirectional"))
      (node (ref "RPI-CM1") (pin "105") (pinfunction "USB_P_105") (pintype "passive"))
      (node (ref "U13") (pin "4") (pinfunction "D2+_4") (pintype "passive"))
      (node (ref "USB2.0MUX") (pin "3") (pinfunction "D+_3") (pintype "bidirectional"))
    )
    (net (code "216") (name "USB_SAM_N") (class "Default")
      (node (ref "R32") (pin "1") (pinfunction "1_1") (pintype "passive"))
      (node (ref "USB2.0MUX") (pin "7") (pinfunction "D1-_7") (pintype "bidirectional"))
    )
    (net (code "217") (name "USB_SAM_P") (class "Default")
      (node (ref "R31") (pin "1") (pinfunction "1_1") (pintype "passive"))
      (node (ref "USB2.0MUX") (pin "1") (pinfunction "D1+_1") (pintype "bidirectional"))
    )
    (net (code "218") (name "VBUS") (class "Default")
      (node (ref "C22") (pin "1") (pinfunction "1_1") (pintype "passive"))
      (node (ref "C3") (pin "1") (pinfunction "1_1") (pintype "passive"))
      (node (ref "C53") (pin "1") (pinfunction "1_1") (pintype "passive"))
      (node (ref "J2") (pin "VBUS1") (pinfunction "VBUS_VBUS1") (pintype "bidirectional"))
      (node (ref "J2") (pin "VBUS2") (pinfunction "VBUS_VBUS2") (pintype "bidirectional"))
      (node (ref "U4") (pin "13") (pinfunction "IN_13") (pintype "bidirectional"))
    )
    (net (code "219") (name "VOUT") (class "Default")
      (node (ref "C1") (pin "1") (pinfunction "1_1") (pintype "passive"))
      (node (ref "C21") (pin "1") (pinfunction "1_1") (pintype "passive"))
      (node (ref "C26") (pin "1") (pinfunction "1_1") (pintype "passive"))
      (node (ref "C32") (pin "1") (pinfunction "1_1") (pintype "passive"))
      (node (ref "C4") (pin "1") (pinfunction "1_1") (pintype "passive"))
      (node (ref "C79") (pin "1") (pinfunction "1_1") (pintype "passive"))
      (node (ref "D5") (pin "A") (pinfunction "A_A") (pintype "passive"))
      (node (ref "D6") (pin "A") (pinfunction "A_A") (pintype "passive"))
      (node (ref "L1") (pin "P$1") (pinfunction "1_P$1") (pintype "passive"))
      (node (ref "R1") (pin "2") (pinfunction "2_2") (pintype "passive"))
      (node (ref "R36") (pin "1") (pinfunction "1_1") (pintype "passive"))
      (node (ref "RPIBOOT4") (pin "P$1") (pinfunction "1_P$1") (pintype "bidirectional"))
      (node (ref "T1") (pin "E") (pinfunction "E_E") (pintype "passive"))
      (node (ref "U1") (pin "8") (pinfunction "VBAT_8") (pintype "input"))
      (node (ref "U11") (pin "1") (pinfunction "IN_1") (pintype "power_in"))
      (node (ref "U11") (pin "3") (pinfunction "EN_3") (pintype "input"))
      (node (ref "U15") (pin "1") (pinfunction "IN_1") (pintype "power_in"))
      (node (ref "U15") (pin "3") (pinfunction "EN_3") (pintype "input"))
      (node (ref "U4") (pin "10") (pinfunction "OUT_10") (pintype "bidirectional"))
      (node (ref "U4") (pin "11") (pinfunction "OUT_11") (pintype "bidirectional"))
      (node (ref "U4") (pin "5") (pinfunction "EN2_5") (pintype "bidirectional"))
    )
    (net (code "220") (name "V_BATT") (class "Default")
      (node (ref "C23") (pin "1") (pinfunction "1_1") (pintype "passive"))
      (node (ref "C40") (pin "1") (pinfunction "1_1") (pintype "passive"))
      (node (ref "R12") (pin "1") (pinfunction "1_1") (pintype "passive"))
      (node (ref "RPIBOOT5") (pin "P$1") (pinfunction "1_P$1") (pintype "bidirectional"))
      (node (ref "U3") (pin "7") (pinfunction "SRN_7") (pintype "bidirectional"))
      (node (ref "U4") (pin "2") (pinfunction "BAT_2") (pintype "bidirectional"))
      (node (ref "U4") (pin "3") (pinfunction "BAT_3") (pintype "bidirectional"))
    )
    (net (code "221") (name "unconnected-(C2040-GPIO20-Pad31)") (class "Default")
      (node (ref "C2040") (pin "31") (pinfunction "GPIO20_31") (pintype "bidirectional"))
    )
    (net (code "222") (name "unconnected-(CAMERA-Pad18)") (class "Default")
      (node (ref "CAMERA") (pin "18") (pinfunction "18_18") (pintype "passive"))
    )
    (net (code "223") (name "unconnected-(IC1-CS-Pad10)") (class "Default")
      (node (ref "IC1") (pin "10") (pinfunction "CS_10") (pintype "input"))
    )
    (net (code "224") (name "unconnected-(IC1-DRDY-Pad8)") (class "Default")
      (node (ref "IC1") (pin "8") (pinfunction "DRDY_8") (pintype "output"))
    )
    (net (code "225") (name "unconnected-(IC1-INT-Pad7)") (class "Default")
      (node (ref "IC1") (pin "7") (pinfunction "INT_7") (pintype "output"))
    )
    (net (code "226") (name "unconnected-(IC3-HP_L-Pad31)") (class "Default")
      (node (ref "IC3") (pin "31") (pinfunction "HP_L_31") (pintype "output"))
    )
    (net (code "227") (name "unconnected-(IC3-HP_R-Pad29)") (class "Default")
      (node (ref "IC3") (pin "29") (pinfunction "HP_R_29") (pintype "output"))
    )
    (net (code "228") (name "unconnected-(IC3-LINPUT1-Pad4)") (class "Default")
      (node (ref "IC3") (pin "4") (pinfunction "LINPUT1_4") (pintype "input"))
    )
    (net (code "229") (name "unconnected-(IC3-LINPUT2-Pad3)") (class "Default")
      (node (ref "IC3") (pin "3") (pinfunction "LINPUT2_3") (pintype "input"))
    )
    (net (code "230") (name "unconnected-(IC3-LINPUT3-Pad2)") (class "Default")
      (node (ref "IC3") (pin "2") (pinfunction "LINPUT3_2") (pintype "input"))
    )
    (net (code "231") (name "unconnected-(IC3-OUT3-Pad30)") (class "Default")
      (node (ref "IC3") (pin "30") (pinfunction "OUT3_30") (pintype "output"))
    )
    (net (code "232") (name "unconnected-(IC3-RINPUT2-Pad6)") (class "Default")
      (node (ref "IC3") (pin "6") (pinfunction "RINPUT2_6") (pintype "input"))
    )
    (net (code "233") (name "unconnected-(IC3-RINPUT3-Pad7)") (class "Default")
      (node (ref "IC3") (pin "7") (pinfunction "RINPUT3_7") (pintype "input"))
    )
    (net (code "234") (name "unconnected-(IC3-SPK_RN-Pad19)") (class "Default")
      (node (ref "IC3") (pin "19") (pinfunction "SPK_RN_19") (pintype "output"))
    )
    (net (code "235") (name "unconnected-(IC3-SPK_RP-Pad22)") (class "Default")
      (node (ref "IC3") (pin "22") (pinfunction "SPK_RP_22") (pintype "output"))
    )
    (net (code "236") (name "unconnected-(M.2KEYM(NGFF)-P5-Pad5)") (class "Default")
      (node (ref "M.2KEYM(NGFF)") (pin "5") (pinfunction "P5_5") (pintype "passive"))
    )
    (net (code "237") (name "unconnected-(M.2KEYM(NGFF)-P6-Pad6)") (class "Default")
      (node (ref "M.2KEYM(NGFF)") (pin "6") (pinfunction "P6_6") (pintype "passive"))
    )
    (net (code "238") (name "unconnected-(M.2KEYM(NGFF)-P7-Pad7)") (class "Default")
      (node (ref "M.2KEYM(NGFF)") (pin "7") (pinfunction "P7_7") (pintype "passive"))
    )
    (net (code "239") (name "unconnected-(M.2KEYM(NGFF)-P8-Pad8)") (class "Default")
      (node (ref "M.2KEYM(NGFF)") (pin "8") (pinfunction "P8_8") (pintype "passive"))
    )
    (net (code "240") (name "unconnected-(M.2KEYM(NGFF)-P10-Pad10)") (class "Default")
      (node (ref "M.2KEYM(NGFF)") (pin "10") (pinfunction "P10_10") (pintype "passive"))
    )
    (net (code "241") (name "unconnected-(M.2KEYM(NGFF)-P11-Pad11)") (class "Default")
      (node (ref "M.2KEYM(NGFF)") (pin "11") (pinfunction "P11_11") (pintype "passive"))
    )
    (net (code "242") (name "unconnected-(M.2KEYM(NGFF)-P13-Pad13)") (class "Default")
      (node (ref "M.2KEYM(NGFF)") (pin "13") (pinfunction "P13_13") (pintype "passive"))
    )
    (net (code "243") (name "unconnected-(M.2KEYM(NGFF)-P17-Pad17)") (class "Default")
      (node (ref "M.2KEYM(NGFF)") (pin "17") (pinfunction "P17_17") (pintype "passive"))
    )
    (net (code "244") (name "unconnected-(M.2KEYM(NGFF)-P19-Pad19)") (class "Default")
      (node (ref "M.2KEYM(NGFF)") (pin "19") (pinfunction "P19_19") (pintype "passive"))
    )
    (net (code "245") (name "unconnected-(M.2KEYM(NGFF)-P20-Pad20)") (class "Default")
      (node (ref "M.2KEYM(NGFF)") (pin "20") (pinfunction "P20_20") (pintype "passive"))
    )
    (net (code "246") (name "unconnected-(M.2KEYM(NGFF)-P22-Pad22)") (class "Default")
      (node (ref "M.2KEYM(NGFF)") (pin "22") (pinfunction "P22_22") (pintype "passive"))
    )
    (net (code "247") (name "unconnected-(M.2KEYM(NGFF)-P23-Pad23)") (class "Default")
      (node (ref "M.2KEYM(NGFF)") (pin "23") (pinfunction "P23_23") (pintype "passive"))
    )
    (net (code "248") (name "unconnected-(M.2KEYM(NGFF)-P24-Pad24)") (class "Default")
      (node (ref "M.2KEYM(NGFF)") (pin "24") (pinfunction "P24_24") (pintype "passive"))
    )
    (net (code "249") (name "unconnected-(M.2KEYM(NGFF)-P25-Pad25)") (class "Default")
      (node (ref "M.2KEYM(NGFF)") (pin "25") (pinfunction "P25_25") (pintype "passive"))
    )
    (net (code "250") (name "unconnected-(M.2KEYM(NGFF)-P26-Pad26)") (class "Default")
      (node (ref "M.2KEYM(NGFF)") (pin "26") (pinfunction "P26_26") (pintype "passive"))
    )
    (net (code "251") (name "unconnected-(M.2KEYM(NGFF)-P28-Pad28)") (class "Default")
      (node (ref "M.2KEYM(NGFF)") (pin "28") (pinfunction "P28_28") (pintype "passive"))
    )
    (net (code "252") (name "unconnected-(M.2KEYM(NGFF)-P29-Pad29)") (class "Default")
      (node (ref "M.2KEYM(NGFF)") (pin "29") (pinfunction "P29_29") (pintype "passive"))
    )
    (net (code "253") (name "unconnected-(M.2KEYM(NGFF)-P30-Pad30)") (class "Default")
      (node (ref "M.2KEYM(NGFF)") (pin "30") (pinfunction "P30_30") (pintype "passive"))
    )
    (net (code "254") (name "unconnected-(M.2KEYM(NGFF)-P31-Pad31)") (class "Default")
      (node (ref "M.2KEYM(NGFF)") (pin "31") (pinfunction "P31_31") (pintype "passive"))
    )
    (net (code "255") (name "unconnected-(M.2KEYM(NGFF)-P32-Pad32)") (class "Default")
      (node (ref "M.2KEYM(NGFF)") (pin "32") (pinfunction "P32_32") (pintype "passive"))
    )
    (net (code "256") (name "unconnected-(M.2KEYM(NGFF)-P34-Pad34)") (class "Default")
      (node (ref "M.2KEYM(NGFF)") (pin "34") (pinfunction "P34_34") (pintype "passive"))
    )
    (net (code "257") (name "unconnected-(M.2KEYM(NGFF)-P35-Pad35)") (class "Default")
      (node (ref "M.2KEYM(NGFF)") (pin "35") (pinfunction "P35_35") (pintype "passive"))
    )
    (net (code "258") (name "unconnected-(M.2KEYM(NGFF)-P36-Pad36)") (class "Default")
      (node (ref "M.2KEYM(NGFF)") (pin "36") (pinfunction "P36_36") (pintype "passive"))
    )
    (net (code "259") (name "unconnected-(M.2KEYM(NGFF)-P37-Pad37)") (class "Default")
      (node (ref "M.2KEYM(NGFF)") (pin "37") (pinfunction "P37_37") (pintype "passive"))
    )
    (net (code "260") (name "unconnected-(M.2KEYM(NGFF)-P38-Pad38)") (class "Default")
      (node (ref "M.2KEYM(NGFF)") (pin "38") (pinfunction "P38_38") (pintype "passive"))
    )
    (net (code "261") (name "unconnected-(M.2KEYM(NGFF)-P40-Pad40)") (class "Default")
      (node (ref "M.2KEYM(NGFF)") (pin "40") (pinfunction "P40_40") (pintype "passive"))
    )
    (net (code "262") (name "unconnected-(M.2KEYM(NGFF)-P42-Pad42)") (class "Default")
      (node (ref "M.2KEYM(NGFF)") (pin "42") (pinfunction "P42_42") (pintype "passive"))
    )
    (net (code "263") (name "unconnected-(M.2KEYM(NGFF)-P44-Pad44)") (class "Default")
      (node (ref "M.2KEYM(NGFF)") (pin "44") (pinfunction "P44_44") (pintype "passive"))
    )
    (net (code "264") (name "unconnected-(M.2KEYM(NGFF)-P46-Pad46)") (class "Default")
      (node (ref "M.2KEYM(NGFF)") (pin "46") (pinfunction "P46_46") (pintype "passive"))
    )
    (net (code "265") (name "unconnected-(M.2KEYM(NGFF)-P48-Pad48)") (class "Default")
      (node (ref "M.2KEYM(NGFF)") (pin "48") (pinfunction "P48_48") (pintype "passive"))
    )
    (net (code "266") (name "unconnected-(M.2KEYM(NGFF)-P54-Pad54)") (class "Default")
      (node (ref "M.2KEYM(NGFF)") (pin "54") (pinfunction "P54_54") (pintype "passive"))
    )
    (net (code "267") (name "unconnected-(M.2KEYM(NGFF)-P56-Pad56)") (class "Default")
      (node (ref "M.2KEYM(NGFF)") (pin "56") (pinfunction "P56_56") (pintype "passive"))
    )
    (net (code "268") (name "unconnected-(M.2KEYM(NGFF)-P58-Pad58)") (class "Default")
      (node (ref "M.2KEYM(NGFF)") (pin "58") (pinfunction "P58_58") (pintype "passive"))
    )
    (net (code "269") (name "unconnected-(M.2KEYM(NGFF)-P67-Pad67)") (class "Default")
      (node (ref "M.2KEYM(NGFF)") (pin "67") (pinfunction "P67_67") (pintype "passive"))
    )
    (net (code "270") (name "unconnected-(M.2KEYM(NGFF)-P68-Pad68)") (class "Default")
      (node (ref "M.2KEYM(NGFF)") (pin "68") (pinfunction "P68_68") (pintype "passive"))
    )
    (net (code "271") (name "unconnected-(M.2KEYM(NGFF)-P69-Pad69)") (class "Default")
      (node (ref "M.2KEYM(NGFF)") (pin "69") (pinfunction "P69_69") (pintype "passive"))
    )
    (net (code "272") (name "unconnected-(RPI-CM1A-ANALOGP0-Pad96)") (class "Default")
      (node (ref "RPI-CM1") (pin "96") (pinfunction "ANALOGP0_96") (pintype "passive"))
    )
    (net (code "273") (name "unconnected-(RPI-CM1A-ANALOGP1-Pad94)") (class "Default")
      (node (ref "RPI-CM1") (pin "94") (pinfunction "ANALOGP1_94") (pintype "passive"))
    )
    (net (code "274") (name "unconnected-(RPI-CM1A-BT_~{DISABLE}-Pad91)") (class "Default")
      (node (ref "RPI-CM1") (pin "91") (pinfunction "BT_~{DISABLE}_91") (pintype "passive"))
    )
    (net (code "275") (name "unconnected-(RPI-CM1A-EEPROM_~{WP}-Pad20)") (class "Default")
      (node (ref "RPI-CM1") (pin "20") (pinfunction "EEPROM_~{WP}_20") (pintype "passive"))
    )
    (net (code "276") (name "unconnected-(RPI-CM1A-ETH_PAIR0_N-Pad10)") (class "Default")
      (node (ref "RPI-CM1") (pin "10") (pinfunction "ETH_PAIR0_N_10") (pintype "passive"))
    )
    (net (code "277") (name "unconnected-(RPI-CM1A-ETH_PAIR0_P-Pad12)") (class "Default")
      (node (ref "RPI-CM1") (pin "12") (pinfunction "ETH_PAIR0_P_12") (pintype "passive"))
    )
    (net (code "278") (name "unconnected-(RPI-CM1A-ETH_PAIR1_N-Pad6)") (class "Default")
      (node (ref "RPI-CM1") (pin "6") (pinfunction "ETH_PAIR1_N_6") (pintype "passive"))
    )
    (net (code "279") (name "unconnected-(RPI-CM1A-ETH_PAIR1_P-Pad4)") (class "Default")
      (node (ref "RPI-CM1") (pin "4") (pinfunction "ETH_PAIR1_P_4") (pintype "passive"))
    )
    (net (code "280") (name "unconnected-(RPI-CM1A-ETH_PAIR2_N-Pad9)") (class "Default")
      (node (ref "RPI-CM1") (pin "9") (pinfunction "ETH_PAIR2_N_9") (pintype "passive"))
    )
    (net (code "281") (name "unconnected-(RPI-CM1A-ETH_PAIR2_P-Pad11)") (class "Default")
      (node (ref "RPI-CM1") (pin "11") (pinfunction "ETH_PAIR2_P_11") (pintype "passive"))
    )
    (net (code "282") (name "unconnected-(RPI-CM1A-ETH_PAIR3_N-Pad5)") (class "Default")
      (node (ref "RPI-CM1") (pin "5") (pinfunction "ETH_PAIR3_N_5") (pintype "passive"))
    )
    (net (code "283") (name "unconnected-(RPI-CM1A-ETH_PAIR3_P-Pad3)") (class "Default")
      (node (ref "RPI-CM1") (pin "3") (pinfunction "ETH_PAIR3_P_3") (pintype "passive"))
    )
    (net (code "284") (name "unconnected-(RPI-CM1A-ETH_SYNC_IN-Pad16)") (class "Default")
      (node (ref "RPI-CM1") (pin "16") (pinfunction "ETH_SYNC_IN_16") (pintype "passive"))
    )
    (net (code "285") (name "unconnected-(RPI-CM1A-ETH_SYNC_OUT-Pad18)") (class "Default")
      (node (ref "RPI-CM1") (pin "18") (pinfunction "ETH_SYNC_OUT_18") (pintype "passive"))
    )
    (net (code "286") (name "unconnected-(RPI-CM1A-ETH_~{LED1}-Pad19)") (class "Default")
      (node (ref "RPI-CM1") (pin "19") (pinfunction "ETH_~{LED1}_19") (pintype "passive"))
    )
    (net (code "287") (name "unconnected-(RPI-CM1A-ETH_~{LED2}-Pad17)") (class "Default")
      (node (ref "RPI-CM1") (pin "17") (pinfunction "ETH_~{LED2}_17") (pintype "passive"))
    )
    (net (code "288") (name "unconnected-(RPI-CM1A-ETH_~{LED3}-Pad15)") (class "Default")
      (node (ref "RPI-CM1") (pin "15") (pinfunction "ETH_~{LED3}_15") (pintype "passive"))
    )
    (net (code "289") (name "unconnected-(RPI-CM1A-GLOBAL_EN-Pad99)") (class "Default")
      (node (ref "RPI-CM1") (pin "99") (pinfunction "GLOBAL_EN_99") (pintype "passive"))
    )
    (net (code "290") (name "unconnected-(RPI-CM1A-GPIO7-Pad37)") (class "Default")
      (node (ref "RPI-CM1") (pin "37") (pinfunction "GPIO7_37") (pintype "passive"))
    )
    (net (code "291") (name "unconnected-(RPI-CM1A-GPIO12-Pad31)") (class "Default")
      (node (ref "RPI-CM1") (pin "31") (pinfunction "GPIO12_31") (pintype "passive"))
    )
    (net (code "292") (name "unconnected-(RPI-CM1A-GPIO17-Pad50)") (class "Default")
      (node (ref "RPI-CM1") (pin "50") (pinfunction "GPIO17_50") (pintype "passive"))
    )
    (net (code "293") (name "unconnected-(RPI-CM1A-GPIO23-Pad47)") (class "Default")
      (node (ref "RPI-CM1") (pin "47") (pinfunction "GPIO23_47") (pintype "passive"))
    )
    (net (code "294") (name "unconnected-(RPI-CM1A-GPIO24-Pad45)") (class "Default")
      (node (ref "RPI-CM1") (pin "45") (pinfunction "GPIO24_45") (pintype "passive"))
    )
    (net (code "295") (name "unconnected-(RPI-CM1A-GPIO25-Pad41)") (class "Default")
      (node (ref "RPI-CM1") (pin "41") (pinfunction "GPIO25_41") (pintype "passive"))
    )
    (net (code "296") (name "unconnected-(RPI-CM1A-GPIO26-Pad24)") (class "Default")
      (node (ref "RPI-CM1") (pin "24") (pinfunction "GPIO26_24") (pintype "passive"))
    )
    (net (code "297") (name "unconnected-(RPI-CM1A-GPIO27-Pad48)") (class "Default")
      (node (ref "RPI-CM1") (pin "48") (pinfunction "GPIO27_48") (pintype "passive"))
    )
    (net (code "298") (name "unconnected-(RPI-CM1A-ID_SC-Pad35)") (class "Default")
      (node (ref "RPI-CM1") (pin "35") (pinfunction "ID_SC_35") (pintype "passive"))
    )
    (net (code "299") (name "unconnected-(RPI-CM1A-ID_SD-Pad36)") (class "Default")
      (node (ref "RPI-CM1") (pin "36") (pinfunction "ID_SD_36") (pintype "passive"))
    )
    (net (code "300") (name "unconnected-(RPI-CM1A-RESERVED-Pad76)") (class "Default")
      (node (ref "RPI-CM1") (pin "76") (pinfunction "RESERVED_76") (pintype "passive"))
    )
    (net (code "301") (name "unconnected-(RPI-CM1A-RUN_PG-Pad92)") (class "Default")
      (node (ref "RPI-CM1") (pin "92") (pinfunction "RUN_PG_92") (pintype "passive"))
    )
    (net (code "302") (name "unconnected-(RPI-CM1A-SD_CLK-Pad57)") (class "Default")
      (node (ref "RPI-CM1") (pin "57") (pinfunction "SD_CLK_57") (pintype "passive"))
    )
    (net (code "303") (name "unconnected-(RPI-CM1A-SD_CMD-Pad62)") (class "Default")
      (node (ref "RPI-CM1") (pin "62") (pinfunction "SD_CMD_62") (pintype "passive"))
    )
    (net (code "304") (name "unconnected-(RPI-CM1A-SD_DAT0-Pad63)") (class "Default")
      (node (ref "RPI-CM1") (pin "63") (pinfunction "SD_DAT0_63") (pintype "passive"))
    )
    (net (code "305") (name "unconnected-(RPI-CM1A-SD_DAT1-Pad67)") (class "Default")
      (node (ref "RPI-CM1") (pin "67") (pinfunction "SD_DAT1_67") (pintype "passive"))
    )
    (net (code "306") (name "unconnected-(RPI-CM1A-SD_DAT2-Pad69)") (class "Default")
      (node (ref "RPI-CM1") (pin "69") (pinfunction "SD_DAT2_69") (pintype "passive"))
    )
    (net (code "307") (name "unconnected-(RPI-CM1A-SD_DAT3-Pad61)") (class "Default")
      (node (ref "RPI-CM1") (pin "61") (pinfunction "SD_DAT3_61") (pintype "passive"))
    )
    (net (code "308") (name "unconnected-(RPI-CM1A-SD_DAT4-Pad68)") (class "Default")
      (node (ref "RPI-CM1") (pin "68") (pinfunction "SD_DAT4_68") (pintype "passive"))
    )
    (net (code "309") (name "unconnected-(RPI-CM1A-SD_DAT5-Pad64)") (class "Default")
      (node (ref "RPI-CM1") (pin "64") (pinfunction "SD_DAT5_64") (pintype "passive"))
    )
    (net (code "310") (name "unconnected-(RPI-CM1A-SD_DAT6-Pad72)") (class "Default")
      (node (ref "RPI-CM1") (pin "72") (pinfunction "SD_DAT6_72") (pintype "passive"))
    )
    (net (code "311") (name "unconnected-(RPI-CM1A-SD_DAT7-Pad70)") (class "Default")
      (node (ref "RPI-CM1") (pin "70") (pinfunction "SD_DAT7_70") (pintype "passive"))
    )
    (net (code "312") (name "unconnected-(RPI-CM1A-SD_PWR_ON-Pad75)") (class "Default")
      (node (ref "RPI-CM1") (pin "75") (pinfunction "SD_PWR_ON_75") (pintype "passive"))
    )
    (net (code "313") (name "unconnected-(RPI-CM1A-SD_VDD_OVERRIDE-Pad73)") (class "Default")
      (node (ref "RPI-CM1") (pin "73") (pinfunction "SD_VDD_OVERRIDE_73") (pintype "passive"))
    )
    (net (code "314") (name "unconnected-(RPI-CM1A-WL_~{DISABLE}-Pad89)") (class "Default")
      (node (ref "RPI-CM1") (pin "89") (pinfunction "WL_~{DISABLE}_89") (pintype "passive"))
    )
    (net (code "315") (name "unconnected-(RPI-CM1A-~{EXTRST}-Pad100)") (class "Default")
      (node (ref "RPI-CM1") (pin "100") (pinfunction "~{EXTRST}_100") (pintype "passive"))
    )
    (net (code "316") (name "unconnected-(U2-NC-Pad1)") (class "Default")
      (node (ref "U2") (pin "1") (pinfunction "NC_1") (pintype "no_connect"))
    )
    (net (code "317") (name "unconnected-(U4-~{PGOOD}-Pad7)") (class "Default")
      (node (ref "U4") (pin "7") (pinfunction "~{PGOOD}_7") (pintype "bidirectional"))
    )
    (net (code "318") (name "unconnected-(U5-NC-Pad1)") (class "Default")
      (node (ref "U5") (pin "1") (pinfunction "NC_1") (pintype "no_connect"))
    )
    (net (code "319") (name "unconnected-(U6-CS-Pad12)") (class "Default")
      (node (ref "U6") (pin "12") (pinfunction "CS_12") (pintype "bidirectional"))
    )
    (net (code "320") (name "unconnected-(U6-INT1-Pad4)") (class "Default")
      (node (ref "U6") (pin "4") (pinfunction "INT1_4") (pintype "bidirectional"))
    )
    (net (code "321") (name "unconnected-(U6-INT2-Pad9)") (class "Default")
      (node (ref "U6") (pin "9") (pinfunction "INT2_9") (pintype "bidirectional"))
    )
    (net (code "322") (name "unconnected-(U6-SCX-Pad3)") (class "Default")
      (node (ref "U6") (pin "3") (pinfunction "SCX_3") (pintype "bidirectional"))
    )
    (net (code "323") (name "unconnected-(U6-SDX-Pad2)") (class "Default")
      (node (ref "U6") (pin "2") (pinfunction "SDX_2") (pintype "bidirectional"))
    )
    (net (code "324") (name "unconnected-(U9-CLK-Pad7)") (class "Default")
      (node (ref "U9") (pin "7") (pinfunction "CLK_7") (pintype "bidirectional"))
    )
    (net (code "325") (name "unconnected-(U9-~{ALERT}-Pad8)") (class "Default")
      (node (ref "U9") (pin "8") (pinfunction "~{ALERT}_8") (pintype "output"))
    )
    (net (code "326") (name "unconnected-(U10-P4-Pad4)") (class "Default")
      (node (ref "U10") (pin "4") (pinfunction "P4_4") (pintype "bidirectional"))
    )
    (net (code "327") (name "unconnected-(U11-P4-Pad4)") (class "Default")
      (node (ref "U11") (pin "4") (pinfunction "P4_4") (pintype "bidirectional"))
    )
    (net (code "328") (name "unconnected-(U13-D1+-Pad1)") (class "Default")
      (node (ref "U13") (pin "1") (pinfunction "D1+_1") (pintype "passive"))
    )
    (net (code "329") (name "unconnected-(U13-D1--Pad2)") (class "Default")
      (node (ref "U13") (pin "2") (pinfunction "D1-_2") (pintype "passive"))
    )
    (net (code "330") (name "unconnected-(U13-NC-Pad10)") (class "Default")
      (node (ref "U13") (pin "10") (pinfunction "NC_10") (pintype "passive"))
    )
    (net (code "331") (name "unconnected-(U13-NC_2-Pad6)") (class "Default")
      (node (ref "U13") (pin "6") (pinfunction "NC_2_6") (pintype "passive"))
    )
    (net (code "332") (name "unconnected-(U13-NC_3-Pad7)") (class "Default")
      (node (ref "U13") (pin "7") (pinfunction "NC_3_7") (pintype "passive"))
    )
    (net (code "333") (name "unconnected-(U13-NC_4-Pad9)") (class "Default")
      (node (ref "U13") (pin "9") (pinfunction "NC_4_9") (pintype "passive"))
    )
    (net (code "334") (name "unconnected-(U15-P4-Pad4)") (class "Default")
      (node (ref "U15") (pin "4") (pinfunction "P4_4") (pintype "bidirectional"))
    )
    (net (code "335") (name "unconnected-(USB2.0MUX-D2+-Pad2)") (class "Default")
      (node (ref "USB2.0MUX") (pin "2") (pinfunction "D2+_2") (pintype "bidirectional"))
    )
    (net (code "336") (name "unconnected-(USB2.0MUX-D2--Pad6)") (class "Default")
      (node (ref "USB2.0MUX") (pin "6") (pinfunction "D2-_6") (pintype "bidirectional"))
    )
  )
)
